# Bottom_PCB.net
KiCad netlist of a schematic drawn in EAGLE
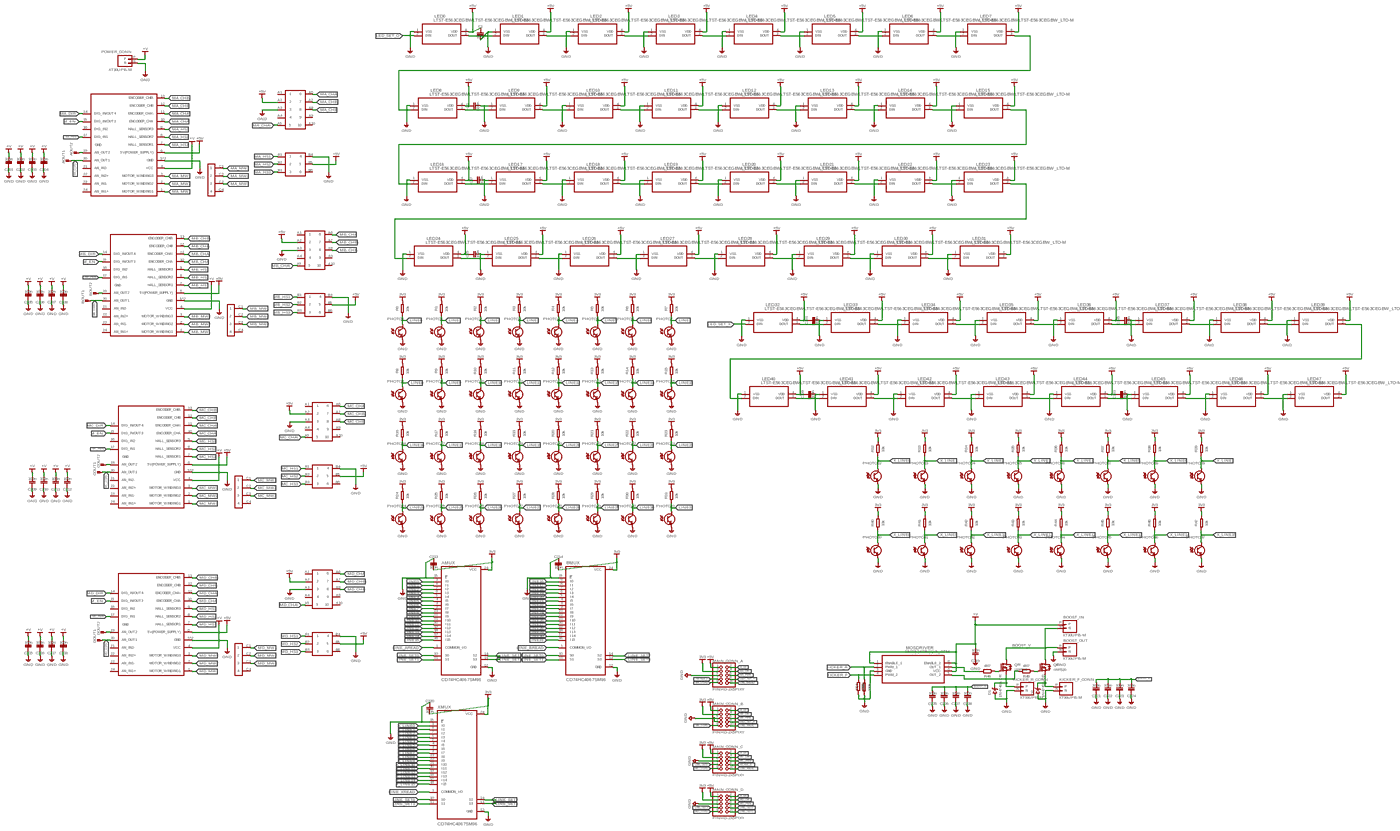
[diagram p0: schematic, sheet 1, overview]
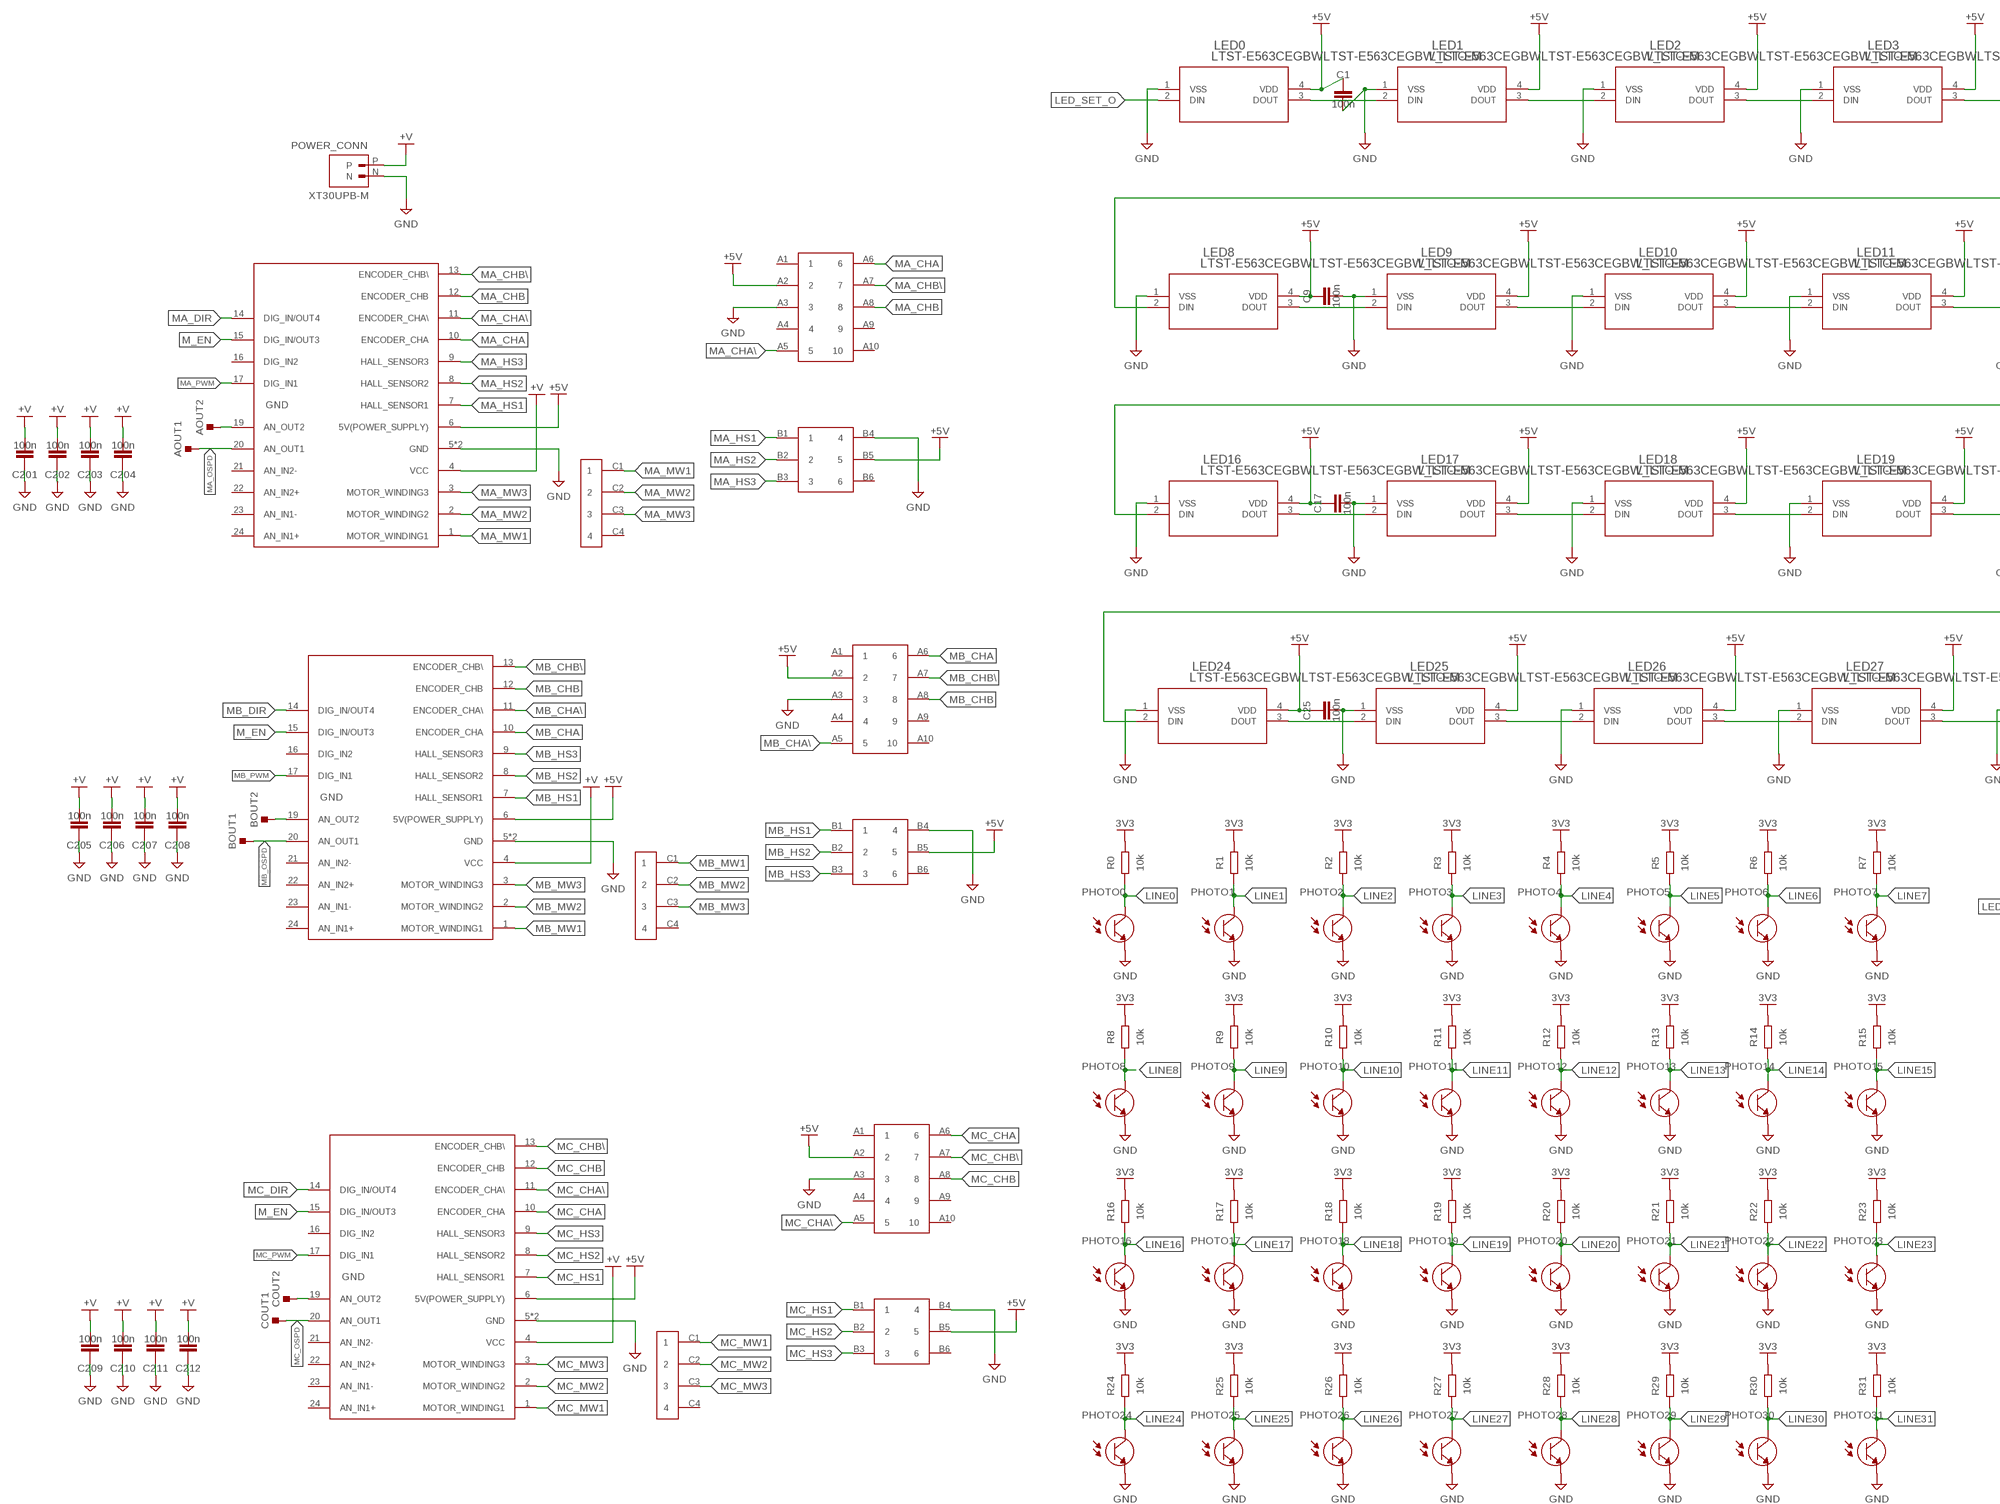
[diagram p1: schematic, sheet 1, part 1 of 4]
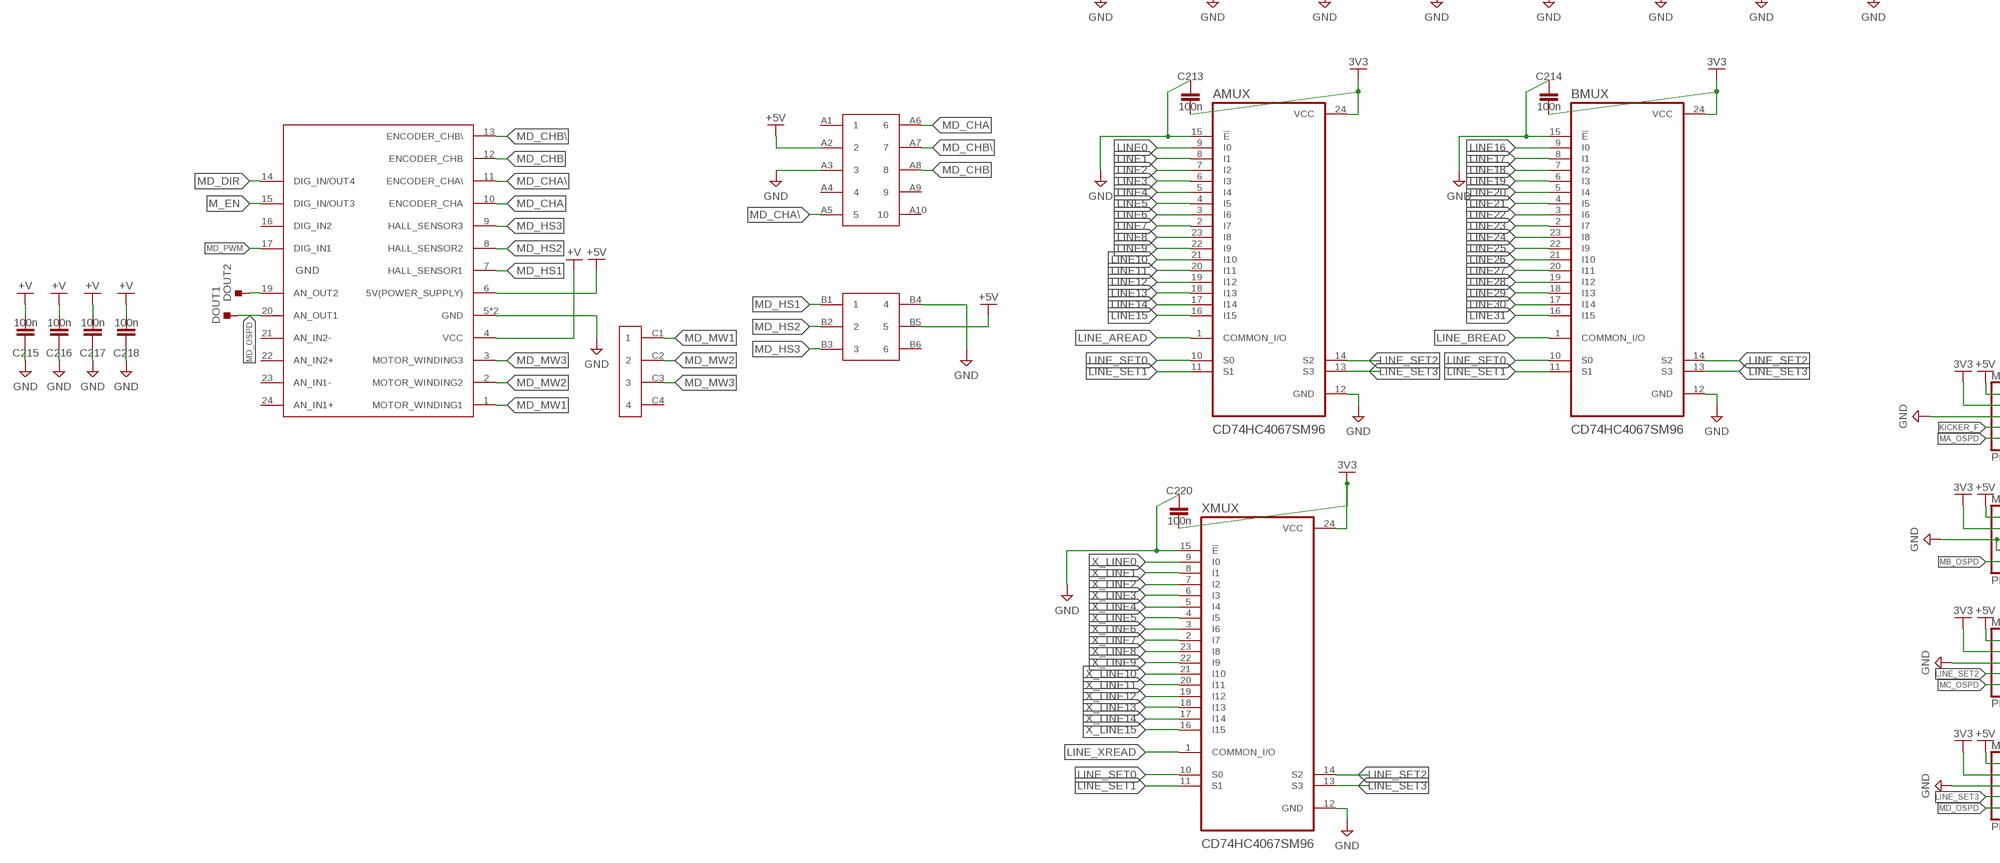
[diagram p2: schematic, sheet 1, part 2 of 4]
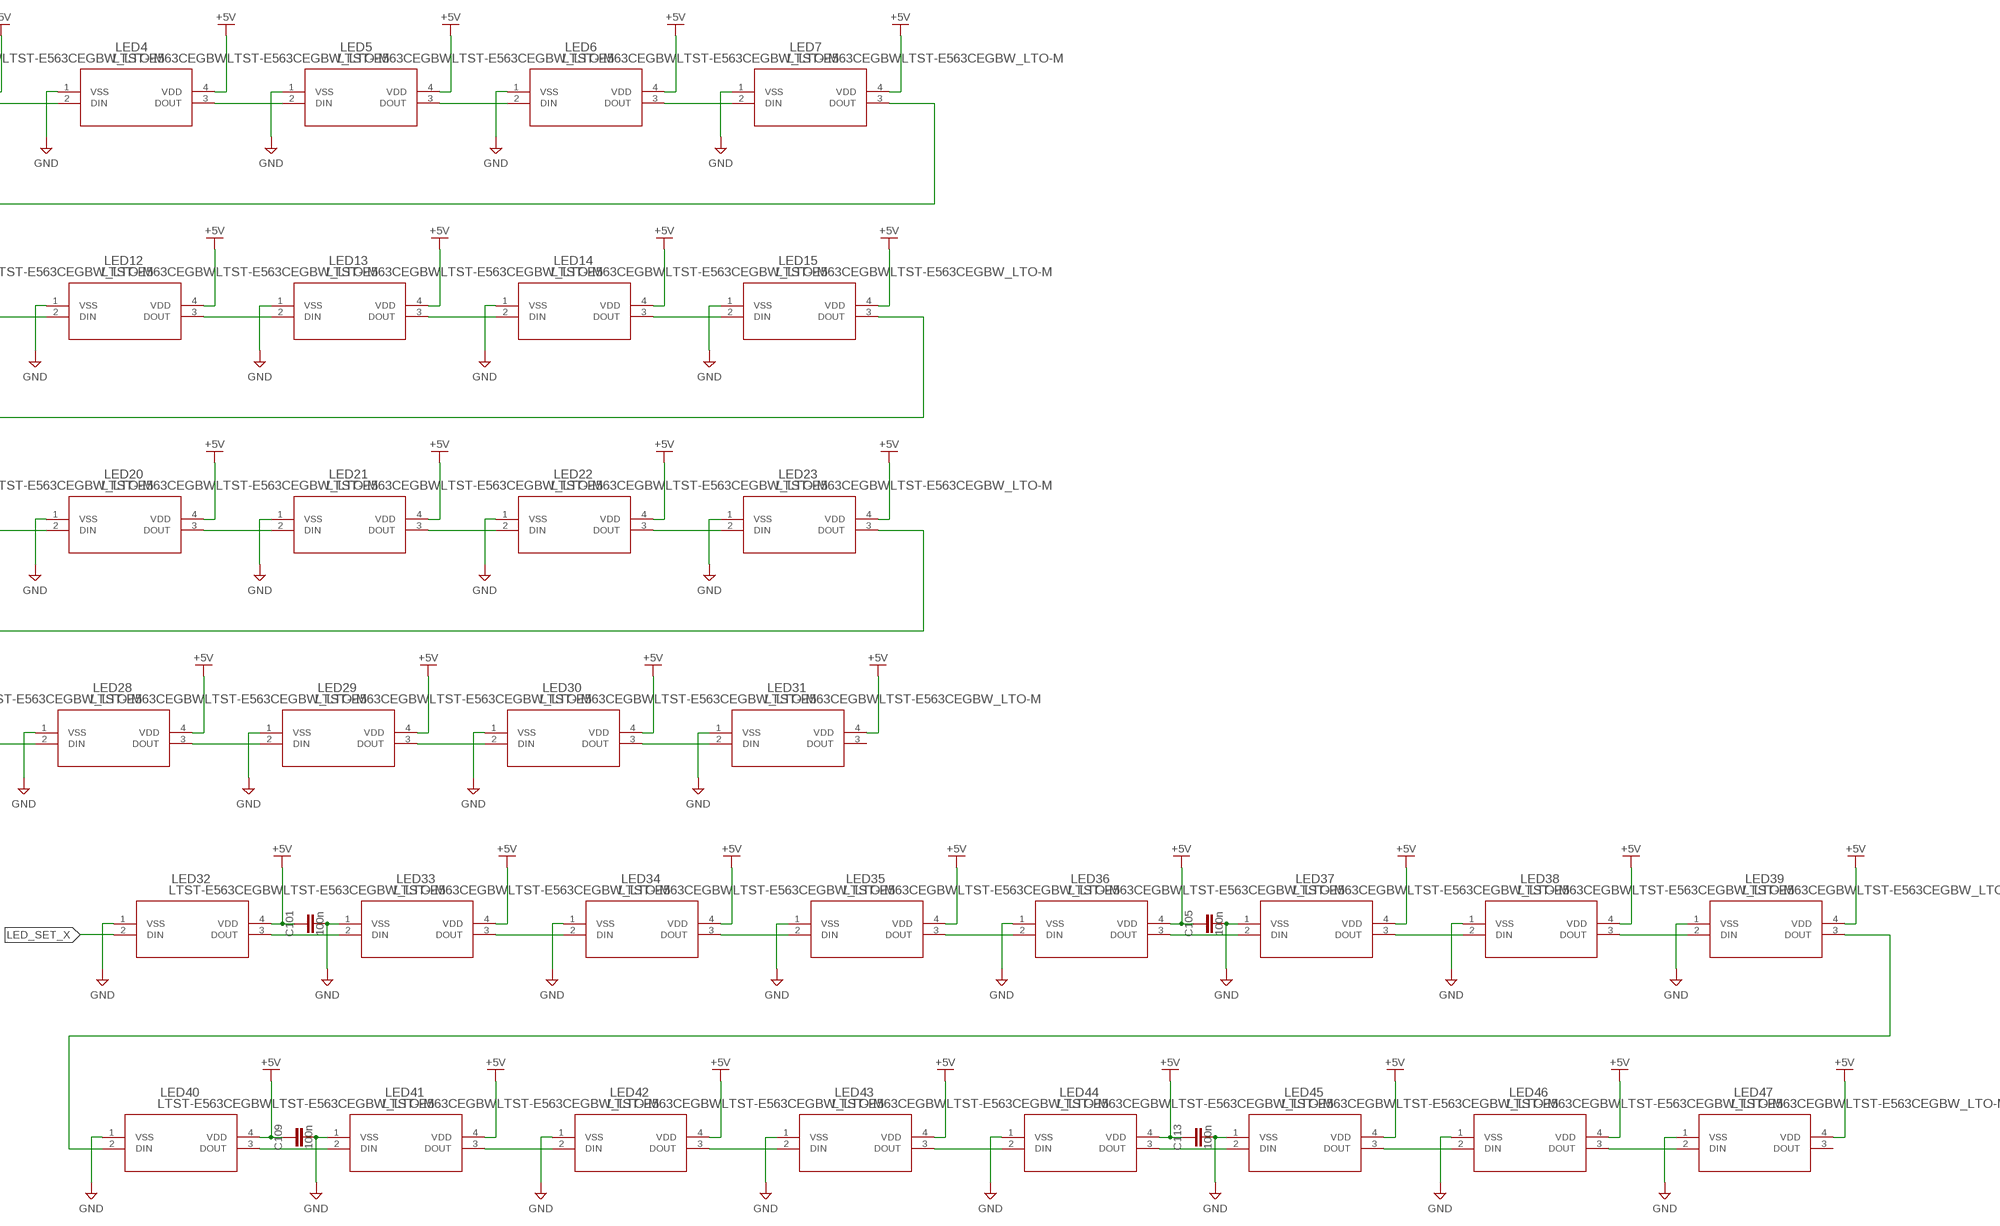
[diagram p3: schematic, sheet 1, part 3 of 4]
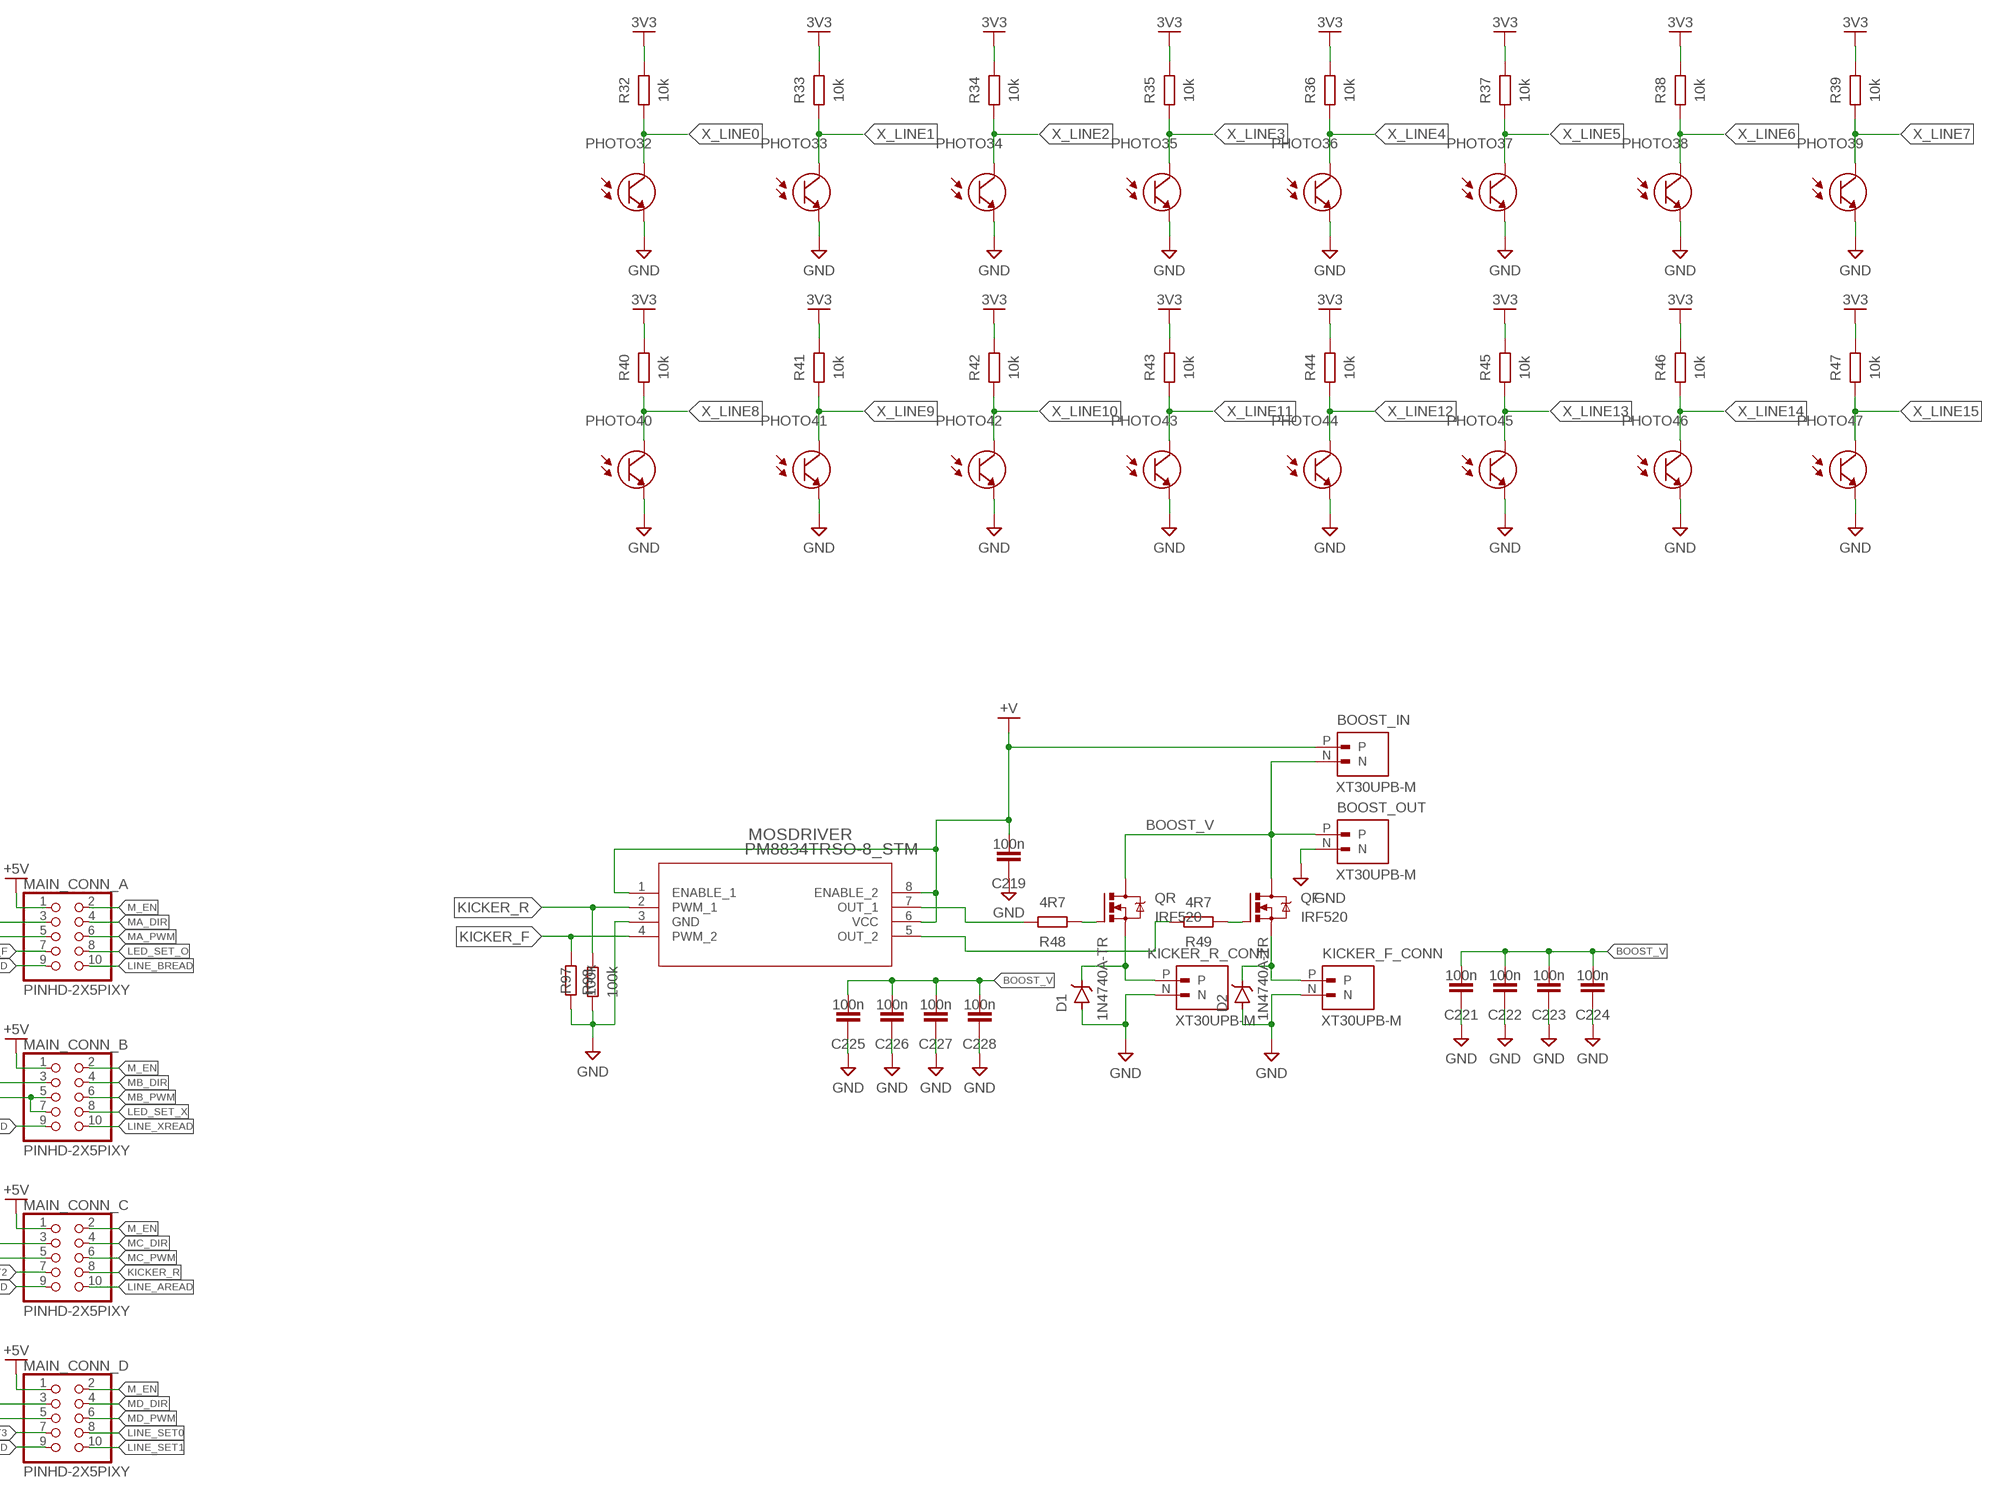
[diagram p4: schematic, sheet 1, part 4 of 4]

(export (version "E")
  (design (tool "Eeschema 10.0.6"))
  (components
    (comp (ref "AENC")
      (value "PIN2.54-2X5")
      (footprint "eagle-import:PIN2.54-2X5")
      (libsource (lib "eagle-import") (part "PIN2.54-2X5"))
    )
    (comp (ref "AHAL")
      (value "MX-44914-0601")
      (footprint "eagle-import:MX-44914-0601")
      (libsource (lib "eagle-import") (part "MX-44914-0601"))
    )
    (comp (ref "AMD")
      (value "ESCON24/224/2")
      (footprint "eagle-import:ESCON24_2")
      (libsource (lib "eagle-import") (part "ESCON24/224/2"))
    )
    (comp (ref "AMUX")
      (value "CD74HC4067SM96")
      (footprint "eagle-import:SOP65P780X200-24N")
      (libsource (lib "eagle-import") (part "CD74HC4067SM96"))
    )
    (comp (ref "AMW")
      (value "MX5566")
      (footprint "eagle-import:MX5566")
      (libsource (lib "eagle-import") (part "MX5566"))
    )
    (comp (ref "AOUT1")
      (value "TESTPOINT_TPS-PAD-036")
      (footprint "eagle-import:TESTPOINT_PAD-036")
      (libsource (lib "eagle-import") (part "TESTPOINT_TPS-PAD-036"))
    )
    (comp (ref "AOUT2")
      (value "TESTPOINT_TPS-PAD-036")
      (footprint "eagle-import:TESTPOINT_PAD-036")
      (libsource (lib "eagle-import") (part "TESTPOINT_TPS-PAD-036"))
    )
    (comp (ref "BENC")
      (value "PIN2.54-2X5")
      (footprint "eagle-import:PIN2.54-2X5")
      (libsource (lib "eagle-import") (part "PIN2.54-2X5"))
    )
    (comp (ref "BHAL")
      (value "MX-44914-0601")
      (footprint "eagle-import:MX-44914-0601")
      (libsource (lib "eagle-import") (part "MX-44914-0601"))
    )
    (comp (ref "BMD")
      (value "ESCON24/224/2")
      (footprint "eagle-import:ESCON24_2")
      (libsource (lib "eagle-import") (part "ESCON24/224/2"))
    )
    (comp (ref "BMUX")
      (value "CD74HC4067SM96")
      (footprint "eagle-import:SOP65P780X200-24N")
      (libsource (lib "eagle-import") (part "CD74HC4067SM96"))
    )
    (comp (ref "BMW")
      (value "MX5566")
      (footprint "eagle-import:MX5566")
      (libsource (lib "eagle-import") (part "MX5566"))
    )
    (comp (ref "BOOST_IN")
      (value "XT30UPB-M")
      (footprint "eagle-import:AMASS_XT30UPB-M")
      (fields (field (name "MF") "amass"))
      (libsource (lib "eagle-import") (part "XT30UPB-M"))
    )
    (comp (ref "BOOST_OUT")
      (value "XT30UPB-M")
      (footprint "eagle-import:AMASS_XT30UPB-M")
      (fields (field (name "MF") "amass"))
      (libsource (lib "eagle-import") (part "XT30UPB-M"))
    )
    (comp (ref "BOUT1")
      (value "TESTPOINT_TPS-PAD-036")
      (footprint "eagle-import:TESTPOINT_PAD-036")
      (libsource (lib "eagle-import") (part "TESTPOINT_TPS-PAD-036"))
    )
    (comp (ref "BOUT2")
      (value "TESTPOINT_TPS-PAD-036")
      (footprint "eagle-import:TESTPOINT_PAD-036")
      (libsource (lib "eagle-import") (part "TESTPOINT_TPS-PAD-036"))
    )
    (comp (ref "C1")
      (value "100n")
      (footprint "eagle-import:CAPC2012X110")
      (libsource (lib "eagle-import") (part "CCHIP-0805(2012-METRIC)_"))
    )
    (comp (ref "C9")
      (value "100n")
      (footprint "eagle-import:CAPC2012X110")
      (libsource (lib "eagle-import") (part "CCHIP-0805(2012-METRIC)_"))
    )
    (comp (ref "C17")
      (value "100n")
      (footprint "eagle-import:CAPC2012X110")
      (libsource (lib "eagle-import") (part "CCHIP-0805(2012-METRIC)_"))
    )
    (comp (ref "C25")
      (value "100n")
      (footprint "eagle-import:CAPC2012X110")
      (libsource (lib "eagle-import") (part "CCHIP-0805(2012-METRIC)_"))
    )
    (comp (ref "C101")
      (value "100n")
      (footprint "eagle-import:CAPC2012X110")
      (libsource (lib "eagle-import") (part "CCHIP-0805(2012-METRIC)_"))
    )
    (comp (ref "C105")
      (value "100n")
      (footprint "eagle-import:CAPC2012X110")
      (libsource (lib "eagle-import") (part "CCHIP-0805(2012-METRIC)_"))
    )
    (comp (ref "C109")
      (value "100n")
      (footprint "eagle-import:CAPC2012X110")
      (libsource (lib "eagle-import") (part "CCHIP-0805(2012-METRIC)_"))
    )
    (comp (ref "C113")
      (value "100n")
      (footprint "eagle-import:CAPC2012X110")
      (libsource (lib "eagle-import") (part "CCHIP-0805(2012-METRIC)_"))
    )
    (comp (ref "C201")
      (value "100n")
      (footprint "eagle-import:CAPC2012X110")
      (libsource (lib "eagle-import") (part "CCHIP-0805(2012-METRIC)_"))
    )
    (comp (ref "C202")
      (value "100n")
      (footprint "eagle-import:CAPC2012X110")
      (libsource (lib "eagle-import") (part "CCHIP-0805(2012-METRIC)_"))
    )
    (comp (ref "C203")
      (value "100n")
      (footprint "eagle-import:CAPC2012X110")
      (libsource (lib "eagle-import") (part "CCHIP-0805(2012-METRIC)_"))
    )
    (comp (ref "C204")
      (value "100n")
      (footprint "eagle-import:CAPC2012X110")
      (libsource (lib "eagle-import") (part "CCHIP-0805(2012-METRIC)_"))
    )
    (comp (ref "C205")
      (value "100n")
      (footprint "eagle-import:CAPC2012X110")
      (libsource (lib "eagle-import") (part "CCHIP-0805(2012-METRIC)_"))
    )
    (comp (ref "C206")
      (value "100n")
      (footprint "eagle-import:CAPC2012X110")
      (libsource (lib "eagle-import") (part "CCHIP-0805(2012-METRIC)_"))
    )
    (comp (ref "C207")
      (value "100n")
      (footprint "eagle-import:CAPC2012X110")
      (libsource (lib "eagle-import") (part "CCHIP-0805(2012-METRIC)_"))
    )
    (comp (ref "C208")
      (value "100n")
      (footprint "eagle-import:CAPC2012X110")
      (libsource (lib "eagle-import") (part "CCHIP-0805(2012-METRIC)_"))
    )
    (comp (ref "C209")
      (value "100n")
      (footprint "eagle-import:CAPC2012X110")
      (libsource (lib "eagle-import") (part "CCHIP-0805(2012-METRIC)_"))
    )
    (comp (ref "C210")
      (value "100n")
      (footprint "eagle-import:CAPC2012X110")
      (libsource (lib "eagle-import") (part "CCHIP-0805(2012-METRIC)_"))
    )
    (comp (ref "C211")
      (value "100n")
      (footprint "eagle-import:CAPC2012X110")
      (libsource (lib "eagle-import") (part "CCHIP-0805(2012-METRIC)_"))
    )
    (comp (ref "C212")
      (value "100n")
      (footprint "eagle-import:CAPC2012X110")
      (libsource (lib "eagle-import") (part "CCHIP-0805(2012-METRIC)_"))
    )
    (comp (ref "C213")
      (value "100n")
      (footprint "eagle-import:CAPC2012X110")
      (libsource (lib "eagle-import") (part "CCHIP-0805(2012-METRIC)_"))
    )
    (comp (ref "C214")
      (value "100n")
      (footprint "eagle-import:CAPC2012X110")
      (libsource (lib "eagle-import") (part "CCHIP-0805(2012-METRIC)_"))
    )
    (comp (ref "C215")
      (value "100n")
      (footprint "eagle-import:CAPC2012X110")
      (libsource (lib "eagle-import") (part "CCHIP-0805(2012-METRIC)_"))
    )
    (comp (ref "C216")
      (value "100n")
      (footprint "eagle-import:CAPC2012X110")
      (libsource (lib "eagle-import") (part "CCHIP-0805(2012-METRIC)_"))
    )
    (comp (ref "C217")
      (value "100n")
      (footprint "eagle-import:CAPC2012X110")
      (libsource (lib "eagle-import") (part "CCHIP-0805(2012-METRIC)_"))
    )
    (comp (ref "C218")
      (value "100n")
      (footprint "eagle-import:CAPC2012X110")
      (libsource (lib "eagle-import") (part "CCHIP-0805(2012-METRIC)_"))
    )
    (comp (ref "C219")
      (value "100n")
      (footprint "eagle-import:CAPC2012X110")
      (libsource (lib "eagle-import") (part "CCHIP-0805(2012-METRIC)_"))
    )
    (comp (ref "C220")
      (value "100n")
      (footprint "eagle-import:CAPC2012X110")
      (libsource (lib "eagle-import") (part "CCHIP-0805(2012-METRIC)_"))
    )
    (comp (ref "C221")
      (value "100n")
      (footprint "eagle-import:CAPC2012X110")
      (libsource (lib "eagle-import") (part "CCHIP-0805(2012-METRIC)_"))
    )
    (comp (ref "C222")
      (value "100n")
      (footprint "eagle-import:CAPC2012X110")
      (libsource (lib "eagle-import") (part "CCHIP-0805(2012-METRIC)_"))
    )
    (comp (ref "C223")
      (value "100n")
      (footprint "eagle-import:CAPC2012X110")
      (libsource (lib "eagle-import") (part "CCHIP-0805(2012-METRIC)_"))
    )
    (comp (ref "C224")
      (value "100n")
      (footprint "eagle-import:CAPC2012X110")
      (libsource (lib "eagle-import") (part "CCHIP-0805(2012-METRIC)_"))
    )
    (comp (ref "C225")
      (value "100n")
      (footprint "eagle-import:CAPC2012X110")
      (libsource (lib "eagle-import") (part "CCHIP-0805(2012-METRIC)_"))
    )
    (comp (ref "C226")
      (value "100n")
      (footprint "eagle-import:CAPC2012X110")
      (libsource (lib "eagle-import") (part "CCHIP-0805(2012-METRIC)_"))
    )
    (comp (ref "C227")
      (value "100n")
      (footprint "eagle-import:CAPC2012X110")
      (libsource (lib "eagle-import") (part "CCHIP-0805(2012-METRIC)_"))
    )
    (comp (ref "C228")
      (value "100n")
      (footprint "eagle-import:CAPC2012X110")
      (libsource (lib "eagle-import") (part "CCHIP-0805(2012-METRIC)_"))
    )
    (comp (ref "CENC")
      (value "PIN2.54-2X5")
      (footprint "eagle-import:PIN2.54-2X5")
      (libsource (lib "eagle-import") (part "PIN2.54-2X5"))
    )
    (comp (ref "CHAL")
      (value "MX-44914-0601")
      (footprint "eagle-import:MX-44914-0601")
      (libsource (lib "eagle-import") (part "MX-44914-0601"))
    )
    (comp (ref "CMD")
      (value "ESCON24/224/2")
      (footprint "eagle-import:ESCON24_2")
      (libsource (lib "eagle-import") (part "ESCON24/224/2"))
    )
    (comp (ref "CMW")
      (value "MX5566")
      (footprint "eagle-import:MX5566")
      (libsource (lib "eagle-import") (part "MX5566"))
    )
    (comp (ref "COUT1")
      (value "TESTPOINT_TPS-PAD-036")
      (footprint "eagle-import:TESTPOINT_PAD-036")
      (libsource (lib "eagle-import") (part "TESTPOINT_TPS-PAD-036"))
    )
    (comp (ref "COUT2")
      (value "TESTPOINT_TPS-PAD-036")
      (footprint "eagle-import:TESTPOINT_PAD-036")
      (libsource (lib "eagle-import") (part "TESTPOINT_TPS-PAD-036"))
    )
    (comp (ref "D1")
      (value "1N4740A-TR")
      (footprint "eagle-import:DO-41")
      (fields
        (field (name "MANUFACTURER") "Vishay General Semiconductor - Diodes Division")
        (field (name "DIGIKEY_PART_NUMBER") "1N4740AVSCT-ND")
        (field (name "CREATED_BY") "PCBLayout.com")
      )
      (libsource (lib "eagle-import") (part "1N4740A-TR"))
    )
    (comp (ref "D2")
      (value "1N4740A-TR")
      (footprint "eagle-import:DO-41")
      (fields
        (field (name "MANUFACTURER") "Vishay General Semiconductor - Diodes Division")
        (field (name "DIGIKEY_PART_NUMBER") "1N4740AVSCT-ND")
        (field (name "CREATED_BY") "PCBLayout.com")
      )
      (libsource (lib "eagle-import") (part "1N4740A-TR"))
    )
    (comp (ref "DENC")
      (value "PIN2.54-2X5")
      (footprint "eagle-import:PIN2.54-2X5")
      (libsource (lib "eagle-import") (part "PIN2.54-2X5"))
    )
    (comp (ref "DHAL")
      (value "MX-44914-0601")
      (footprint "eagle-import:MX-44914-0601")
      (libsource (lib "eagle-import") (part "MX-44914-0601"))
    )
    (comp (ref "DMD")
      (value "ESCON24/224/2")
      (footprint "eagle-import:ESCON24_2")
      (libsource (lib "eagle-import") (part "ESCON24/224/2"))
    )
    (comp (ref "DMW")
      (value "MX5566")
      (footprint "eagle-import:MX5566")
      (libsource (lib "eagle-import") (part "MX5566"))
    )
    (comp (ref "DOUT1")
      (value "TESTPOINT_TPS-PAD-036")
      (footprint "eagle-import:TESTPOINT_PAD-036")
      (libsource (lib "eagle-import") (part "TESTPOINT_TPS-PAD-036"))
    )
    (comp (ref "DOUT2")
      (value "TESTPOINT_TPS-PAD-036")
      (footprint "eagle-import:TESTPOINT_PAD-036")
      (libsource (lib "eagle-import") (part "TESTPOINT_TPS-PAD-036"))
    )
    (comp (ref "KICKER_F_CONN")
      (value "XT30UPB-M")
      (footprint "eagle-import:AMASS_XT30UPB-M")
      (fields (field (name "MF") "amass"))
      (libsource (lib "eagle-import") (part "XT30UPB-M"))
    )
    (comp (ref "KICKER_R_CONN")
      (value "XT30UPB-M")
      (footprint "eagle-import:AMASS_XT30UPB-M")
      (fields (field (name "MF") "amass"))
      (libsource (lib "eagle-import") (part "XT30UPB-M"))
    )
    (comp (ref "LED0")
      (value "LTST-E563CEGBWLTST-E563CEGBW_LTO-M")
      (footprint "eagle-import:LTST-E563CEGBW_LTO-M")
      (fields
        (field (name "MANUFACTURER_PART_NUMBER") "LTST-E563CEGBW")
        (field (name "COPYRIGHT") "Copyright (C) 2025 Ultra Librarian. All rights reserved.")
      )
      (libsource (lib "eagle-import") (part "LTST-E563CEGBWLTST-E563CEGBW_LTO-M"))
    )
    (comp (ref "LED1")
      (value "LTST-E563CEGBWLTST-E563CEGBW_LTO-M")
      (footprint "eagle-import:LTST-E563CEGBW_LTO-M")
      (fields
        (field (name "MANUFACTURER_PART_NUMBER") "LTST-E563CEGBW")
        (field (name "COPYRIGHT") "Copyright (C) 2025 Ultra Librarian. All rights reserved.")
      )
      (libsource (lib "eagle-import") (part "LTST-E563CEGBWLTST-E563CEGBW_LTO-M"))
    )
    (comp (ref "LED2")
      (value "LTST-E563CEGBWLTST-E563CEGBW_LTO-M")
      (footprint "eagle-import:LTST-E563CEGBW_LTO-M")
      (fields
        (field (name "MANUFACTURER_PART_NUMBER") "LTST-E563CEGBW")
        (field (name "COPYRIGHT") "Copyright (C) 2025 Ultra Librarian. All rights reserved.")
      )
      (libsource (lib "eagle-import") (part "LTST-E563CEGBWLTST-E563CEGBW_LTO-M"))
    )
    (comp (ref "LED3")
      (value "LTST-E563CEGBWLTST-E563CEGBW_LTO-M")
      (footprint "eagle-import:LTST-E563CEGBW_LTO-M")
      (fields
        (field (name "MANUFACTURER_PART_NUMBER") "LTST-E563CEGBW")
        (field (name "COPYRIGHT") "Copyright (C) 2025 Ultra Librarian. All rights reserved.")
      )
      (libsource (lib "eagle-import") (part "LTST-E563CEGBWLTST-E563CEGBW_LTO-M"))
    )
    (comp (ref "LED4")
      (value "LTST-E563CEGBWLTST-E563CEGBW_LTO-M")
      (footprint "eagle-import:LTST-E563CEGBW_LTO-M")
      (fields
        (field (name "MANUFACTURER_PART_NUMBER") "LTST-E563CEGBW")
        (field (name "COPYRIGHT") "Copyright (C) 2025 Ultra Librarian. All rights reserved.")
      )
      (libsource (lib "eagle-import") (part "LTST-E563CEGBWLTST-E563CEGBW_LTO-M"))
    )
    (comp (ref "LED5")
      (value "LTST-E563CEGBWLTST-E563CEGBW_LTO-M")
      (footprint "eagle-import:LTST-E563CEGBW_LTO-M")
      (fields
        (field (name "MANUFACTURER_PART_NUMBER") "LTST-E563CEGBW")
        (field (name "COPYRIGHT") "Copyright (C) 2025 Ultra Librarian. All rights reserved.")
      )
      (libsource (lib "eagle-import") (part "LTST-E563CEGBWLTST-E563CEGBW_LTO-M"))
    )
    (comp (ref "LED6")
      (value "LTST-E563CEGBWLTST-E563CEGBW_LTO-M")
      (footprint "eagle-import:LTST-E563CEGBW_LTO-M")
      (fields
        (field (name "MANUFACTURER_PART_NUMBER") "LTST-E563CEGBW")
        (field (name "COPYRIGHT") "Copyright (C) 2025 Ultra Librarian. All rights reserved.")
      )
      (libsource (lib "eagle-import") (part "LTST-E563CEGBWLTST-E563CEGBW_LTO-M"))
    )
    (comp (ref "LED7")
      (value "LTST-E563CEGBWLTST-E563CEGBW_LTO-M")
      (footprint "eagle-import:LTST-E563CEGBW_LTO-M")
      (fields
        (field (name "MANUFACTURER_PART_NUMBER") "LTST-E563CEGBW")
        (field (name "COPYRIGHT") "Copyright (C) 2025 Ultra Librarian. All rights reserved.")
      )
      (libsource (lib "eagle-import") (part "LTST-E563CEGBWLTST-E563CEGBW_LTO-M"))
    )
    (comp (ref "LED8")
      (value "LTST-E563CEGBWLTST-E563CEGBW_LTO-M")
      (footprint "eagle-import:LTST-E563CEGBW_LTO-M")
      (fields
        (field (name "MANUFACTURER_PART_NUMBER") "LTST-E563CEGBW")
        (field (name "COPYRIGHT") "Copyright (C) 2025 Ultra Librarian. All rights reserved.")
      )
      (libsource (lib "eagle-import") (part "LTST-E563CEGBWLTST-E563CEGBW_LTO-M"))
    )
    (comp (ref "LED9")
      (value "LTST-E563CEGBWLTST-E563CEGBW_LTO-M")
      (footprint "eagle-import:LTST-E563CEGBW_LTO-M")
      (fields
        (field (name "MANUFACTURER_PART_NUMBER") "LTST-E563CEGBW")
        (field (name "COPYRIGHT") "Copyright (C) 2025 Ultra Librarian. All rights reserved.")
      )
      (libsource (lib "eagle-import") (part "LTST-E563CEGBWLTST-E563CEGBW_LTO-M"))
    )
    (comp (ref "LED10")
      (value "LTST-E563CEGBWLTST-E563CEGBW_LTO-M")
      (footprint "eagle-import:LTST-E563CEGBW_LTO-M")
      (fields
        (field (name "MANUFACTURER_PART_NUMBER") "LTST-E563CEGBW")
        (field (name "COPYRIGHT") "Copyright (C) 2025 Ultra Librarian. All rights reserved.")
      )
      (libsource (lib "eagle-import") (part "LTST-E563CEGBWLTST-E563CEGBW_LTO-M"))
    )
    (comp (ref "LED11")
      (value "LTST-E563CEGBWLTST-E563CEGBW_LTO-M")
      (footprint "eagle-import:LTST-E563CEGBW_LTO-M")
      (fields
        (field (name "MANUFACTURER_PART_NUMBER") "LTST-E563CEGBW")
        (field (name "COPYRIGHT") "Copyright (C) 2025 Ultra Librarian. All rights reserved.")
      )
      (libsource (lib "eagle-import") (part "LTST-E563CEGBWLTST-E563CEGBW_LTO-M"))
    )
    (comp (ref "LED12")
      (value "LTST-E563CEGBWLTST-E563CEGBW_LTO-M")
      (footprint "eagle-import:LTST-E563CEGBW_LTO-M")
      (fields
        (field (name "MANUFACTURER_PART_NUMBER") "LTST-E563CEGBW")
        (field (name "COPYRIGHT") "Copyright (C) 2025 Ultra Librarian. All rights reserved.")
      )
      (libsource (lib "eagle-import") (part "LTST-E563CEGBWLTST-E563CEGBW_LTO-M"))
    )
    (comp (ref "LED13")
      (value "LTST-E563CEGBWLTST-E563CEGBW_LTO-M")
      (footprint "eagle-import:LTST-E563CEGBW_LTO-M")
      (fields
        (field (name "MANUFACTURER_PART_NUMBER") "LTST-E563CEGBW")
        (field (name "COPYRIGHT") "Copyright (C) 2025 Ultra Librarian. All rights reserved.")
      )
      (libsource (lib "eagle-import") (part "LTST-E563CEGBWLTST-E563CEGBW_LTO-M"))
    )
    (comp (ref "LED14")
      (value "LTST-E563CEGBWLTST-E563CEGBW_LTO-M")
      (footprint "eagle-import:LTST-E563CEGBW_LTO-M")
      (fields
        (field (name "MANUFACTURER_PART_NUMBER") "LTST-E563CEGBW")
        (field (name "COPYRIGHT") "Copyright (C) 2025 Ultra Librarian. All rights reserved.")
      )
      (libsource (lib "eagle-import") (part "LTST-E563CEGBWLTST-E563CEGBW_LTO-M"))
    )
    (comp (ref "LED15")
      (value "LTST-E563CEGBWLTST-E563CEGBW_LTO-M")
      (footprint "eagle-import:LTST-E563CEGBW_LTO-M")
      (fields
        (field (name "MANUFACTURER_PART_NUMBER") "LTST-E563CEGBW")
        (field (name "COPYRIGHT") "Copyright (C) 2025 Ultra Librarian. All rights reserved.")
      )
      (libsource (lib "eagle-import") (part "LTST-E563CEGBWLTST-E563CEGBW_LTO-M"))
    )
    (comp (ref "LED16")
      (value "LTST-E563CEGBWLTST-E563CEGBW_LTO-M")
      (footprint "eagle-import:LTST-E563CEGBW_LTO-M")
      (fields
        (field (name "MANUFACTURER_PART_NUMBER") "LTST-E563CEGBW")
        (field (name "COPYRIGHT") "Copyright (C) 2025 Ultra Librarian. All rights reserved.")
      )
      (libsource (lib "eagle-import") (part "LTST-E563CEGBWLTST-E563CEGBW_LTO-M"))
    )
    (comp (ref "LED17")
      (value "LTST-E563CEGBWLTST-E563CEGBW_LTO-M")
      (footprint "eagle-import:LTST-E563CEGBW_LTO-M")
      (fields
        (field (name "MANUFACTURER_PART_NUMBER") "LTST-E563CEGBW")
        (field (name "COPYRIGHT") "Copyright (C) 2025 Ultra Librarian. All rights reserved.")
      )
      (libsource (lib "eagle-import") (part "LTST-E563CEGBWLTST-E563CEGBW_LTO-M"))
    )
    (comp (ref "LED18")
      (value "LTST-E563CEGBWLTST-E563CEGBW_LTO-M")
      (footprint "eagle-import:LTST-E563CEGBW_LTO-M")
      (fields
        (field (name "MANUFACTURER_PART_NUMBER") "LTST-E563CEGBW")
        (field (name "COPYRIGHT") "Copyright (C) 2025 Ultra Librarian. All rights reserved.")
      )
      (libsource (lib "eagle-import") (part "LTST-E563CEGBWLTST-E563CEGBW_LTO-M"))
    )
    (comp (ref "LED19")
      (value "LTST-E563CEGBWLTST-E563CEGBW_LTO-M")
      (footprint "eagle-import:LTST-E563CEGBW_LTO-M")
      (fields
        (field (name "MANUFACTURER_PART_NUMBER") "LTST-E563CEGBW")
        (field (name "COPYRIGHT") "Copyright (C) 2025 Ultra Librarian. All rights reserved.")
      )
      (libsource (lib "eagle-import") (part "LTST-E563CEGBWLTST-E563CEGBW_LTO-M"))
    )
    (comp (ref "LED20")
      (value "LTST-E563CEGBWLTST-E563CEGBW_LTO-M")
      (footprint "eagle-import:LTST-E563CEGBW_LTO-M")
      (fields
        (field (name "MANUFACTURER_PART_NUMBER") "LTST-E563CEGBW")
        (field (name "COPYRIGHT") "Copyright (C) 2025 Ultra Librarian. All rights reserved.")
      )
      (libsource (lib "eagle-import") (part "LTST-E563CEGBWLTST-E563CEGBW_LTO-M"))
    )
    (comp (ref "LED21")
      (value "LTST-E563CEGBWLTST-E563CEGBW_LTO-M")
      (footprint "eagle-import:LTST-E563CEGBW_LTO-M")
      (fields
        (field (name "MANUFACTURER_PART_NUMBER") "LTST-E563CEGBW")
        (field (name "COPYRIGHT") "Copyright (C) 2025 Ultra Librarian. All rights reserved.")
      )
      (libsource (lib "eagle-import") (part "LTST-E563CEGBWLTST-E563CEGBW_LTO-M"))
    )
    (comp (ref "LED22")
      (value "LTST-E563CEGBWLTST-E563CEGBW_LTO-M")
      (footprint "eagle-import:LTST-E563CEGBW_LTO-M")
      (fields
        (field (name "MANUFACTURER_PART_NUMBER") "LTST-E563CEGBW")
        (field (name "COPYRIGHT") "Copyright (C) 2025 Ultra Librarian. All rights reserved.")
      )
      (libsource (lib "eagle-import") (part "LTST-E563CEGBWLTST-E563CEGBW_LTO-M"))
    )
    (comp (ref "LED23")
      (value "LTST-E563CEGBWLTST-E563CEGBW_LTO-M")
      (footprint "eagle-import:LTST-E563CEGBW_LTO-M")
      (fields
        (field (name "MANUFACTURER_PART_NUMBER") "LTST-E563CEGBW")
        (field (name "COPYRIGHT") "Copyright (C) 2025 Ultra Librarian. All rights reserved.")
      )
      (libsource (lib "eagle-import") (part "LTST-E563CEGBWLTST-E563CEGBW_LTO-M"))
    )
    (comp (ref "LED24")
      (value "LTST-E563CEGBWLTST-E563CEGBW_LTO-M")
      (footprint "eagle-import:LTST-E563CEGBW_LTO-M")
      (fields
        (field (name "MANUFACTURER_PART_NUMBER") "LTST-E563CEGBW")
        (field (name "COPYRIGHT") "Copyright (C) 2025 Ultra Librarian. All rights reserved.")
      )
      (libsource (lib "eagle-import") (part "LTST-E563CEGBWLTST-E563CEGBW_LTO-M"))
    )
    (comp (ref "LED25")
      (value "LTST-E563CEGBWLTST-E563CEGBW_LTO-M")
      (footprint "eagle-import:LTST-E563CEGBW_LTO-M")
      (fields
        (field (name "MANUFACTURER_PART_NUMBER") "LTST-E563CEGBW")
        (field (name "COPYRIGHT") "Copyright (C) 2025 Ultra Librarian. All rights reserved.")
      )
      (libsource (lib "eagle-import") (part "LTST-E563CEGBWLTST-E563CEGBW_LTO-M"))
    )
    (comp (ref "LED26")
      (value "LTST-E563CEGBWLTST-E563CEGBW_LTO-M")
      (footprint "eagle-import:LTST-E563CEGBW_LTO-M")
      (fields
        (field (name "MANUFACTURER_PART_NUMBER") "LTST-E563CEGBW")
        (field (name "COPYRIGHT") "Copyright (C) 2025 Ultra Librarian. All rights reserved.")
      )
      (libsource (lib "eagle-import") (part "LTST-E563CEGBWLTST-E563CEGBW_LTO-M"))
    )
    (comp (ref "LED27")
      (value "LTST-E563CEGBWLTST-E563CEGBW_LTO-M")
      (footprint "eagle-import:LTST-E563CEGBW_LTO-M")
      (fields
        (field (name "MANUFACTURER_PART_NUMBER") "LTST-E563CEGBW")
        (field (name "COPYRIGHT") "Copyright (C) 2025 Ultra Librarian. All rights reserved.")
      )
      (libsource (lib "eagle-import") (part "LTST-E563CEGBWLTST-E563CEGBW_LTO-M"))
    )
    (comp (ref "LED28")
      (value "LTST-E563CEGBWLTST-E563CEGBW_LTO-M")
      (footprint "eagle-import:LTST-E563CEGBW_LTO-M")
      (fields
        (field (name "MANUFACTURER_PART_NUMBER") "LTST-E563CEGBW")
        (field (name "COPYRIGHT") "Copyright (C) 2025 Ultra Librarian. All rights reserved.")
      )
      (libsource (lib "eagle-import") (part "LTST-E563CEGBWLTST-E563CEGBW_LTO-M"))
    )
    (comp (ref "LED29")
      (value "LTST-E563CEGBWLTST-E563CEGBW_LTO-M")
      (footprint "eagle-import:LTST-E563CEGBW_LTO-M")
      (fields
        (field (name "MANUFACTURER_PART_NUMBER") "LTST-E563CEGBW")
        (field (name "COPYRIGHT") "Copyright (C) 2025 Ultra Librarian. All rights reserved.")
      )
      (libsource (lib "eagle-import") (part "LTST-E563CEGBWLTST-E563CEGBW_LTO-M"))
    )
    (comp (ref "LED30")
      (value "LTST-E563CEGBWLTST-E563CEGBW_LTO-M")
      (footprint "eagle-import:LTST-E563CEGBW_LTO-M")
      (fields
        (field (name "MANUFACTURER_PART_NUMBER") "LTST-E563CEGBW")
        (field (name "COPYRIGHT") "Copyright (C) 2025 Ultra Librarian. All rights reserved.")
      )
      (libsource (lib "eagle-import") (part "LTST-E563CEGBWLTST-E563CEGBW_LTO-M"))
    )
    (comp (ref "LED31")
      (value "LTST-E563CEGBWLTST-E563CEGBW_LTO-M")
      (footprint "eagle-import:LTST-E563CEGBW_LTO-M")
      (fields
        (field (name "MANUFACTURER_PART_NUMBER") "LTST-E563CEGBW")
        (field (name "COPYRIGHT") "Copyright (C) 2025 Ultra Librarian. All rights reserved.")
      )
      (libsource (lib "eagle-import") (part "LTST-E563CEGBWLTST-E563CEGBW_LTO-M"))
    )
    (comp (ref "LED32")
      (value "LTST-E563CEGBWLTST-E563CEGBW_LTO-M")
      (footprint "eagle-import:LTST-E563CEGBW_LTO-M")
      (fields
        (field (name "MANUFACTURER_PART_NUMBER") "LTST-E563CEGBW")
        (field (name "COPYRIGHT") "Copyright (C) 2025 Ultra Librarian. All rights reserved.")
      )
      (libsource (lib "eagle-import") (part "LTST-E563CEGBWLTST-E563CEGBW_LTO-M"))
    )
    (comp (ref "LED33")
      (value "LTST-E563CEGBWLTST-E563CEGBW_LTO-M")
      (footprint "eagle-import:LTST-E563CEGBW_LTO-M")
      (fields
        (field (name "MANUFACTURER_PART_NUMBER") "LTST-E563CEGBW")
        (field (name "COPYRIGHT") "Copyright (C) 2025 Ultra Librarian. All rights reserved.")
      )
      (libsource (lib "eagle-import") (part "LTST-E563CEGBWLTST-E563CEGBW_LTO-M"))
    )
    (comp (ref "LED34")
      (value "LTST-E563CEGBWLTST-E563CEGBW_LTO-M")
      (footprint "eagle-import:LTST-E563CEGBW_LTO-M")
      (fields
        (field (name "MANUFACTURER_PART_NUMBER") "LTST-E563CEGBW")
        (field (name "COPYRIGHT") "Copyright (C) 2025 Ultra Librarian. All rights reserved.")
      )
      (libsource (lib "eagle-import") (part "LTST-E563CEGBWLTST-E563CEGBW_LTO-M"))
    )
    (comp (ref "LED35")
      (value "LTST-E563CEGBWLTST-E563CEGBW_LTO-M")
      (footprint "eagle-import:LTST-E563CEGBW_LTO-M")
      (fields
        (field (name "MANUFACTURER_PART_NUMBER") "LTST-E563CEGBW")
        (field (name "COPYRIGHT") "Copyright (C) 2025 Ultra Librarian. All rights reserved.")
      )
      (libsource (lib "eagle-import") (part "LTST-E563CEGBWLTST-E563CEGBW_LTO-M"))
    )
    (comp (ref "LED36")
      (value "LTST-E563CEGBWLTST-E563CEGBW_LTO-M")
      (footprint "eagle-import:LTST-E563CEGBW_LTO-M")
      (fields
        (field (name "MANUFACTURER_PART_NUMBER") "LTST-E563CEGBW")
        (field (name "COPYRIGHT") "Copyright (C) 2025 Ultra Librarian. All rights reserved.")
      )
      (libsource (lib "eagle-import") (part "LTST-E563CEGBWLTST-E563CEGBW_LTO-M"))
    )
    (comp (ref "LED37")
      (value "LTST-E563CEGBWLTST-E563CEGBW_LTO-M")
      (footprint "eagle-import:LTST-E563CEGBW_LTO-M")
      (fields
        (field (name "MANUFACTURER_PART_NUMBER") "LTST-E563CEGBW")
        (field (name "COPYRIGHT") "Copyright (C) 2025 Ultra Librarian. All rights reserved.")
      )
      (libsource (lib "eagle-import") (part "LTST-E563CEGBWLTST-E563CEGBW_LTO-M"))
    )
    (comp (ref "LED38")
      (value "LTST-E563CEGBWLTST-E563CEGBW_LTO-M")
      (footprint "eagle-import:LTST-E563CEGBW_LTO-M")
      (fields
        (field (name "MANUFACTURER_PART_NUMBER") "LTST-E563CEGBW")
        (field (name "COPYRIGHT") "Copyright (C) 2025 Ultra Librarian. All rights reserved.")
      )
      (libsource (lib "eagle-import") (part "LTST-E563CEGBWLTST-E563CEGBW_LTO-M"))
    )
    (comp (ref "LED39")
      (value "LTST-E563CEGBWLTST-E563CEGBW_LTO-M")
      (footprint "eagle-import:LTST-E563CEGBW_LTO-M")
      (fields
        (field (name "MANUFACTURER_PART_NUMBER") "LTST-E563CEGBW")
        (field (name "COPYRIGHT") "Copyright (C) 2025 Ultra Librarian. All rights reserved.")
      )
      (libsource (lib "eagle-import") (part "LTST-E563CEGBWLTST-E563CEGBW_LTO-M"))
    )
    (comp (ref "LED40")
      (value "LTST-E563CEGBWLTST-E563CEGBW_LTO-M")
      (footprint "eagle-import:LTST-E563CEGBW_LTO-M")
      (fields
        (field (name "MANUFACTURER_PART_NUMBER") "LTST-E563CEGBW")
        (field (name "COPYRIGHT") "Copyright (C) 2025 Ultra Librarian. All rights reserved.")
      )
      (libsource (lib "eagle-import") (part "LTST-E563CEGBWLTST-E563CEGBW_LTO-M"))
    )
    (comp (ref "LED41")
      (value "LTST-E563CEGBWLTST-E563CEGBW_LTO-M")
      (footprint "eagle-import:LTST-E563CEGBW_LTO-M")
      (fields
        (field (name "MANUFACTURER_PART_NUMBER") "LTST-E563CEGBW")
        (field (name "COPYRIGHT") "Copyright (C) 2025 Ultra Librarian. All rights reserved.")
      )
      (libsource (lib "eagle-import") (part "LTST-E563CEGBWLTST-E563CEGBW_LTO-M"))
    )
    (comp (ref "LED42")
      (value "LTST-E563CEGBWLTST-E563CEGBW_LTO-M")
      (footprint "eagle-import:LTST-E563CEGBW_LTO-M")
      (fields
        (field (name "MANUFACTURER_PART_NUMBER") "LTST-E563CEGBW")
        (field (name "COPYRIGHT") "Copyright (C) 2025 Ultra Librarian. All rights reserved.")
      )
      (libsource (lib "eagle-import") (part "LTST-E563CEGBWLTST-E563CEGBW_LTO-M"))
    )
    (comp (ref "LED43")
      (value "LTST-E563CEGBWLTST-E563CEGBW_LTO-M")
      (footprint "eagle-import:LTST-E563CEGBW_LTO-M")
      (fields
        (field (name "MANUFACTURER_PART_NUMBER") "LTST-E563CEGBW")
        (field (name "COPYRIGHT") "Copyright (C) 2025 Ultra Librarian. All rights reserved.")
      )
      (libsource (lib "eagle-import") (part "LTST-E563CEGBWLTST-E563CEGBW_LTO-M"))
    )
    (comp (ref "LED44")
      (value "LTST-E563CEGBWLTST-E563CEGBW_LTO-M")
      (footprint "eagle-import:LTST-E563CEGBW_LTO-M")
      (fields
        (field (name "MANUFACTURER_PART_NUMBER") "LTST-E563CEGBW")
        (field (name "COPYRIGHT") "Copyright (C) 2025 Ultra Librarian. All rights reserved.")
      )
      (libsource (lib "eagle-import") (part "LTST-E563CEGBWLTST-E563CEGBW_LTO-M"))
    )
    (comp (ref "LED45")
      (value "LTST-E563CEGBWLTST-E563CEGBW_LTO-M")
      (footprint "eagle-import:LTST-E563CEGBW_LTO-M")
      (fields
        (field (name "MANUFACTURER_PART_NUMBER") "LTST-E563CEGBW")
        (field (name "COPYRIGHT") "Copyright (C) 2025 Ultra Librarian. All rights reserved.")
      )
      (libsource (lib "eagle-import") (part "LTST-E563CEGBWLTST-E563CEGBW_LTO-M"))
    )
    (comp (ref "LED46")
      (value "LTST-E563CEGBWLTST-E563CEGBW_LTO-M")
      (footprint "eagle-import:LTST-E563CEGBW_LTO-M")
      (fields
        (field (name "MANUFACTURER_PART_NUMBER") "LTST-E563CEGBW")
        (field (name "COPYRIGHT") "Copyright (C) 2025 Ultra Librarian. All rights reserved.")
      )
      (libsource (lib "eagle-import") (part "LTST-E563CEGBWLTST-E563CEGBW_LTO-M"))
    )
    (comp (ref "LED47")
      (value "LTST-E563CEGBWLTST-E563CEGBW_LTO-M")
      (footprint "eagle-import:LTST-E563CEGBW_LTO-M")
      (fields
        (field (name "MANUFACTURER_PART_NUMBER") "LTST-E563CEGBW")
        (field (name "COPYRIGHT") "Copyright (C) 2025 Ultra Librarian. All rights reserved.")
      )
      (libsource (lib "eagle-import") (part "LTST-E563CEGBWLTST-E563CEGBW_LTO-M"))
    )
    (comp (ref "MAIN_CONN_A")
      (value "PINHD-2X5PIXY")
      (footprint "eagle-import:2X05")
      (libsource (lib "eagle-import") (part "PINHD-2X5PIXY"))
    )
    (comp (ref "MAIN_CONN_B")
      (value "PINHD-2X5PIXY")
      (footprint "eagle-import:2X05")
      (libsource (lib "eagle-import") (part "PINHD-2X5PIXY"))
    )
    (comp (ref "MAIN_CONN_C")
      (value "PINHD-2X5PIXY")
      (footprint "eagle-import:2X05")
      (libsource (lib "eagle-import") (part "PINHD-2X5PIXY"))
    )
    (comp (ref "MAIN_CONN_D")
      (value "PINHD-2X5PIXY")
      (footprint "eagle-import:2X05")
      (libsource (lib "eagle-import") (part "PINHD-2X5PIXY"))
    )
    (comp (ref "MOSDRIVER")
      (value "PM8834TRSO-8_STM")
      (footprint "eagle-import:SO-8_STM")
      (fields
        (field (name "MANUFACTURER_PART_NUMBER") "PM8834TR")
        (field (name "COPYRIGHT") "Copyright (C) 2025 Ultra Librarian. All rights reserved.")
      )
      (libsource (lib "eagle-import") (part "PM8834TRSO-8_STM"))
    )
    (comp (ref "PHOTO0")
      (value "RPM-075PTT86TRANS_RPM-075P_ROM")
      (footprint "eagle-import:TRANS_RPM-075P_ROM")
      (fields
        (field (name "MANUFACTURER_PART_NUMBER") "RPM-075PTT86")
        (field (name "COPYRIGHT") "Copyright (C) 2025 Ultra Librarian. All rights reserved.")
      )
      (libsource (lib "eagle-import") (part "RPM-075PTT86TRANS_RPM-075P_ROM"))
    )
    (comp (ref "PHOTO1")
      (value "RPM-075PTT86TRANS_RPM-075P_ROM")
      (footprint "eagle-import:TRANS_RPM-075P_ROM")
      (fields
        (field (name "MANUFACTURER_PART_NUMBER") "RPM-075PTT86")
        (field (name "COPYRIGHT") "Copyright (C) 2025 Ultra Librarian. All rights reserved.")
      )
      (libsource (lib "eagle-import") (part "RPM-075PTT86TRANS_RPM-075P_ROM"))
    )
    (comp (ref "PHOTO2")
      (value "RPM-075PTT86TRANS_RPM-075P_ROM")
      (footprint "eagle-import:TRANS_RPM-075P_ROM")
      (fields
        (field (name "MANUFACTURER_PART_NUMBER") "RPM-075PTT86")
        (field (name "COPYRIGHT") "Copyright (C) 2025 Ultra Librarian. All rights reserved.")
      )
      (libsource (lib "eagle-import") (part "RPM-075PTT86TRANS_RPM-075P_ROM"))
    )
    (comp (ref "PHOTO3")
      (value "RPM-075PTT86TRANS_RPM-075P_ROM")
      (footprint "eagle-import:TRANS_RPM-075P_ROM")
      (fields
        (field (name "MANUFACTURER_PART_NUMBER") "RPM-075PTT86")
        (field (name "COPYRIGHT") "Copyright (C) 2025 Ultra Librarian. All rights reserved.")
      )
      (libsource (lib "eagle-import") (part "RPM-075PTT86TRANS_RPM-075P_ROM"))
    )
    (comp (ref "PHOTO4")
      (value "RPM-075PTT86TRANS_RPM-075P_ROM")
      (footprint "eagle-import:TRANS_RPM-075P_ROM")
      (fields
        (field (name "MANUFACTURER_PART_NUMBER") "RPM-075PTT86")
        (field (name "COPYRIGHT") "Copyright (C) 2025 Ultra Librarian. All rights reserved.")
      )
      (libsource (lib "eagle-import") (part "RPM-075PTT86TRANS_RPM-075P_ROM"))
    )
    (comp (ref "PHOTO5")
      (value "RPM-075PTT86TRANS_RPM-075P_ROM")
      (footprint "eagle-import:TRANS_RPM-075P_ROM")
      (fields
        (field (name "MANUFACTURER_PART_NUMBER") "RPM-075PTT86")
        (field (name "COPYRIGHT") "Copyright (C) 2025 Ultra Librarian. All rights reserved.")
      )
      (libsource (lib "eagle-import") (part "RPM-075PTT86TRANS_RPM-075P_ROM"))
    )
    (comp (ref "PHOTO6")
      (value "RPM-075PTT86TRANS_RPM-075P_ROM")
      (footprint "eagle-import:TRANS_RPM-075P_ROM")
      (fields
        (field (name "MANUFACTURER_PART_NUMBER") "RPM-075PTT86")
        (field (name "COPYRIGHT") "Copyright (C) 2025 Ultra Librarian. All rights reserved.")
      )
      (libsource (lib "eagle-import") (part "RPM-075PTT86TRANS_RPM-075P_ROM"))
    )
    (comp (ref "PHOTO7")
      (value "RPM-075PTT86TRANS_RPM-075P_ROM")
      (footprint "eagle-import:TRANS_RPM-075P_ROM")
      (fields
        (field (name "MANUFACTURER_PART_NUMBER") "RPM-075PTT86")
        (field (name "COPYRIGHT") "Copyright (C) 2025 Ultra Librarian. All rights reserved.")
      )
      (libsource (lib "eagle-import") (part "RPM-075PTT86TRANS_RPM-075P_ROM"))
    )
    (comp (ref "PHOTO8")
      (value "RPM-075PTT86TRANS_RPM-075P_ROM")
      (footprint "eagle-import:TRANS_RPM-075P_ROM")
      (fields
        (field (name "MANUFACTURER_PART_NUMBER") "RPM-075PTT86")
        (field (name "COPYRIGHT") "Copyright (C) 2025 Ultra Librarian. All rights reserved.")
      )
      (libsource (lib "eagle-import") (part "RPM-075PTT86TRANS_RPM-075P_ROM"))
    )
    (comp (ref "PHOTO9")
      (value "RPM-075PTT86TRANS_RPM-075P_ROM")
      (footprint "eagle-import:TRANS_RPM-075P_ROM")
      (fields
        (field (name "MANUFACTURER_PART_NUMBER") "RPM-075PTT86")
        (field (name "COPYRIGHT") "Copyright (C) 2025 Ultra Librarian. All rights reserved.")
      )
      (libsource (lib "eagle-import") (part "RPM-075PTT86TRANS_RPM-075P_ROM"))
    )
    (comp (ref "PHOTO10")
      (value "RPM-075PTT86TRANS_RPM-075P_ROM")
      (footprint "eagle-import:TRANS_RPM-075P_ROM")
      (fields
        (field (name "MANUFACTURER_PART_NUMBER") "RPM-075PTT86")
        (field (name "COPYRIGHT") "Copyright (C) 2025 Ultra Librarian. All rights reserved.")
      )
      (libsource (lib "eagle-import") (part "RPM-075PTT86TRANS_RPM-075P_ROM"))
    )
    (comp (ref "PHOTO11")
      (value "RPM-075PTT86TRANS_RPM-075P_ROM")
      (footprint "eagle-import:TRANS_RPM-075P_ROM")
      (fields
        (field (name "MANUFACTURER_PART_NUMBER") "RPM-075PTT86")
        (field (name "COPYRIGHT") "Copyright (C) 2025 Ultra Librarian. All rights reserved.")
      )
      (libsource (lib "eagle-import") (part "RPM-075PTT86TRANS_RPM-075P_ROM"))
    )
    (comp (ref "PHOTO12")
      (value "RPM-075PTT86TRANS_RPM-075P_ROM")
      (footprint "eagle-import:TRANS_RPM-075P_ROM")
      (fields
        (field (name "MANUFACTURER_PART_NUMBER") "RPM-075PTT86")
        (field (name "COPYRIGHT") "Copyright (C) 2025 Ultra Librarian. All rights reserved.")
      )
      (libsource (lib "eagle-import") (part "RPM-075PTT86TRANS_RPM-075P_ROM"))
    )
    (comp (ref "PHOTO13")
      (value "RPM-075PTT86TRANS_RPM-075P_ROM")
      (footprint "eagle-import:TRANS_RPM-075P_ROM")
      (fields
        (field (name "MANUFACTURER_PART_NUMBER") "RPM-075PTT86")
        (field (name "COPYRIGHT") "Copyright (C) 2025 Ultra Librarian. All rights reserved.")
      )
      (libsource (lib "eagle-import") (part "RPM-075PTT86TRANS_RPM-075P_ROM"))
    )
    (comp (ref "PHOTO14")
      (value "RPM-075PTT86TRANS_RPM-075P_ROM")
      (footprint "eagle-import:TRANS_RPM-075P_ROM")
      (fields
        (field (name "MANUFACTURER_PART_NUMBER") "RPM-075PTT86")
        (field (name "COPYRIGHT") "Copyright (C) 2025 Ultra Librarian. All rights reserved.")
      )
      (libsource (lib "eagle-import") (part "RPM-075PTT86TRANS_RPM-075P_ROM"))
    )
    (comp (ref "PHOTO15")
      (value "RPM-075PTT86TRANS_RPM-075P_ROM")
      (footprint "eagle-import:TRANS_RPM-075P_ROM")
      (fields
        (field (name "MANUFACTURER_PART_NUMBER") "RPM-075PTT86")
        (field (name "COPYRIGHT") "Copyright (C) 2025 Ultra Librarian. All rights reserved.")
      )
      (libsource (lib "eagle-import") (part "RPM-075PTT86TRANS_RPM-075P_ROM"))
    )
    (comp (ref "PHOTO16")
      (value "RPM-075PTT86TRANS_RPM-075P_ROM")
      (footprint "eagle-import:TRANS_RPM-075P_ROM")
      (fields
        (field (name "MANUFACTURER_PART_NUMBER") "RPM-075PTT86")
        (field (name "COPYRIGHT") "Copyright (C) 2025 Ultra Librarian. All rights reserved.")
      )
      (libsource (lib "eagle-import") (part "RPM-075PTT86TRANS_RPM-075P_ROM"))
    )
    (comp (ref "PHOTO17")
      (value "RPM-075PTT86TRANS_RPM-075P_ROM")
      (footprint "eagle-import:TRANS_RPM-075P_ROM")
      (fields
        (field (name "MANUFACTURER_PART_NUMBER") "RPM-075PTT86")
        (field (name "COPYRIGHT") "Copyright (C) 2025 Ultra Librarian. All rights reserved.")
      )
      (libsource (lib "eagle-import") (part "RPM-075PTT86TRANS_RPM-075P_ROM"))
    )
    (comp (ref "PHOTO18")
      (value "RPM-075PTT86TRANS_RPM-075P_ROM")
      (footprint "eagle-import:TRANS_RPM-075P_ROM")
      (fields
        (field (name "MANUFACTURER_PART_NUMBER") "RPM-075PTT86")
        (field (name "COPYRIGHT") "Copyright (C) 2025 Ultra Librarian. All rights reserved.")
      )
      (libsource (lib "eagle-import") (part "RPM-075PTT86TRANS_RPM-075P_ROM"))
    )
    (comp (ref "PHOTO19")
      (value "RPM-075PTT86TRANS_RPM-075P_ROM")
      (footprint "eagle-import:TRANS_RPM-075P_ROM")
      (fields
        (field (name "MANUFACTURER_PART_NUMBER") "RPM-075PTT86")
        (field (name "COPYRIGHT") "Copyright (C) 2025 Ultra Librarian. All rights reserved.")
      )
      (libsource (lib "eagle-import") (part "RPM-075PTT86TRANS_RPM-075P_ROM"))
    )
    (comp (ref "PHOTO20")
      (value "RPM-075PTT86TRANS_RPM-075P_ROM")
      (footprint "eagle-import:TRANS_RPM-075P_ROM")
      (fields
        (field (name "MANUFACTURER_PART_NUMBER") "RPM-075PTT86")
        (field (name "COPYRIGHT") "Copyright (C) 2025 Ultra Librarian. All rights reserved.")
      )
      (libsource (lib "eagle-import") (part "RPM-075PTT86TRANS_RPM-075P_ROM"))
    )
    (comp (ref "PHOTO21")
      (value "RPM-075PTT86TRANS_RPM-075P_ROM")
      (footprint "eagle-import:TRANS_RPM-075P_ROM")
      (fields
        (field (name "MANUFACTURER_PART_NUMBER") "RPM-075PTT86")
        (field (name "COPYRIGHT") "Copyright (C) 2025 Ultra Librarian. All rights reserved.")
      )
      (libsource (lib "eagle-import") (part "RPM-075PTT86TRANS_RPM-075P_ROM"))
    )
    (comp (ref "PHOTO22")
      (value "RPM-075PTT86TRANS_RPM-075P_ROM")
      (footprint "eagle-import:TRANS_RPM-075P_ROM")
      (fields
        (field (name "MANUFACTURER_PART_NUMBER") "RPM-075PTT86")
        (field (name "COPYRIGHT") "Copyright (C) 2025 Ultra Librarian. All rights reserved.")
      )
      (libsource (lib "eagle-import") (part "RPM-075PTT86TRANS_RPM-075P_ROM"))
    )
    (comp (ref "PHOTO23")
      (value "RPM-075PTT86TRANS_RPM-075P_ROM")
      (footprint "eagle-import:TRANS_RPM-075P_ROM")
      (fields
        (field (name "MANUFACTURER_PART_NUMBER") "RPM-075PTT86")
        (field (name "COPYRIGHT") "Copyright (C) 2025 Ultra Librarian. All rights reserved.")
      )
      (libsource (lib "eagle-import") (part "RPM-075PTT86TRANS_RPM-075P_ROM"))
    )
    (comp (ref "PHOTO24")
      (value "RPM-075PTT86TRANS_RPM-075P_ROM")
      (footprint "eagle-import:TRANS_RPM-075P_ROM")
      (fields
        (field (name "MANUFACTURER_PART_NUMBER") "RPM-075PTT86")
        (field (name "COPYRIGHT") "Copyright (C) 2025 Ultra Librarian. All rights reserved.")
      )
      (libsource (lib "eagle-import") (part "RPM-075PTT86TRANS_RPM-075P_ROM"))
    )
    (comp (ref "PHOTO25")
      (value "RPM-075PTT86TRANS_RPM-075P_ROM")
      (footprint "eagle-import:TRANS_RPM-075P_ROM")
      (fields
        (field (name "MANUFACTURER_PART_NUMBER") "RPM-075PTT86")
        (field (name "COPYRIGHT") "Copyright (C) 2025 Ultra Librarian. All rights reserved.")
      )
      (libsource (lib "eagle-import") (part "RPM-075PTT86TRANS_RPM-075P_ROM"))
    )
    (comp (ref "PHOTO26")
      (value "RPM-075PTT86TRANS_RPM-075P_ROM")
      (footprint "eagle-import:TRANS_RPM-075P_ROM")
      (fields
        (field (name "MANUFACTURER_PART_NUMBER") "RPM-075PTT86")
        (field (name "COPYRIGHT") "Copyright (C) 2025 Ultra Librarian. All rights reserved.")
      )
      (libsource (lib "eagle-import") (part "RPM-075PTT86TRANS_RPM-075P_ROM"))
    )
    (comp (ref "PHOTO27")
      (value "RPM-075PTT86TRANS_RPM-075P_ROM")
      (footprint "eagle-import:TRANS_RPM-075P_ROM")
      (fields
        (field (name "MANUFACTURER_PART_NUMBER") "RPM-075PTT86")
        (field (name "COPYRIGHT") "Copyright (C) 2025 Ultra Librarian. All rights reserved.")
      )
      (libsource (lib "eagle-import") (part "RPM-075PTT86TRANS_RPM-075P_ROM"))
    )
    (comp (ref "PHOTO28")
      (value "RPM-075PTT86TRANS_RPM-075P_ROM")
      (footprint "eagle-import:TRANS_RPM-075P_ROM")
      (fields
        (field (name "MANUFACTURER_PART_NUMBER") "RPM-075PTT86")
        (field (name "COPYRIGHT") "Copyright (C) 2025 Ultra Librarian. All rights reserved.")
      )
      (libsource (lib "eagle-import") (part "RPM-075PTT86TRANS_RPM-075P_ROM"))
    )
    (comp (ref "PHOTO29")
      (value "RPM-075PTT86TRANS_RPM-075P_ROM")
      (footprint "eagle-import:TRANS_RPM-075P_ROM")
      (fields
        (field (name "MANUFACTURER_PART_NUMBER") "RPM-075PTT86")
        (field (name "COPYRIGHT") "Copyright (C) 2025 Ultra Librarian. All rights reserved.")
      )
      (libsource (lib "eagle-import") (part "RPM-075PTT86TRANS_RPM-075P_ROM"))
    )
    (comp (ref "PHOTO30")
      (value "RPM-075PTT86TRANS_RPM-075P_ROM")
      (footprint "eagle-import:TRANS_RPM-075P_ROM")
      (fields
        (field (name "MANUFACTURER_PART_NUMBER") "RPM-075PTT86")
        (field (name "COPYRIGHT") "Copyright (C) 2025 Ultra Librarian. All rights reserved.")
      )
      (libsource (lib "eagle-import") (part "RPM-075PTT86TRANS_RPM-075P_ROM"))
    )
    (comp (ref "PHOTO31")
      (value "RPM-075PTT86TRANS_RPM-075P_ROM")
      (footprint "eagle-import:TRANS_RPM-075P_ROM")
      (fields
        (field (name "MANUFACTURER_PART_NUMBER") "RPM-075PTT86")
        (field (name "COPYRIGHT") "Copyright (C) 2025 Ultra Librarian. All rights reserved.")
      )
      (libsource (lib "eagle-import") (part "RPM-075PTT86TRANS_RPM-075P_ROM"))
    )
    (comp (ref "PHOTO32")
      (value "RPM-075PTT86TRANS_RPM-075P_ROM")
      (footprint "eagle-import:TRANS_RPM-075P_ROM")
      (fields
        (field (name "MANUFACTURER_PART_NUMBER") "RPM-075PTT86")
        (field (name "COPYRIGHT") "Copyright (C) 2025 Ultra Librarian. All rights reserved.")
      )
      (libsource (lib "eagle-import") (part "RPM-075PTT86TRANS_RPM-075P_ROM"))
    )
    (comp (ref "PHOTO33")
      (value "RPM-075PTT86TRANS_RPM-075P_ROM")
      (footprint "eagle-import:TRANS_RPM-075P_ROM")
      (fields
        (field (name "MANUFACTURER_PART_NUMBER") "RPM-075PTT86")
        (field (name "COPYRIGHT") "Copyright (C) 2025 Ultra Librarian. All rights reserved.")
      )
      (libsource (lib "eagle-import") (part "RPM-075PTT86TRANS_RPM-075P_ROM"))
    )
    (comp (ref "PHOTO34")
      (value "RPM-075PTT86TRANS_RPM-075P_ROM")
      (footprint "eagle-import:TRANS_RPM-075P_ROM")
      (fields
        (field (name "MANUFACTURER_PART_NUMBER") "RPM-075PTT86")
        (field (name "COPYRIGHT") "Copyright (C) 2025 Ultra Librarian. All rights reserved.")
      )
      (libsource (lib "eagle-import") (part "RPM-075PTT86TRANS_RPM-075P_ROM"))
    )
    (comp (ref "PHOTO35")
      (value "RPM-075PTT86TRANS_RPM-075P_ROM")
      (footprint "eagle-import:TRANS_RPM-075P_ROM")
      (fields
        (field (name "MANUFACTURER_PART_NUMBER") "RPM-075PTT86")
        (field (name "COPYRIGHT") "Copyright (C) 2025 Ultra Librarian. All rights reserved.")
      )
      (libsource (lib "eagle-import") (part "RPM-075PTT86TRANS_RPM-075P_ROM"))
    )
    (comp (ref "PHOTO36")
      (value "RPM-075PTT86TRANS_RPM-075P_ROM")
      (footprint "eagle-import:TRANS_RPM-075P_ROM")
      (fields
        (field (name "MANUFACTURER_PART_NUMBER") "RPM-075PTT86")
        (field (name "COPYRIGHT") "Copyright (C) 2025 Ultra Librarian. All rights reserved.")
      )
      (libsource (lib "eagle-import") (part "RPM-075PTT86TRANS_RPM-075P_ROM"))
    )
    (comp (ref "PHOTO37")
      (value "RPM-075PTT86TRANS_RPM-075P_ROM")
      (footprint "eagle-import:TRANS_RPM-075P_ROM")
      (fields
        (field (name "MANUFACTURER_PART_NUMBER") "RPM-075PTT86")
        (field (name "COPYRIGHT") "Copyright (C) 2025 Ultra Librarian. All rights reserved.")
      )
      (libsource (lib "eagle-import") (part "RPM-075PTT86TRANS_RPM-075P_ROM"))
    )
    (comp (ref "PHOTO38")
      (value "RPM-075PTT86TRANS_RPM-075P_ROM")
      (footprint "eagle-import:TRANS_RPM-075P_ROM")
      (fields
        (field (name "MANUFACTURER_PART_NUMBER") "RPM-075PTT86")
        (field (name "COPYRIGHT") "Copyright (C) 2025 Ultra Librarian. All rights reserved.")
      )
      (libsource (lib "eagle-import") (part "RPM-075PTT86TRANS_RPM-075P_ROM"))
    )
    (comp (ref "PHOTO39")
      (value "RPM-075PTT86TRANS_RPM-075P_ROM")
      (footprint "eagle-import:TRANS_RPM-075P_ROM")
      (fields
        (field (name "MANUFACTURER_PART_NUMBER") "RPM-075PTT86")
        (field (name "COPYRIGHT") "Copyright (C) 2025 Ultra Librarian. All rights reserved.")
      )
      (libsource (lib "eagle-import") (part "RPM-075PTT86TRANS_RPM-075P_ROM"))
    )
    (comp (ref "PHOTO40")
      (value "RPM-075PTT86TRANS_RPM-075P_ROM")
      (footprint "eagle-import:TRANS_RPM-075P_ROM")
      (fields
        (field (name "MANUFACTURER_PART_NUMBER") "RPM-075PTT86")
        (field (name "COPYRIGHT") "Copyright (C) 2025 Ultra Librarian. All rights reserved.")
      )
      (libsource (lib "eagle-import") (part "RPM-075PTT86TRANS_RPM-075P_ROM"))
    )
    (comp (ref "PHOTO41")
      (value "RPM-075PTT86TRANS_RPM-075P_ROM")
      (footprint "eagle-import:TRANS_RPM-075P_ROM")
      (fields
        (field (name "MANUFACTURER_PART_NUMBER") "RPM-075PTT86")
        (field (name "COPYRIGHT") "Copyright (C) 2025 Ultra Librarian. All rights reserved.")
      )
      (libsource (lib "eagle-import") (part "RPM-075PTT86TRANS_RPM-075P_ROM"))
    )
    (comp (ref "PHOTO42")
      (value "RPM-075PTT86TRANS_RPM-075P_ROM")
      (footprint "eagle-import:TRANS_RPM-075P_ROM")
      (fields
        (field (name "MANUFACTURER_PART_NUMBER") "RPM-075PTT86")
        (field (name "COPYRIGHT") "Copyright (C) 2025 Ultra Librarian. All rights reserved.")
      )
      (libsource (lib "eagle-import") (part "RPM-075PTT86TRANS_RPM-075P_ROM"))
    )
    (comp (ref "PHOTO43")
      (value "RPM-075PTT86TRANS_RPM-075P_ROM")
      (footprint "eagle-import:TRANS_RPM-075P_ROM")
      (fields
        (field (name "MANUFACTURER_PART_NUMBER") "RPM-075PTT86")
        (field (name "COPYRIGHT") "Copyright (C) 2025 Ultra Librarian. All rights reserved.")
      )
      (libsource (lib "eagle-import") (part "RPM-075PTT86TRANS_RPM-075P_ROM"))
    )
    (comp (ref "PHOTO44")
      (value "RPM-075PTT86TRANS_RPM-075P_ROM")
      (footprint "eagle-import:TRANS_RPM-075P_ROM")
      (fields
        (field (name "MANUFACTURER_PART_NUMBER") "RPM-075PTT86")
        (field (name "COPYRIGHT") "Copyright (C) 2025 Ultra Librarian. All rights reserved.")
      )
      (libsource (lib "eagle-import") (part "RPM-075PTT86TRANS_RPM-075P_ROM"))
    )
    (comp (ref "PHOTO45")
      (value "RPM-075PTT86TRANS_RPM-075P_ROM")
      (footprint "eagle-import:TRANS_RPM-075P_ROM")
      (fields
        (field (name "MANUFACTURER_PART_NUMBER") "RPM-075PTT86")
        (field (name "COPYRIGHT") "Copyright (C) 2025 Ultra Librarian. All rights reserved.")
      )
      (libsource (lib "eagle-import") (part "RPM-075PTT86TRANS_RPM-075P_ROM"))
    )
    (comp (ref "PHOTO46")
      (value "RPM-075PTT86TRANS_RPM-075P_ROM")
      (footprint "eagle-import:TRANS_RPM-075P_ROM")
      (fields
        (field (name "MANUFACTURER_PART_NUMBER") "RPM-075PTT86")
        (field (name "COPYRIGHT") "Copyright (C) 2025 Ultra Librarian. All rights reserved.")
      )
      (libsource (lib "eagle-import") (part "RPM-075PTT86TRANS_RPM-075P_ROM"))
    )
    (comp (ref "PHOTO47")
      (value "RPM-075PTT86TRANS_RPM-075P_ROM")
      (footprint "eagle-import:TRANS_RPM-075P_ROM")
      (fields
        (field (name "MANUFACTURER_PART_NUMBER") "RPM-075PTT86")
        (field (name "COPYRIGHT") "Copyright (C) 2025 Ultra Librarian. All rights reserved.")
      )
      (libsource (lib "eagle-import") (part "RPM-075PTT86TRANS_RPM-075P_ROM"))
    )
    (comp (ref "POWER_CONN")
      (value "XT30UPB-M")
      (footprint "eagle-import:AMASS_XT30UPB-M")
      (fields (field (name "MF") "amass"))
      (libsource (lib "eagle-import") (part "XT30UPB-M"))
    )
    (comp (ref "QF")
      (value "IRF520")
      (footprint "eagle-import:TO220BV")
      (fields (field (name "MANUFACTURER") "Infineon Technologies") (field (name "MPN") "IRF520NPBF"))
      (libsource (lib "eagle-import") (part "NMOSFET__TO220IRF520"))
    )
    (comp (ref "QR")
      (value "IRF520")
      (footprint "eagle-import:TO220BV")
      (fields (field (name "MANUFACTURER") "Infineon Technologies") (field (name "MPN") "IRF520NPBF"))
      (libsource (lib "eagle-import") (part "NMOSFET__TO220IRF520"))
    )
    (comp (ref "R0")
      (value "10k")
      (footprint "eagle-import:RESC2012X65")
      (libsource (lib "eagle-import") (part "RCHIP-0805(2012-METRIC)_"))
    )
    (comp (ref "R1")
      (value "10k")
      (footprint "eagle-import:RESC2012X65")
      (libsource (lib "eagle-import") (part "RCHIP-0805(2012-METRIC)_"))
    )
    (comp (ref "R2")
      (value "10k")
      (footprint "eagle-import:RESC2012X65")
      (libsource (lib "eagle-import") (part "RCHIP-0805(2012-METRIC)_"))
    )
    (comp (ref "R3")
      (value "10k")
      (footprint "eagle-import:RESC2012X65")
      (libsource (lib "eagle-import") (part "RCHIP-0805(2012-METRIC)_"))
    )
    (comp (ref "R4")
      (value "10k")
      (footprint "eagle-import:RESC2012X65")
      (libsource (lib "eagle-import") (part "RCHIP-0805(2012-METRIC)_"))
    )
    (comp (ref "R5")
      (value "10k")
      (footprint "eagle-import:RESC2012X65")
      (libsource (lib "eagle-import") (part "RCHIP-0805(2012-METRIC)_"))
    )
    (comp (ref "R6")
      (value "10k")
      (footprint "eagle-import:RESC2012X65")
      (libsource (lib "eagle-import") (part "RCHIP-0805(2012-METRIC)_"))
    )
    (comp (ref "R7")
      (value "10k")
      (footprint "eagle-import:RESC2012X65")
      (libsource (lib "eagle-import") (part "RCHIP-0805(2012-METRIC)_"))
    )
    (comp (ref "R8")
      (value "10k")
      (footprint "eagle-import:RESC2012X65")
      (libsource (lib "eagle-import") (part "RCHIP-0805(2012-METRIC)_"))
    )
    (comp (ref "R9")
      (value "10k")
      (footprint "eagle-import:RESC2012X65")
      (libsource (lib "eagle-import") (part "RCHIP-0805(2012-METRIC)_"))
    )
    (comp (ref "R10")
      (value "10k")
      (footprint "eagle-import:RESC2012X65")
      (libsource (lib "eagle-import") (part "RCHIP-0805(2012-METRIC)_"))
    )
    (comp (ref "R11")
      (value "10k")
      (footprint "eagle-import:RESC2012X65")
      (libsource (lib "eagle-import") (part "RCHIP-0805(2012-METRIC)_"))
    )
    (comp (ref "R12")
      (value "10k")
      (footprint "eagle-import:RESC2012X65")
      (libsource (lib "eagle-import") (part "RCHIP-0805(2012-METRIC)_"))
    )
    (comp (ref "R13")
      (value "10k")
      (footprint "eagle-import:RESC2012X65")
      (libsource (lib "eagle-import") (part "RCHIP-0805(2012-METRIC)_"))
    )
    (comp (ref "R14")
      (value "10k")
      (footprint "eagle-import:RESC2012X65")
      (libsource (lib "eagle-import") (part "RCHIP-0805(2012-METRIC)_"))
    )
    (comp (ref "R15")
      (value "10k")
      (footprint "eagle-import:RESC2012X65")
      (libsource (lib "eagle-import") (part "RCHIP-0805(2012-METRIC)_"))
    )
    (comp (ref "R16")
      (value "10k")
      (footprint "eagle-import:RESC2012X65")
      (libsource (lib "eagle-import") (part "RCHIP-0805(2012-METRIC)_"))
    )
    (comp (ref "R17")
      (value "10k")
      (footprint "eagle-import:RESC2012X65")
      (libsource (lib "eagle-import") (part "RCHIP-0805(2012-METRIC)_"))
    )
    (comp (ref "R18")
      (value "10k")
      (footprint "eagle-import:RESC2012X65")
      (libsource (lib "eagle-import") (part "RCHIP-0805(2012-METRIC)_"))
    )
    (comp (ref "R19")
      (value "10k")
      (footprint "eagle-import:RESC2012X65")
      (libsource (lib "eagle-import") (part "RCHIP-0805(2012-METRIC)_"))
    )
    (comp (ref "R20")
      (value "10k")
      (footprint "eagle-import:RESC2012X65")
      (libsource (lib "eagle-import") (part "RCHIP-0805(2012-METRIC)_"))
    )
    (comp (ref "R21")
      (value "10k")
      (footprint "eagle-import:RESC2012X65")
      (libsource (lib "eagle-import") (part "RCHIP-0805(2012-METRIC)_"))
    )
    (comp (ref "R22")
      (value "10k")
      (footprint "eagle-import:RESC2012X65")
      (libsource (lib "eagle-import") (part "RCHIP-0805(2012-METRIC)_"))
    )
    (comp (ref "R23")
      (value "10k")
      (footprint "eagle-import:RESC2012X65")
      (libsource (lib "eagle-import") (part "RCHIP-0805(2012-METRIC)_"))
    )
    (comp (ref "R24")
      (value "10k")
      (footprint "eagle-import:RESC2012X65")
      (libsource (lib "eagle-import") (part "RCHIP-0805(2012-METRIC)_"))
    )
    (comp (ref "R25")
      (value "10k")
      (footprint "eagle-import:RESC2012X65")
      (libsource (lib "eagle-import") (part "RCHIP-0805(2012-METRIC)_"))
    )
    (comp (ref "R26")
      (value "10k")
      (footprint "eagle-import:RESC2012X65")
      (libsource (lib "eagle-import") (part "RCHIP-0805(2012-METRIC)_"))
    )
    (comp (ref "R27")
      (value "10k")
      (footprint "eagle-import:RESC2012X65")
      (libsource (lib "eagle-import") (part "RCHIP-0805(2012-METRIC)_"))
    )
    (comp (ref "R28")
      (value "10k")
      (footprint "eagle-import:RESC2012X65")
      (libsource (lib "eagle-import") (part "RCHIP-0805(2012-METRIC)_"))
    )
    (comp (ref "R29")
      (value "10k")
      (footprint "eagle-import:RESC2012X65")
      (libsource (lib "eagle-import") (part "RCHIP-0805(2012-METRIC)_"))
    )
    (comp (ref "R30")
      (value "10k")
      (footprint "eagle-import:RESC2012X65")
      (libsource (lib "eagle-import") (part "RCHIP-0805(2012-METRIC)_"))
    )
    (comp (ref "R31")
      (value "10k")
      (footprint "eagle-import:RESC2012X65")
      (libsource (lib "eagle-import") (part "RCHIP-0805(2012-METRIC)_"))
    )
    (comp (ref "R32")
      (value "10k")
      (footprint "eagle-import:RESC2012X65")
      (libsource (lib "eagle-import") (part "RCHIP-0805(2012-METRIC)_"))
    )
    (comp (ref "R33")
      (value "10k")
      (footprint "eagle-import:RESC2012X65")
      (libsource (lib "eagle-import") (part "RCHIP-0805(2012-METRIC)_"))
    )
    (comp (ref "R34")
      (value "10k")
      (footprint "eagle-import:RESC2012X65")
      (libsource (lib "eagle-import") (part "RCHIP-0805(2012-METRIC)_"))
    )
    (comp (ref "R35")
      (value "10k")
      (footprint "eagle-import:RESC2012X65")
      (libsource (lib "eagle-import") (part "RCHIP-0805(2012-METRIC)_"))
    )
    (comp (ref "R36")
      (value "10k")
      (footprint "eagle-import:RESC2012X65")
      (libsource (lib "eagle-import") (part "RCHIP-0805(2012-METRIC)_"))
    )
    (comp (ref "R37")
      (value "10k")
      (footprint "eagle-import:RESC2012X65")
      (libsource (lib "eagle-import") (part "RCHIP-0805(2012-METRIC)_"))
    )
    (comp (ref "R38")
      (value "10k")
      (footprint "eagle-import:RESC2012X65")
      (libsource (lib "eagle-import") (part "RCHIP-0805(2012-METRIC)_"))
    )
    (comp (ref "R39")
      (value "10k")
      (footprint "eagle-import:RESC2012X65")
      (libsource (lib "eagle-import") (part "RCHIP-0805(2012-METRIC)_"))
    )
    (comp (ref "R40")
      (value "10k")
      (footprint "eagle-import:RESC2012X65")
      (libsource (lib "eagle-import") (part "RCHIP-0805(2012-METRIC)_"))
    )
    (comp (ref "R41")
      (value "10k")
      (footprint "eagle-import:RESC2012X65")
      (libsource (lib "eagle-import") (part "RCHIP-0805(2012-METRIC)_"))
    )
    (comp (ref "R42")
      (value "10k")
      (footprint "eagle-import:RESC2012X65")
      (libsource (lib "eagle-import") (part "RCHIP-0805(2012-METRIC)_"))
    )
    (comp (ref "R43")
      (value "10k")
      (footprint "eagle-import:RESC2012X65")
      (libsource (lib "eagle-import") (part "RCHIP-0805(2012-METRIC)_"))
    )
    (comp (ref "R44")
      (value "10k")
      (footprint "eagle-import:RESC2012X65")
      (libsource (lib "eagle-import") (part "RCHIP-0805(2012-METRIC)_"))
    )
    (comp (ref "R45")
      (value "10k")
      (footprint "eagle-import:RESC2012X65")
      (libsource (lib "eagle-import") (part "RCHIP-0805(2012-METRIC)_"))
    )
    (comp (ref "R46")
      (value "10k")
      (footprint "eagle-import:RESC2012X65")
      (libsource (lib "eagle-import") (part "RCHIP-0805(2012-METRIC)_"))
    )
    (comp (ref "R47")
      (value "10k")
      (footprint "eagle-import:RESC2012X65")
      (libsource (lib "eagle-import") (part "RCHIP-0805(2012-METRIC)_"))
    )
    (comp (ref "R48")
      (value "4R7")
      (footprint "eagle-import:RESC2012X65")
      (libsource (lib "eagle-import") (part "RCHIP-0805(2012-METRIC)_"))
    )
    (comp (ref "R49")
      (value "4R7")
      (footprint "eagle-import:RESC2012X65")
      (libsource (lib "eagle-import") (part "RCHIP-0805(2012-METRIC)_"))
    )
    (comp (ref "R97")
      (value "100k")
      (footprint "eagle-import:RESC2012X65")
      (libsource (lib "eagle-import") (part "RCHIP-0805(2012-METRIC)_"))
    )
    (comp (ref "R98")
      (value "100k")
      (footprint "eagle-import:RESC2012X65")
      (libsource (lib "eagle-import") (part "RCHIP-0805(2012-METRIC)_"))
    )
    (comp (ref "XMUX")
      (value "CD74HC4067SM96")
      (footprint "eagle-import:SOP65P780X200-24N")
      (libsource (lib "eagle-import") (part "CD74HC4067SM96"))
    )
  )
  (nets
    (net (code "1") (name "+5V") (class "Default")
      (node (ref "AENC") (pin "A2") (pinfunction "2_A2") (pintype "bidirectional"))
      (node (ref "AHAL") (pin "B5") (pinfunction "5_B5") (pintype "bidirectional"))
      (node (ref "AMD") (pin "6") (pinfunction "5V(POWER_SUPPLY)_6") (pintype "bidirectional"))
      (node (ref "BENC") (pin "A2") (pinfunction "2_A2") (pintype "bidirectional"))
      (node (ref "BHAL") (pin "B5") (pinfunction "5_B5") (pintype "bidirectional"))
      (node (ref "BMD") (pin "6") (pinfunction "5V(POWER_SUPPLY)_6") (pintype "bidirectional"))
      (node (ref "C1") (pin "1") (pinfunction "1_1") (pintype "passive"))
      (node (ref "C101") (pin "1") (pinfunction "1_1") (pintype "passive"))
      (node (ref "C105") (pin "1") (pinfunction "1_1") (pintype "passive"))
      (node (ref "C109") (pin "1") (pinfunction "1_1") (pintype "passive"))
      (node (ref "C113") (pin "1") (pinfunction "1_1") (pintype "passive"))
      (node (ref "C17") (pin "1") (pinfunction "1_1") (pintype "passive"))
      (node (ref "C25") (pin "1") (pinfunction "1_1") (pintype "passive"))
      (node (ref "C9") (pin "1") (pinfunction "1_1") (pintype "passive"))
      (node (ref "CENC") (pin "A2") (pinfunction "2_A2") (pintype "bidirectional"))
      (node (ref "CHAL") (pin "B5") (pinfunction "5_B5") (pintype "bidirectional"))
      (node (ref "CMD") (pin "6") (pinfunction "5V(POWER_SUPPLY)_6") (pintype "bidirectional"))
      (node (ref "DENC") (pin "A2") (pinfunction "2_A2") (pintype "bidirectional"))
      (node (ref "DHAL") (pin "B5") (pinfunction "5_B5") (pintype "bidirectional"))
      (node (ref "DMD") (pin "6") (pinfunction "5V(POWER_SUPPLY)_6") (pintype "bidirectional"))
      (node (ref "LED0") (pin "4") (pinfunction "VDD_4") (pintype "power_in"))
      (node (ref "LED1") (pin "4") (pinfunction "VDD_4") (pintype "power_in"))
      (node (ref "LED10") (pin "4") (pinfunction "VDD_4") (pintype "power_in"))
      (node (ref "LED11") (pin "4") (pinfunction "VDD_4") (pintype "power_in"))
      (node (ref "LED12") (pin "4") (pinfunction "VDD_4") (pintype "power_in"))
      (node (ref "LED13") (pin "4") (pinfunction "VDD_4") (pintype "power_in"))
      (node (ref "LED14") (pin "4") (pinfunction "VDD_4") (pintype "power_in"))
      (node (ref "LED15") (pin "4") (pinfunction "VDD_4") (pintype "power_in"))
      (node (ref "LED16") (pin "4") (pinfunction "VDD_4") (pintype "power_in"))
      (node (ref "LED17") (pin "4") (pinfunction "VDD_4") (pintype "power_in"))
      (node (ref "LED18") (pin "4") (pinfunction "VDD_4") (pintype "power_in"))
      (node (ref "LED19") (pin "4") (pinfunction "VDD_4") (pintype "power_in"))
      (node (ref "LED2") (pin "4") (pinfunction "VDD_4") (pintype "power_in"))
      (node (ref "LED20") (pin "4") (pinfunction "VDD_4") (pintype "power_in"))
      (node (ref "LED21") (pin "4") (pinfunction "VDD_4") (pintype "power_in"))
      (node (ref "LED22") (pin "4") (pinfunction "VDD_4") (pintype "power_in"))
      (node (ref "LED23") (pin "4") (pinfunction "VDD_4") (pintype "power_in"))
      (node (ref "LED24") (pin "4") (pinfunction "VDD_4") (pintype "power_in"))
      (node (ref "LED25") (pin "4") (pinfunction "VDD_4") (pintype "power_in"))
      (node (ref "LED26") (pin "4") (pinfunction "VDD_4") (pintype "power_in"))
      (node (ref "LED27") (pin "4") (pinfunction "VDD_4") (pintype "power_in"))
      (node (ref "LED28") (pin "4") (pinfunction "VDD_4") (pintype "power_in"))
      (node (ref "LED29") (pin "4") (pinfunction "VDD_4") (pintype "power_in"))
      (node (ref "LED3") (pin "4") (pinfunction "VDD_4") (pintype "power_in"))
      (node (ref "LED30") (pin "4") (pinfunction "VDD_4") (pintype "power_in"))
      (node (ref "LED31") (pin "4") (pinfunction "VDD_4") (pintype "power_in"))
      (node (ref "LED32") (pin "4") (pinfunction "VDD_4") (pintype "power_in"))
      (node (ref "LED33") (pin "4") (pinfunction "VDD_4") (pintype "power_in"))
      (node (ref "LED34") (pin "4") (pinfunction "VDD_4") (pintype "power_in"))
      (node (ref "LED35") (pin "4") (pinfunction "VDD_4") (pintype "power_in"))
      (node (ref "LED36") (pin "4") (pinfunction "VDD_4") (pintype "power_in"))
      (node (ref "LED37") (pin "4") (pinfunction "VDD_4") (pintype "power_in"))
      (node (ref "LED38") (pin "4") (pinfunction "VDD_4") (pintype "power_in"))
      (node (ref "LED39") (pin "4") (pinfunction "VDD_4") (pintype "power_in"))
      (node (ref "LED4") (pin "4") (pinfunction "VDD_4") (pintype "power_in"))
      (node (ref "LED40") (pin "4") (pinfunction "VDD_4") (pintype "power_in"))
      (node (ref "LED41") (pin "4") (pinfunction "VDD_4") (pintype "power_in"))
      (node (ref "LED42") (pin "4") (pinfunction "VDD_4") (pintype "power_in"))
      (node (ref "LED43") (pin "4") (pinfunction "VDD_4") (pintype "power_in"))
      (node (ref "LED44") (pin "4") (pinfunction "VDD_4") (pintype "power_in"))
      (node (ref "LED45") (pin "4") (pinfunction "VDD_4") (pintype "power_in"))
      (node (ref "LED46") (pin "4") (pinfunction "VDD_4") (pintype "power_in"))
      (node (ref "LED47") (pin "4") (pinfunction "VDD_4") (pintype "power_in"))
      (node (ref "LED5") (pin "4") (pinfunction "VDD_4") (pintype "power_in"))
      (node (ref "LED6") (pin "4") (pinfunction "VDD_4") (pintype "power_in"))
      (node (ref "LED7") (pin "4") (pinfunction "VDD_4") (pintype "power_in"))
      (node (ref "LED8") (pin "4") (pinfunction "VDD_4") (pintype "power_in"))
      (node (ref "LED9") (pin "4") (pinfunction "VDD_4") (pintype "power_in"))
      (node (ref "MAIN_CONN_A") (pin "1") (pinfunction "1_1") (pintype "passive"))
      (node (ref "MAIN_CONN_B") (pin "1") (pinfunction "1_1") (pintype "passive"))
      (node (ref "MAIN_CONN_C") (pin "1") (pinfunction "1_1") (pintype "passive"))
      (node (ref "MAIN_CONN_D") (pin "1") (pinfunction "1_1") (pintype "passive"))
    )
    (net (code "2") (name "+V") (class "Default")
      (node (ref "AMD") (pin "4") (pinfunction "VCC_4") (pintype "bidirectional"))
      (node (ref "BMD") (pin "4") (pinfunction "VCC_4") (pintype "bidirectional"))
      (node (ref "BOOST_IN") (pin "P") (pinfunction "P_P") (pintype "passive"))
      (node (ref "C201") (pin "2") (pinfunction "2_2") (pintype "passive"))
      (node (ref "C202") (pin "2") (pinfunction "2_2") (pintype "passive"))
      (node (ref "C203") (pin "2") (pinfunction "2_2") (pintype "passive"))
      (node (ref "C204") (pin "2") (pinfunction "2_2") (pintype "passive"))
      (node (ref "C205") (pin "2") (pinfunction "2_2") (pintype "passive"))
      (node (ref "C206") (pin "2") (pinfunction "2_2") (pintype "passive"))
      (node (ref "C207") (pin "2") (pinfunction "2_2") (pintype "passive"))
      (node (ref "C208") (pin "2") (pinfunction "2_2") (pintype "passive"))
      (node (ref "C209") (pin "2") (pinfunction "2_2") (pintype "passive"))
      (node (ref "C210") (pin "2") (pinfunction "2_2") (pintype "passive"))
      (node (ref "C211") (pin "2") (pinfunction "2_2") (pintype "passive"))
      (node (ref "C212") (pin "2") (pinfunction "2_2") (pintype "passive"))
      (node (ref "C215") (pin "2") (pinfunction "2_2") (pintype "passive"))
      (node (ref "C216") (pin "2") (pinfunction "2_2") (pintype "passive"))
      (node (ref "C217") (pin "2") (pinfunction "2_2") (pintype "passive"))
      (node (ref "C218") (pin "2") (pinfunction "2_2") (pintype "passive"))
      (node (ref "C219") (pin "2") (pinfunction "2_2") (pintype "passive"))
      (node (ref "CMD") (pin "4") (pinfunction "VCC_4") (pintype "bidirectional"))
      (node (ref "DMD") (pin "4") (pinfunction "VCC_4") (pintype "bidirectional"))
      (node (ref "MOSDRIVER") (pin "1") (pinfunction "ENABLE_1_1") (pintype "input"))
      (node (ref "MOSDRIVER") (pin "6") (pinfunction "VCC_6") (pintype "power_in"))
      (node (ref "MOSDRIVER") (pin "8") (pinfunction "ENABLE_2_8") (pintype "input"))
      (node (ref "POWER_CONN") (pin "P") (pinfunction "P_P") (pintype "passive"))
    )
    (net (code "3") (name "3V3") (class "Default")
      (node (ref "AMUX") (pin "24") (pinfunction "VCC_24") (pintype "power_in"))
      (node (ref "BMUX") (pin "24") (pinfunction "VCC_24") (pintype "power_in"))
      (node (ref "C213") (pin "2") (pinfunction "2_2") (pintype "passive"))
      (node (ref "C214") (pin "2") (pinfunction "2_2") (pintype "passive"))
      (node (ref "C220") (pin "2") (pinfunction "2_2") (pintype "passive"))
      (node (ref "MAIN_CONN_A") (pin "3") (pinfunction "3_3") (pintype "passive"))
      (node (ref "MAIN_CONN_B") (pin "3") (pinfunction "3_3") (pintype "passive"))
      (node (ref "MAIN_CONN_C") (pin "3") (pinfunction "3_3") (pintype "passive"))
      (node (ref "MAIN_CONN_D") (pin "3") (pinfunction "3_3") (pintype "passive"))
      (node (ref "R0") (pin "2") (pinfunction "2_2") (pintype "passive"))
      (node (ref "R1") (pin "2") (pinfunction "2_2") (pintype "passive"))
      (node (ref "R10") (pin "2") (pinfunction "2_2") (pintype "passive"))
      (node (ref "R11") (pin "2") (pinfunction "2_2") (pintype "passive"))
      (node (ref "R12") (pin "2") (pinfunction "2_2") (pintype "passive"))
      (node (ref "R13") (pin "2") (pinfunction "2_2") (pintype "passive"))
      (node (ref "R14") (pin "2") (pinfunction "2_2") (pintype "passive"))
      (node (ref "R15") (pin "2") (pinfunction "2_2") (pintype "passive"))
      (node (ref "R16") (pin "2") (pinfunction "2_2") (pintype "passive"))
      (node (ref "R17") (pin "2") (pinfunction "2_2") (pintype "passive"))
      (node (ref "R18") (pin "2") (pinfunction "2_2") (pintype "passive"))
      (node (ref "R19") (pin "2") (pinfunction "2_2") (pintype "passive"))
      (node (ref "R2") (pin "2") (pinfunction "2_2") (pintype "passive"))
      (node (ref "R20") (pin "2") (pinfunction "2_2") (pintype "passive"))
      (node (ref "R21") (pin "2") (pinfunction "2_2") (pintype "passive"))
      (node (ref "R22") (pin "2") (pinfunction "2_2") (pintype "passive"))
      (node (ref "R23") (pin "2") (pinfunction "2_2") (pintype "passive"))
      (node (ref "R24") (pin "2") (pinfunction "2_2") (pintype "passive"))
      (node (ref "R25") (pin "2") (pinfunction "2_2") (pintype "passive"))
      (node (ref "R26") (pin "2") (pinfunction "2_2") (pintype "passive"))
      (node (ref "R27") (pin "2") (pinfunction "2_2") (pintype "passive"))
      (node (ref "R28") (pin "2") (pinfunction "2_2") (pintype "passive"))
      (node (ref "R29") (pin "2") (pinfunction "2_2") (pintype "passive"))
      (node (ref "R3") (pin "2") (pinfunction "2_2") (pintype "passive"))
      (node (ref "R30") (pin "2") (pinfunction "2_2") (pintype "passive"))
      (node (ref "R31") (pin "2") (pinfunction "2_2") (pintype "passive"))
      (node (ref "R32") (pin "2") (pinfunction "2_2") (pintype "passive"))
      (node (ref "R33") (pin "2") (pinfunction "2_2") (pintype "passive"))
      (node (ref "R34") (pin "2") (pinfunction "2_2") (pintype "passive"))
      (node (ref "R35") (pin "2") (pinfunction "2_2") (pintype "passive"))
      (node (ref "R36") (pin "2") (pinfunction "2_2") (pintype "passive"))
      (node (ref "R37") (pin "2") (pinfunction "2_2") (pintype "passive"))
      (node (ref "R38") (pin "2") (pinfunction "2_2") (pintype "passive"))
      (node (ref "R39") (pin "2") (pinfunction "2_2") (pintype "passive"))
      (node (ref "R4") (pin "2") (pinfunction "2_2") (pintype "passive"))
      (node (ref "R40") (pin "2") (pinfunction "2_2") (pintype "passive"))
      (node (ref "R41") (pin "2") (pinfunction "2_2") (pintype "passive"))
      (node (ref "R42") (pin "2") (pinfunction "2_2") (pintype "passive"))
      (node (ref "R43") (pin "2") (pinfunction "2_2") (pintype "passive"))
      (node (ref "R44") (pin "2") (pinfunction "2_2") (pintype "passive"))
      (node (ref "R45") (pin "2") (pinfunction "2_2") (pintype "passive"))
      (node (ref "R46") (pin "2") (pinfunction "2_2") (pintype "passive"))
      (node (ref "R47") (pin "2") (pinfunction "2_2") (pintype "passive"))
      (node (ref "R5") (pin "2") (pinfunction "2_2") (pintype "passive"))
      (node (ref "R6") (pin "2") (pinfunction "2_2") (pintype "passive"))
      (node (ref "R7") (pin "2") (pinfunction "2_2") (pintype "passive"))
      (node (ref "R8") (pin "2") (pinfunction "2_2") (pintype "passive"))
      (node (ref "R9") (pin "2") (pinfunction "2_2") (pintype "passive"))
      (node (ref "XMUX") (pin "24") (pinfunction "VCC_24") (pintype "power_in"))
    )
    (net (code "4") (name "BOOST_V") (class "Default")
      (node (ref "BOOST_IN") (pin "N") (pinfunction "N_N") (pintype "passive"))
      (node (ref "BOOST_OUT") (pin "P") (pinfunction "P_P") (pintype "passive"))
      (node (ref "C221") (pin "2") (pinfunction "2_2") (pintype "passive"))
      (node (ref "C222") (pin "2") (pinfunction "2_2") (pintype "passive"))
      (node (ref "C223") (pin "2") (pinfunction "2_2") (pintype "passive"))
      (node (ref "C224") (pin "2") (pinfunction "2_2") (pintype "passive"))
      (node (ref "C225") (pin "2") (pinfunction "2_2") (pintype "passive"))
      (node (ref "C226") (pin "2") (pinfunction "2_2") (pintype "passive"))
      (node (ref "C227") (pin "2") (pinfunction "2_2") (pintype "passive"))
      (node (ref "C228") (pin "2") (pinfunction "2_2") (pintype "passive"))
      (node (ref "QF") (pin "D") (pinfunction "D_D") (pintype "passive"))
      (node (ref "QR") (pin "D") (pinfunction "D_D") (pintype "passive"))
    )
    (net (code "5") (name "GND") (class "Default")
      (node (ref "AENC") (pin "A3") (pinfunction "3_A3") (pintype "bidirectional"))
      (node (ref "AHAL") (pin "B4") (pinfunction "4_B4") (pintype "bidirectional"))
      (node (ref "AMD") (pin "18") (pinfunction "GND_18") (pintype "bidirectional"))
      (node (ref "AMD") (pin "5") (pinfunction "GND_5") (pintype "bidirectional"))
      (node (ref "AMUX") (pin "12") (pinfunction "GND_12") (pintype "power_in"))
      (node (ref "AMUX") (pin "15") (pinfunction "~{E}_15") (pintype "input"))
      (node (ref "BENC") (pin "A3") (pinfunction "3_A3") (pintype "bidirectional"))
      (node (ref "BHAL") (pin "B4") (pinfunction "4_B4") (pintype "bidirectional"))
      (node (ref "BMD") (pin "18") (pinfunction "GND_18") (pintype "bidirectional"))
      (node (ref "BMD") (pin "5") (pinfunction "GND_5") (pintype "bidirectional"))
      (node (ref "BMUX") (pin "12") (pinfunction "GND_12") (pintype "power_in"))
      (node (ref "BMUX") (pin "15") (pinfunction "~{E}_15") (pintype "input"))
      (node (ref "BOOST_OUT") (pin "N") (pinfunction "N_N") (pintype "passive"))
      (node (ref "C1") (pin "2") (pinfunction "2_2") (pintype "passive"))
      (node (ref "C101") (pin "2") (pinfunction "2_2") (pintype "passive"))
      (node (ref "C105") (pin "2") (pinfunction "2_2") (pintype "passive"))
      (node (ref "C109") (pin "2") (pinfunction "2_2") (pintype "passive"))
      (node (ref "C113") (pin "2") (pinfunction "2_2") (pintype "passive"))
      (node (ref "C17") (pin "2") (pinfunction "2_2") (pintype "passive"))
      (node (ref "C201") (pin "1") (pinfunction "1_1") (pintype "passive"))
      (node (ref "C202") (pin "1") (pinfunction "1_1") (pintype "passive"))
      (node (ref "C203") (pin "1") (pinfunction "1_1") (pintype "passive"))
      (node (ref "C204") (pin "1") (pinfunction "1_1") (pintype "passive"))
      (node (ref "C205") (pin "1") (pinfunction "1_1") (pintype "passive"))
      (node (ref "C206") (pin "1") (pinfunction "1_1") (pintype "passive"))
      (node (ref "C207") (pin "1") (pinfunction "1_1") (pintype "passive"))
      (node (ref "C208") (pin "1") (pinfunction "1_1") (pintype "passive"))
      (node (ref "C209") (pin "1") (pinfunction "1_1") (pintype "passive"))
      (node (ref "C210") (pin "1") (pinfunction "1_1") (pintype "passive"))
      (node (ref "C211") (pin "1") (pinfunction "1_1") (pintype "passive"))
      (node (ref "C212") (pin "1") (pinfunction "1_1") (pintype "passive"))
      (node (ref "C213") (pin "1") (pinfunction "1_1") (pintype "passive"))
      (node (ref "C214") (pin "1") (pinfunction "1_1") (pintype "passive"))
      (node (ref "C215") (pin "1") (pinfunction "1_1") (pintype "passive"))
      (node (ref "C216") (pin "1") (pinfunction "1_1") (pintype "passive"))
      (node (ref "C217") (pin "1") (pinfunction "1_1") (pintype "passive"))
      (node (ref "C218") (pin "1") (pinfunction "1_1") (pintype "passive"))
      (node (ref "C219") (pin "1") (pinfunction "1_1") (pintype "passive"))
      (node (ref "C220") (pin "1") (pinfunction "1_1") (pintype "passive"))
      (node (ref "C221") (pin "1") (pinfunction "1_1") (pintype "passive"))
      (node (ref "C222") (pin "1") (pinfunction "1_1") (pintype "passive"))
      (node (ref "C223") (pin "1") (pinfunction "1_1") (pintype "passive"))
      (node (ref "C224") (pin "1") (pinfunction "1_1") (pintype "passive"))
      (node (ref "C225") (pin "1") (pinfunction "1_1") (pintype "passive"))
      (node (ref "C226") (pin "1") (pinfunction "1_1") (pintype "passive"))
      (node (ref "C227") (pin "1") (pinfunction "1_1") (pintype "passive"))
      (node (ref "C228") (pin "1") (pinfunction "1_1") (pintype "passive"))
      (node (ref "C25") (pin "2") (pinfunction "2_2") (pintype "passive"))
      (node (ref "C9") (pin "2") (pinfunction "2_2") (pintype "passive"))
      (node (ref "CENC") (pin "A3") (pinfunction "3_A3") (pintype "bidirectional"))
      (node (ref "CHAL") (pin "B4") (pinfunction "4_B4") (pintype "bidirectional"))
      (node (ref "CMD") (pin "18") (pinfunction "GND_18") (pintype "bidirectional"))
      (node (ref "CMD") (pin "5") (pinfunction "GND_5") (pintype "bidirectional"))
      (node (ref "D1") (pin "A") (pinfunction "A_A") (pintype "passive"))
      (node (ref "D2") (pin "A") (pinfunction "A_A") (pintype "passive"))
      (node (ref "DENC") (pin "A3") (pinfunction "3_A3") (pintype "bidirectional"))
      (node (ref "DHAL") (pin "B4") (pinfunction "4_B4") (pintype "bidirectional"))
      (node (ref "DMD") (pin "18") (pinfunction "GND_18") (pintype "bidirectional"))
      (node (ref "DMD") (pin "5") (pinfunction "GND_5") (pintype "bidirectional"))
      (node (ref "KICKER_F_CONN") (pin "N") (pinfunction "N_N") (pintype "passive"))
      (node (ref "KICKER_R_CONN") (pin "N") (pinfunction "N_N") (pintype "passive"))
      (node (ref "LED0") (pin "1") (pinfunction "VSS_1") (pintype "passive"))
      (node (ref "LED1") (pin "1") (pinfunction "VSS_1") (pintype "passive"))
      (node (ref "LED10") (pin "1") (pinfunction "VSS_1") (pintype "passive"))
      (node (ref "LED11") (pin "1") (pinfunction "VSS_1") (pintype "passive"))
      (node (ref "LED12") (pin "1") (pinfunction "VSS_1") (pintype "passive"))
      (node (ref "LED13") (pin "1") (pinfunction "VSS_1") (pintype "passive"))
      (node (ref "LED14") (pin "1") (pinfunction "VSS_1") (pintype "passive"))
      (node (ref "LED15") (pin "1") (pinfunction "VSS_1") (pintype "passive"))
      (node (ref "LED16") (pin "1") (pinfunction "VSS_1") (pintype "passive"))
      (node (ref "LED17") (pin "1") (pinfunction "VSS_1") (pintype "passive"))
      (node (ref "LED18") (pin "1") (pinfunction "VSS_1") (pintype "passive"))
      (node (ref "LED19") (pin "1") (pinfunction "VSS_1") (pintype "passive"))
      (node (ref "LED2") (pin "1") (pinfunction "VSS_1") (pintype "passive"))
      (node (ref "LED20") (pin "1") (pinfunction "VSS_1") (pintype "passive"))
      (node (ref "LED21") (pin "1") (pinfunction "VSS_1") (pintype "passive"))
      (node (ref "LED22") (pin "1") (pinfunction "VSS_1") (pintype "passive"))
      (node (ref "LED23") (pin "1") (pinfunction "VSS_1") (pintype "passive"))
      (node (ref "LED24") (pin "1") (pinfunction "VSS_1") (pintype "passive"))
      (node (ref "LED25") (pin "1") (pinfunction "VSS_1") (pintype "passive"))
      (node (ref "LED26") (pin "1") (pinfunction "VSS_1") (pintype "passive"))
      (node (ref "LED27") (pin "1") (pinfunction "VSS_1") (pintype "passive"))
      (node (ref "LED28") (pin "1") (pinfunction "VSS_1") (pintype "passive"))
      (node (ref "LED29") (pin "1") (pinfunction "VSS_1") (pintype "passive"))
      (node (ref "LED3") (pin "1") (pinfunction "VSS_1") (pintype "passive"))
      (node (ref "LED30") (pin "1") (pinfunction "VSS_1") (pintype "passive"))
      (node (ref "LED31") (pin "1") (pinfunction "VSS_1") (pintype "passive"))
      (node (ref "LED32") (pin "1") (pinfunction "VSS_1") (pintype "passive"))
      (node (ref "LED33") (pin "1") (pinfunction "VSS_1") (pintype "passive"))
      (node (ref "LED34") (pin "1") (pinfunction "VSS_1") (pintype "passive"))
      (node (ref "LED35") (pin "1") (pinfunction "VSS_1") (pintype "passive"))
      (node (ref "LED36") (pin "1") (pinfunction "VSS_1") (pintype "passive"))
      (node (ref "LED37") (pin "1") (pinfunction "VSS_1") (pintype "passive"))
      (node (ref "LED38") (pin "1") (pinfunction "VSS_1") (pintype "passive"))
      (node (ref "LED39") (pin "1") (pinfunction "VSS_1") (pintype "passive"))
      (node (ref "LED4") (pin "1") (pinfunction "VSS_1") (pintype "passive"))
      (node (ref "LED40") (pin "1") (pinfunction "VSS_1") (pintype "passive"))
      (node (ref "LED41") (pin "1") (pinfunction "VSS_1") (pintype "passive"))
      (node (ref "LED42") (pin "1") (pinfunction "VSS_1") (pintype "passive"))
      (node (ref "LED43") (pin "1") (pinfunction "VSS_1") (pintype "passive"))
      (node (ref "LED44") (pin "1") (pinfunction "VSS_1") (pintype "passive"))
      (node (ref "LED45") (pin "1") (pinfunction "VSS_1") (pintype "passive"))
      (node (ref "LED46") (pin "1") (pinfunction "VSS_1") (pintype "passive"))
      (node (ref "LED47") (pin "1") (pinfunction "VSS_1") (pintype "passive"))
      (node (ref "LED5") (pin "1") (pinfunction "VSS_1") (pintype "passive"))
      (node (ref "LED6") (pin "1") (pinfunction "VSS_1") (pintype "passive"))
      (node (ref "LED7") (pin "1") (pinfunction "VSS_1") (pintype "passive"))
      (node (ref "LED8") (pin "1") (pinfunction "VSS_1") (pintype "passive"))
      (node (ref "LED9") (pin "1") (pinfunction "VSS_1") (pintype "passive"))
      (node (ref "MAIN_CONN_A") (pin "5") (pinfunction "5_5") (pintype "passive"))
      (node (ref "MAIN_CONN_B") (pin "5") (pinfunction "5_5") (pintype "passive"))
      (node (ref "MAIN_CONN_B") (pin "7") (pinfunction "7_7") (pintype "passive"))
      (node (ref "MAIN_CONN_C") (pin "5") (pinfunction "5_5") (pintype "passive"))
      (node (ref "MAIN_CONN_D") (pin "5") (pinfunction "5_5") (pintype "passive"))
      (node (ref "MOSDRIVER") (pin "3") (pinfunction "GND_3") (pintype "passive"))
      (node (ref "PHOTO0") (pin "1") (pinfunction "1_1") (pintype "passive"))
      (node (ref "PHOTO1") (pin "1") (pinfunction "1_1") (pintype "passive"))
      (node (ref "PHOTO10") (pin "1") (pinfunction "1_1") (pintype "passive"))
      (node (ref "PHOTO11") (pin "1") (pinfunction "1_1") (pintype "passive"))
      (node (ref "PHOTO12") (pin "1") (pinfunction "1_1") (pintype "passive"))
      (node (ref "PHOTO13") (pin "1") (pinfunction "1_1") (pintype "passive"))
      (node (ref "PHOTO14") (pin "1") (pinfunction "1_1") (pintype "passive"))
      (node (ref "PHOTO15") (pin "1") (pinfunction "1_1") (pintype "passive"))
      (node (ref "PHOTO16") (pin "1") (pinfunction "1_1") (pintype "passive"))
      (node (ref "PHOTO17") (pin "1") (pinfunction "1_1") (pintype "passive"))
      (node (ref "PHOTO18") (pin "1") (pinfunction "1_1") (pintype "passive"))
      (node (ref "PHOTO19") (pin "1") (pinfunction "1_1") (pintype "passive"))
      (node (ref "PHOTO2") (pin "1") (pinfunction "1_1") (pintype "passive"))
      (node (ref "PHOTO20") (pin "1") (pinfunction "1_1") (pintype "passive"))
      (node (ref "PHOTO21") (pin "1") (pinfunction "1_1") (pintype "passive"))
      (node (ref "PHOTO22") (pin "1") (pinfunction "1_1") (pintype "passive"))
      (node (ref "PHOTO23") (pin "1") (pinfunction "1_1") (pintype "passive"))
      (node (ref "PHOTO24") (pin "1") (pinfunction "1_1") (pintype "passive"))
      (node (ref "PHOTO25") (pin "1") (pinfunction "1_1") (pintype "passive"))
      (node (ref "PHOTO26") (pin "1") (pinfunction "1_1") (pintype "passive"))
      (node (ref "PHOTO27") (pin "1") (pinfunction "1_1") (pintype "passive"))
      (node (ref "PHOTO28") (pin "1") (pinfunction "1_1") (pintype "passive"))
      (node (ref "PHOTO29") (pin "1") (pinfunction "1_1") (pintype "passive"))
      (node (ref "PHOTO3") (pin "1") (pinfunction "1_1") (pintype "passive"))
      (node (ref "PHOTO30") (pin "1") (pinfunction "1_1") (pintype "passive"))
      (node (ref "PHOTO31") (pin "1") (pinfunction "1_1") (pintype "passive"))
      (node (ref "PHOTO32") (pin "1") (pinfunction "1_1") (pintype "passive"))
      (node (ref "PHOTO33") (pin "1") (pinfunction "1_1") (pintype "passive"))
      (node (ref "PHOTO34") (pin "1") (pinfunction "1_1") (pintype "passive"))
      (node (ref "PHOTO35") (pin "1") (pinfunction "1_1") (pintype "passive"))
      (node (ref "PHOTO36") (pin "1") (pinfunction "1_1") (pintype "passive"))
      (node (ref "PHOTO37") (pin "1") (pinfunction "1_1") (pintype "passive"))
      (node (ref "PHOTO38") (pin "1") (pinfunction "1_1") (pintype "passive"))
      (node (ref "PHOTO39") (pin "1") (pinfunction "1_1") (pintype "passive"))
      (node (ref "PHOTO4") (pin "1") (pinfunction "1_1") (pintype "passive"))
      (node (ref "PHOTO40") (pin "1") (pinfunction "1_1") (pintype "passive"))
      (node (ref "PHOTO41") (pin "1") (pinfunction "1_1") (pintype "passive"))
      (node (ref "PHOTO42") (pin "1") (pinfunction "1_1") (pintype "passive"))
      (node (ref "PHOTO43") (pin "1") (pinfunction "1_1") (pintype "passive"))
      (node (ref "PHOTO44") (pin "1") (pinfunction "1_1") (pintype "passive"))
      (node (ref "PHOTO45") (pin "1") (pinfunction "1_1") (pintype "passive"))
      (node (ref "PHOTO46") (pin "1") (pinfunction "1_1") (pintype "passive"))
      (node (ref "PHOTO47") (pin "1") (pinfunction "1_1") (pintype "passive"))
      (node (ref "PHOTO5") (pin "1") (pinfunction "1_1") (pintype "passive"))
      (node (ref "PHOTO6") (pin "1") (pinfunction "1_1") (pintype "passive"))
      (node (ref "PHOTO7") (pin "1") (pinfunction "1_1") (pintype "passive"))
      (node (ref "PHOTO8") (pin "1") (pinfunction "1_1") (pintype "passive"))
      (node (ref "PHOTO9") (pin "1") (pinfunction "1_1") (pintype "passive"))
      (node (ref "POWER_CONN") (pin "N") (pinfunction "N_N") (pintype "passive"))
      (node (ref "R97") (pin "1") (pinfunction "1_1") (pintype "passive"))
      (node (ref "R98") (pin "1") (pinfunction "1_1") (pintype "passive"))
      (node (ref "XMUX") (pin "12") (pinfunction "GND_12") (pintype "power_in"))
      (node (ref "XMUX") (pin "15") (pinfunction "~{E}_15") (pintype "input"))
    )
    (net (code "6") (name "KICKER_F") (class "Default")
      (node (ref "MAIN_CONN_A") (pin "7") (pinfunction "7_7") (pintype "passive"))
      (node (ref "MOSDRIVER") (pin "4") (pinfunction "PWM_2_4") (pintype "input"))
      (node (ref "R97") (pin "2") (pinfunction "2_2") (pintype "passive"))
    )
    (net (code "7") (name "KICKER_R") (class "Default")
      (node (ref "MAIN_CONN_C") (pin "8") (pinfunction "8_8") (pintype "passive"))
      (node (ref "MOSDRIVER") (pin "2") (pinfunction "PWM_1_2") (pintype "input"))
      (node (ref "R98") (pin "2") (pinfunction "2_2") (pintype "passive"))
    )
    (net (code "8") (name "LED_SET_O") (class "Default")
      (node (ref "LED0") (pin "2") (pinfunction "DIN_2") (pintype "input"))
      (node (ref "MAIN_CONN_A") (pin "8") (pinfunction "8_8") (pintype "passive"))
    )
    (net (code "9") (name "LED_SET_X") (class "Default")
      (node (ref "LED32") (pin "2") (pinfunction "DIN_2") (pintype "input"))
      (node (ref "MAIN_CONN_B") (pin "8") (pinfunction "8_8") (pintype "passive"))
    )
    (net (code "10") (name "LINE0") (class "Default")
      (node (ref "AMUX") (pin "9") (pinfunction "I0_9") (pintype "input"))
      (node (ref "PHOTO0") (pin "2") (pinfunction "2_2") (pintype "passive"))
      (node (ref "R0") (pin "1") (pinfunction "1_1") (pintype "passive"))
    )
    (net (code "11") (name "LINE1") (class "Default")
      (node (ref "AMUX") (pin "8") (pinfunction "I1_8") (pintype "input"))
      (node (ref "PHOTO1") (pin "2") (pinfunction "2_2") (pintype "passive"))
      (node (ref "R1") (pin "1") (pinfunction "1_1") (pintype "passive"))
    )
    (net (code "12") (name "LINE2") (class "Default")
      (node (ref "AMUX") (pin "7") (pinfunction "I2_7") (pintype "input"))
      (node (ref "PHOTO2") (pin "2") (pinfunction "2_2") (pintype "passive"))
      (node (ref "R2") (pin "1") (pinfunction "1_1") (pintype "passive"))
    )
    (net (code "13") (name "LINE3") (class "Default")
      (node (ref "AMUX") (pin "6") (pinfunction "I3_6") (pintype "input"))
      (node (ref "PHOTO3") (pin "2") (pinfunction "2_2") (pintype "passive"))
      (node (ref "R3") (pin "1") (pinfunction "1_1") (pintype "passive"))
    )
    (net (code "14") (name "LINE4") (class "Default")
      (node (ref "AMUX") (pin "5") (pinfunction "I4_5") (pintype "input"))
      (node (ref "PHOTO4") (pin "2") (pinfunction "2_2") (pintype "passive"))
      (node (ref "R4") (pin "1") (pinfunction "1_1") (pintype "passive"))
    )
    (net (code "15") (name "LINE5") (class "Default")
      (node (ref "AMUX") (pin "4") (pinfunction "I5_4") (pintype "input"))
      (node (ref "PHOTO5") (pin "2") (pinfunction "2_2") (pintype "passive"))
      (node (ref "R5") (pin "1") (pinfunction "1_1") (pintype "passive"))
    )
    (net (code "16") (name "LINE6") (class "Default")
      (node (ref "AMUX") (pin "3") (pinfunction "I6_3") (pintype "input"))
      (node (ref "PHOTO6") (pin "2") (pinfunction "2_2") (pintype "passive"))
      (node (ref "R6") (pin "1") (pinfunction "1_1") (pintype "passive"))
    )
    (net (code "17") (name "LINE7") (class "Default")
      (node (ref "AMUX") (pin "2") (pinfunction "I7_2") (pintype "input"))
      (node (ref "PHOTO7") (pin "2") (pinfunction "2_2") (pintype "passive"))
      (node (ref "R7") (pin "1") (pinfunction "1_1") (pintype "passive"))
    )
    (net (code "18") (name "LINE8") (class "Default")
      (node (ref "AMUX") (pin "23") (pinfunction "I8_23") (pintype "input"))
      (node (ref "PHOTO8") (pin "2") (pinfunction "2_2") (pintype "passive"))
      (node (ref "R8") (pin "1") (pinfunction "1_1") (pintype "passive"))
    )
    (net (code "19") (name "LINE9") (class "Default")
      (node (ref "AMUX") (pin "22") (pinfunction "I9_22") (pintype "input"))
      (node (ref "PHOTO9") (pin "2") (pinfunction "2_2") (pintype "passive"))
      (node (ref "R9") (pin "1") (pinfunction "1_1") (pintype "passive"))
    )
    (net (code "20") (name "LINE10") (class "Default")
      (node (ref "AMUX") (pin "21") (pinfunction "I10_21") (pintype "input"))
      (node (ref "PHOTO10") (pin "2") (pinfunction "2_2") (pintype "passive"))
      (node (ref "R10") (pin "1") (pinfunction "1_1") (pintype "passive"))
    )
    (net (code "21") (name "LINE11") (class "Default")
      (node (ref "AMUX") (pin "20") (pinfunction "I11_20") (pintype "input"))
      (node (ref "PHOTO11") (pin "2") (pinfunction "2_2") (pintype "passive"))
      (node (ref "R11") (pin "1") (pinfunction "1_1") (pintype "passive"))
    )
    (net (code "22") (name "LINE12") (class "Default")
      (node (ref "AMUX") (pin "19") (pinfunction "I12_19") (pintype "input"))
      (node (ref "PHOTO12") (pin "2") (pinfunction "2_2") (pintype "passive"))
      (node (ref "R12") (pin "1") (pinfunction "1_1") (pintype "passive"))
    )
    (net (code "23") (name "LINE13") (class "Default")
      (node (ref "AMUX") (pin "18") (pinfunction "I13_18") (pintype "input"))
      (node (ref "PHOTO13") (pin "2") (pinfunction "2_2") (pintype "passive"))
      (node (ref "R13") (pin "1") (pinfunction "1_1") (pintype "passive"))
    )
    (net (code "24") (name "LINE14") (class "Default")
      (node (ref "AMUX") (pin "17") (pinfunction "I14_17") (pintype "input"))
      (node (ref "PHOTO14") (pin "2") (pinfunction "2_2") (pintype "passive"))
      (node (ref "R14") (pin "1") (pinfunction "1_1") (pintype "passive"))
    )
    (net (code "25") (name "LINE15") (class "Default")
      (node (ref "AMUX") (pin "16") (pinfunction "I15_16") (pintype "input"))
      (node (ref "PHOTO15") (pin "2") (pinfunction "2_2") (pintype "passive"))
      (node (ref "R15") (pin "1") (pinfunction "1_1") (pintype "passive"))
    )
    (net (code "26") (name "LINE16") (class "Default")
      (node (ref "BMUX") (pin "9") (pinfunction "I0_9") (pintype "input"))
      (node (ref "PHOTO16") (pin "2") (pinfunction "2_2") (pintype "passive"))
      (node (ref "R16") (pin "1") (pinfunction "1_1") (pintype "passive"))
    )
    (net (code "27") (name "LINE17") (class "Default")
      (node (ref "BMUX") (pin "8") (pinfunction "I1_8") (pintype "input"))
      (node (ref "PHOTO17") (pin "2") (pinfunction "2_2") (pintype "passive"))
      (node (ref "R17") (pin "1") (pinfunction "1_1") (pintype "passive"))
    )
    (net (code "28") (name "LINE18") (class "Default")
      (node (ref "BMUX") (pin "7") (pinfunction "I2_7") (pintype "input"))
      (node (ref "PHOTO18") (pin "2") (pinfunction "2_2") (pintype "passive"))
      (node (ref "R18") (pin "1") (pinfunction "1_1") (pintype "passive"))
    )
    (net (code "29") (name "LINE19") (class "Default")
      (node (ref "BMUX") (pin "6") (pinfunction "I3_6") (pintype "input"))
      (node (ref "PHOTO19") (pin "2") (pinfunction "2_2") (pintype "passive"))
      (node (ref "R19") (pin "1") (pinfunction "1_1") (pintype "passive"))
    )
    (net (code "30") (name "LINE20") (class "Default")
      (node (ref "BMUX") (pin "5") (pinfunction "I4_5") (pintype "input"))
      (node (ref "PHOTO20") (pin "2") (pinfunction "2_2") (pintype "passive"))
      (node (ref "R20") (pin "1") (pinfunction "1_1") (pintype "passive"))
    )
    (net (code "31") (name "LINE21") (class "Default")
      (node (ref "BMUX") (pin "4") (pinfunction "I5_4") (pintype "input"))
      (node (ref "PHOTO21") (pin "2") (pinfunction "2_2") (pintype "passive"))
      (node (ref "R21") (pin "1") (pinfunction "1_1") (pintype "passive"))
    )
    (net (code "32") (name "LINE22") (class "Default")
      (node (ref "BMUX") (pin "3") (pinfunction "I6_3") (pintype "input"))
      (node (ref "PHOTO22") (pin "2") (pinfunction "2_2") (pintype "passive"))
      (node (ref "R22") (pin "1") (pinfunction "1_1") (pintype "passive"))
    )
    (net (code "33") (name "LINE23") (class "Default")
      (node (ref "BMUX") (pin "2") (pinfunction "I7_2") (pintype "input"))
      (node (ref "PHOTO23") (pin "2") (pinfunction "2_2") (pintype "passive"))
      (node (ref "R23") (pin "1") (pinfunction "1_1") (pintype "passive"))
    )
    (net (code "34") (name "LINE24") (class "Default")
      (node (ref "BMUX") (pin "23") (pinfunction "I8_23") (pintype "input"))
      (node (ref "PHOTO24") (pin "2") (pinfunction "2_2") (pintype "passive"))
      (node (ref "R24") (pin "1") (pinfunction "1_1") (pintype "passive"))
    )
    (net (code "35") (name "LINE25") (class "Default")
      (node (ref "BMUX") (pin "22") (pinfunction "I9_22") (pintype "input"))
      (node (ref "PHOTO25") (pin "2") (pinfunction "2_2") (pintype "passive"))
      (node (ref "R25") (pin "1") (pinfunction "1_1") (pintype "passive"))
    )
    (net (code "36") (name "LINE26") (class "Default")
      (node (ref "BMUX") (pin "21") (pinfunction "I10_21") (pintype "input"))
      (node (ref "PHOTO26") (pin "2") (pinfunction "2_2") (pintype "passive"))
      (node (ref "R26") (pin "1") (pinfunction "1_1") (pintype "passive"))
    )
    (net (code "37") (name "LINE27") (class "Default")
      (node (ref "BMUX") (pin "20") (pinfunction "I11_20") (pintype "input"))
      (node (ref "PHOTO27") (pin "2") (pinfunction "2_2") (pintype "passive"))
      (node (ref "R27") (pin "1") (pinfunction "1_1") (pintype "passive"))
    )
    (net (code "38") (name "LINE28") (class "Default")
      (node (ref "BMUX") (pin "19") (pinfunction "I12_19") (pintype "input"))
      (node (ref "PHOTO28") (pin "2") (pinfunction "2_2") (pintype "passive"))
      (node (ref "R28") (pin "1") (pinfunction "1_1") (pintype "passive"))
    )
    (net (code "39") (name "LINE29") (class "Default")
      (node (ref "BMUX") (pin "18") (pinfunction "I13_18") (pintype "input"))
      (node (ref "PHOTO29") (pin "2") (pinfunction "2_2") (pintype "passive"))
      (node (ref "R29") (pin "1") (pinfunction "1_1") (pintype "passive"))
    )
    (net (code "40") (name "LINE30") (class "Default")
      (node (ref "BMUX") (pin "17") (pinfunction "I14_17") (pintype "input"))
      (node (ref "PHOTO30") (pin "2") (pinfunction "2_2") (pintype "passive"))
      (node (ref "R30") (pin "1") (pinfunction "1_1") (pintype "passive"))
    )
    (net (code "41") (name "LINE31") (class "Default")
      (node (ref "BMUX") (pin "16") (pinfunction "I15_16") (pintype "input"))
      (node (ref "PHOTO31") (pin "2") (pinfunction "2_2") (pintype "passive"))
      (node (ref "R31") (pin "1") (pinfunction "1_1") (pintype "passive"))
    )
    (net (code "42") (name "LINE_AREAD") (class "Default")
      (node (ref "AMUX") (pin "1") (pinfunction "COMMON_I/O_1") (pintype "bidirectional"))
      (node (ref "MAIN_CONN_C") (pin "10") (pinfunction "10_10") (pintype "passive"))
    )
    (net (code "43") (name "LINE_BREAD") (class "Default")
      (node (ref "BMUX") (pin "1") (pinfunction "COMMON_I/O_1") (pintype "bidirectional"))
      (node (ref "MAIN_CONN_A") (pin "10") (pinfunction "10_10") (pintype "passive"))
    )
    (net (code "44") (name "LINE_SET0") (class "Default")
      (node (ref "AMUX") (pin "10") (pinfunction "S0_10") (pintype "bidirectional"))
      (node (ref "BMUX") (pin "10") (pinfunction "S0_10") (pintype "bidirectional"))
      (node (ref "MAIN_CONN_D") (pin "8") (pinfunction "8_8") (pintype "passive"))
      (node (ref "XMUX") (pin "10") (pinfunction "S0_10") (pintype "bidirectional"))
    )
    (net (code "45") (name "LINE_SET1") (class "Default")
      (node (ref "AMUX") (pin "11") (pinfunction "S1_11") (pintype "bidirectional"))
      (node (ref "BMUX") (pin "11") (pinfunction "S1_11") (pintype "bidirectional"))
      (node (ref "MAIN_CONN_D") (pin "10") (pinfunction "10_10") (pintype "passive"))
      (node (ref "XMUX") (pin "11") (pinfunction "S1_11") (pintype "bidirectional"))
    )
    (net (code "46") (name "LINE_SET2") (class "Default")
      (node (ref "AMUX") (pin "14") (pinfunction "S2_14") (pintype "bidirectional"))
      (node (ref "BMUX") (pin "14") (pinfunction "S2_14") (pintype "bidirectional"))
      (node (ref "MAIN_CONN_C") (pin "7") (pinfunction "7_7") (pintype "passive"))
      (node (ref "XMUX") (pin "14") (pinfunction "S2_14") (pintype "bidirectional"))
    )
    (net (code "47") (name "LINE_SET3") (class "Default")
      (node (ref "AMUX") (pin "13") (pinfunction "S3_13") (pintype "bidirectional"))
      (node (ref "BMUX") (pin "13") (pinfunction "S3_13") (pintype "bidirectional"))
      (node (ref "MAIN_CONN_D") (pin "7") (pinfunction "7_7") (pintype "passive"))
      (node (ref "XMUX") (pin "13") (pinfunction "S3_13") (pintype "bidirectional"))
    )
    (net (code "48") (name "LINE_XREAD") (class "Default")
      (node (ref "MAIN_CONN_B") (pin "10") (pinfunction "10_10") (pintype "passive"))
      (node (ref "XMUX") (pin "1") (pinfunction "COMMON_I/O_1") (pintype "bidirectional"))
    )
    (net (code "49") (name "MA_CHA") (class "Default")
      (node (ref "AENC") (pin "A6") (pinfunction "6_A6") (pintype "bidirectional"))
      (node (ref "AMD") (pin "10") (pinfunction "ENCODER_CHA_10") (pintype "bidirectional"))
    )
    (net (code "50") (name "MA_CHA\\\\") (class "Default")
      (node (ref "AENC") (pin "A5") (pinfunction "5_A5") (pintype "bidirectional"))
      (node (ref "AMD") (pin "11") (pinfunction "ENCODER_CHA\\\\_11") (pintype "bidirectional"))
    )
    (net (code "51") (name "MA_CHB") (class "Default")
      (node (ref "AENC") (pin "A8") (pinfunction "8_A8") (pintype "bidirectional"))
      (node (ref "AMD") (pin "12") (pinfunction "ENCODER_CHB_12") (pintype "bidirectional"))
    )
    (net (code "52") (name "MA_CHB\\\\") (class "Default")
      (node (ref "AENC") (pin "A7") (pinfunction "7_A7") (pintype "bidirectional"))
      (node (ref "AMD") (pin "13") (pinfunction "ENCODER_CHB\\\\_13") (pintype "bidirectional"))
    )
    (net (code "53") (name "MA_DIR") (class "Default")
      (node (ref "AMD") (pin "14") (pinfunction "DIG_IN/OUT4_14") (pintype "bidirectional"))
      (node (ref "MAIN_CONN_A") (pin "4") (pinfunction "4_4") (pintype "passive"))
    )
    (net (code "54") (name "MA_HS1") (class "Default")
      (node (ref "AHAL") (pin "B1") (pinfunction "1_B1") (pintype "bidirectional"))
      (node (ref "AMD") (pin "7") (pinfunction "HALL_SENSOR1_7") (pintype "bidirectional"))
    )
    (net (code "55") (name "MA_HS2") (class "Default")
      (node (ref "AHAL") (pin "B2") (pinfunction "2_B2") (pintype "bidirectional"))
      (node (ref "AMD") (pin "8") (pinfunction "HALL_SENSOR2_8") (pintype "bidirectional"))
    )
    (net (code "56") (name "MA_HS3") (class "Default")
      (node (ref "AHAL") (pin "B3") (pinfunction "3_B3") (pintype "bidirectional"))
      (node (ref "AMD") (pin "9") (pinfunction "HALL_SENSOR3_9") (pintype "bidirectional"))
    )
    (net (code "57") (name "MA_MW1") (class "Default")
      (node (ref "AMD") (pin "1") (pinfunction "MOTOR_WINDING1_1") (pintype "bidirectional"))
      (node (ref "AMW") (pin "C1") (pinfunction "1_C1") (pintype "bidirectional"))
    )
    (net (code "58") (name "MA_MW2") (class "Default")
      (node (ref "AMD") (pin "2") (pinfunction "MOTOR_WINDING2_2") (pintype "bidirectional"))
      (node (ref "AMW") (pin "C2") (pinfunction "2_C2") (pintype "bidirectional"))
    )
    (net (code "59") (name "MA_MW3") (class "Default")
      (node (ref "AMD") (pin "3") (pinfunction "MOTOR_WINDING3_3") (pintype "bidirectional"))
      (node (ref "AMW") (pin "C3") (pinfunction "3_C3") (pintype "bidirectional"))
    )
    (net (code "60") (name "MA_OSPD") (class "Default")
      (node (ref "AMD") (pin "20") (pinfunction "AN_OUT1_20") (pintype "bidirectional"))
      (node (ref "AOUT1") (pin "1") (pinfunction "TP_1") (pintype "passive"))
      (node (ref "MAIN_CONN_A") (pin "9") (pinfunction "9_9") (pintype "passive"))
    )
    (net (code "61") (name "MA_PWM") (class "Default")
      (node (ref "AMD") (pin "17") (pinfunction "DIG_IN1_17") (pintype "bidirectional"))
      (node (ref "MAIN_CONN_A") (pin "6") (pinfunction "6_6") (pintype "passive"))
    )
    (net (code "62") (name "MB_CHA") (class "Default")
      (node (ref "BENC") (pin "A6") (pinfunction "6_A6") (pintype "bidirectional"))
      (node (ref "BMD") (pin "10") (pinfunction "ENCODER_CHA_10") (pintype "bidirectional"))
    )
    (net (code "63") (name "MB_CHA\\\\") (class "Default")
      (node (ref "BENC") (pin "A5") (pinfunction "5_A5") (pintype "bidirectional"))
      (node (ref "BMD") (pin "11") (pinfunction "ENCODER_CHA\\\\_11") (pintype "bidirectional"))
    )
    (net (code "64") (name "MB_CHB") (class "Default")
      (node (ref "BENC") (pin "A8") (pinfunction "8_A8") (pintype "bidirectional"))
      (node (ref "BMD") (pin "12") (pinfunction "ENCODER_CHB_12") (pintype "bidirectional"))
    )
    (net (code "65") (name "MB_CHB\\\\") (class "Default")
      (node (ref "BENC") (pin "A7") (pinfunction "7_A7") (pintype "bidirectional"))
      (node (ref "BMD") (pin "13") (pinfunction "ENCODER_CHB\\\\_13") (pintype "bidirectional"))
    )
    (net (code "66") (name "MB_DIR") (class "Default")
      (node (ref "BMD") (pin "14") (pinfunction "DIG_IN/OUT4_14") (pintype "bidirectional"))
      (node (ref "MAIN_CONN_B") (pin "4") (pinfunction "4_4") (pintype "passive"))
    )
    (net (code "67") (name "MB_HS1") (class "Default")
      (node (ref "BHAL") (pin "B1") (pinfunction "1_B1") (pintype "bidirectional"))
      (node (ref "BMD") (pin "7") (pinfunction "HALL_SENSOR1_7") (pintype "bidirectional"))
    )
    (net (code "68") (name "MB_HS2") (class "Default")
      (node (ref "BHAL") (pin "B2") (pinfunction "2_B2") (pintype "bidirectional"))
      (node (ref "BMD") (pin "8") (pinfunction "HALL_SENSOR2_8") (pintype "bidirectional"))
    )
    (net (code "69") (name "MB_HS3") (class "Default")
      (node (ref "BHAL") (pin "B3") (pinfunction "3_B3") (pintype "bidirectional"))
      (node (ref "BMD") (pin "9") (pinfunction "HALL_SENSOR3_9") (pintype "bidirectional"))
    )
    (net (code "70") (name "MB_MW1") (class "Default")
      (node (ref "BMD") (pin "1") (pinfunction "MOTOR_WINDING1_1") (pintype "bidirectional"))
      (node (ref "BMW") (pin "C1") (pinfunction "1_C1") (pintype "bidirectional"))
    )
    (net (code "71") (name "MB_MW2") (class "Default")
      (node (ref "BMD") (pin "2") (pinfunction "MOTOR_WINDING2_2") (pintype "bidirectional"))
      (node (ref "BMW") (pin "C2") (pinfunction "2_C2") (pintype "bidirectional"))
    )
    (net (code "72") (name "MB_MW3") (class "Default")
      (node (ref "BMD") (pin "3") (pinfunction "MOTOR_WINDING3_3") (pintype "bidirectional"))
      (node (ref "BMW") (pin "C3") (pinfunction "3_C3") (pintype "bidirectional"))
    )
    (net (code "73") (name "MB_OSPD") (class "Default")
      (node (ref "BMD") (pin "20") (pinfunction "AN_OUT1_20") (pintype "bidirectional"))
      (node (ref "BOUT1") (pin "1") (pinfunction "TP_1") (pintype "passive"))
      (node (ref "MAIN_CONN_B") (pin "9") (pinfunction "9_9") (pintype "passive"))
    )
    (net (code "74") (name "MB_PWM") (class "Default")
      (node (ref "BMD") (pin "17") (pinfunction "DIG_IN1_17") (pintype "bidirectional"))
      (node (ref "MAIN_CONN_B") (pin "6") (pinfunction "6_6") (pintype "passive"))
    )
    (net (code "75") (name "MC_CHA") (class "Default")
      (node (ref "CENC") (pin "A6") (pinfunction "6_A6") (pintype "bidirectional"))
      (node (ref "CMD") (pin "10") (pinfunction "ENCODER_CHA_10") (pintype "bidirectional"))
    )
    (net (code "76") (name "MC_CHA\\\\") (class "Default")
      (node (ref "CENC") (pin "A5") (pinfunction "5_A5") (pintype "bidirectional"))
      (node (ref "CMD") (pin "11") (pinfunction "ENCODER_CHA\\\\_11") (pintype "bidirectional"))
    )
    (net (code "77") (name "MC_CHB") (class "Default")
      (node (ref "CENC") (pin "A8") (pinfunction "8_A8") (pintype "bidirectional"))
      (node (ref "CMD") (pin "12") (pinfunction "ENCODER_CHB_12") (pintype "bidirectional"))
    )
    (net (code "78") (name "MC_CHB\\\\") (class "Default")
      (node (ref "CENC") (pin "A7") (pinfunction "7_A7") (pintype "bidirectional"))
      (node (ref "CMD") (pin "13") (pinfunction "ENCODER_CHB\\\\_13") (pintype "bidirectional"))
    )
    (net (code "79") (name "MC_DIR") (class "Default")
      (node (ref "CMD") (pin "14") (pinfunction "DIG_IN/OUT4_14") (pintype "bidirectional"))
      (node (ref "MAIN_CONN_C") (pin "4") (pinfunction "4_4") (pintype "passive"))
    )
    (net (code "80") (name "MC_HS1") (class "Default")
      (node (ref "CHAL") (pin "B1") (pinfunction "1_B1") (pintype "bidirectional"))
      (node (ref "CMD") (pin "7") (pinfunction "HALL_SENSOR1_7") (pintype "bidirectional"))
    )
    (net (code "81") (name "MC_HS2") (class "Default")
      (node (ref "CHAL") (pin "B2") (pinfunction "2_B2") (pintype "bidirectional"))
      (node (ref "CMD") (pin "8") (pinfunction "HALL_SENSOR2_8") (pintype "bidirectional"))
    )
    (net (code "82") (name "MC_HS3") (class "Default")
      (node (ref "CHAL") (pin "B3") (pinfunction "3_B3") (pintype "bidirectional"))
      (node (ref "CMD") (pin "9") (pinfunction "HALL_SENSOR3_9") (pintype "bidirectional"))
    )
    (net (code "83") (name "MC_MW1") (class "Default")
      (node (ref "CMD") (pin "1") (pinfunction "MOTOR_WINDING1_1") (pintype "bidirectional"))
      (node (ref "CMW") (pin "C1") (pinfunction "1_C1") (pintype "bidirectional"))
    )
    (net (code "84") (name "MC_MW2") (class "Default")
      (node (ref "CMD") (pin "2") (pinfunction "MOTOR_WINDING2_2") (pintype "bidirectional"))
      (node (ref "CMW") (pin "C2") (pinfunction "2_C2") (pintype "bidirectional"))
    )
    (net (code "85") (name "MC_MW3") (class "Default")
      (node (ref "CMD") (pin "3") (pinfunction "MOTOR_WINDING3_3") (pintype "bidirectional"))
      (node (ref "CMW") (pin "C3") (pinfunction "3_C3") (pintype "bidirectional"))
    )
    (net (code "86") (name "MC_OSPD") (class "Default")
      (node (ref "CMD") (pin "20") (pinfunction "AN_OUT1_20") (pintype "bidirectional"))
      (node (ref "COUT1") (pin "1") (pinfunction "TP_1") (pintype "passive"))
      (node (ref "MAIN_CONN_C") (pin "9") (pinfunction "9_9") (pintype "passive"))
    )
    (net (code "87") (name "MC_PWM") (class "Default")
      (node (ref "CMD") (pin "17") (pinfunction "DIG_IN1_17") (pintype "bidirectional"))
      (node (ref "MAIN_CONN_C") (pin "6") (pinfunction "6_6") (pintype "passive"))
    )
    (net (code "88") (name "MD_CHA") (class "Default")
      (node (ref "DENC") (pin "A6") (pinfunction "6_A6") (pintype "bidirectional"))
      (node (ref "DMD") (pin "10") (pinfunction "ENCODER_CHA_10") (pintype "bidirectional"))
    )
    (net (code "89") (name "MD_CHA\\\\") (class "Default")
      (node (ref "DENC") (pin "A5") (pinfunction "5_A5") (pintype "bidirectional"))
      (node (ref "DMD") (pin "11") (pinfunction "ENCODER_CHA\\\\_11") (pintype "bidirectional"))
    )
    (net (code "90") (name "MD_CHB") (class "Default")
      (node (ref "DENC") (pin "A8") (pinfunction "8_A8") (pintype "bidirectional"))
      (node (ref "DMD") (pin "12") (pinfunction "ENCODER_CHB_12") (pintype "bidirectional"))
    )
    (net (code "91") (name "MD_CHB\\\\") (class "Default")
      (node (ref "DENC") (pin "A7") (pinfunction "7_A7") (pintype "bidirectional"))
      (node (ref "DMD") (pin "13") (pinfunction "ENCODER_CHB\\\\_13") (pintype "bidirectional"))
    )
    (net (code "92") (name "MD_DIR") (class "Default")
      (node (ref "DMD") (pin "14") (pinfunction "DIG_IN/OUT4_14") (pintype "bidirectional"))
      (node (ref "MAIN_CONN_D") (pin "4") (pinfunction "4_4") (pintype "passive"))
    )
    (net (code "93") (name "MD_HS1") (class "Default")
      (node (ref "DHAL") (pin "B1") (pinfunction "1_B1") (pintype "bidirectional"))
      (node (ref "DMD") (pin "7") (pinfunction "HALL_SENSOR1_7") (pintype "bidirectional"))
    )
    (net (code "94") (name "MD_HS2") (class "Default")
      (node (ref "DHAL") (pin "B2") (pinfunction "2_B2") (pintype "bidirectional"))
      (node (ref "DMD") (pin "8") (pinfunction "HALL_SENSOR2_8") (pintype "bidirectional"))
    )
    (net (code "95") (name "MD_HS3") (class "Default")
      (node (ref "DHAL") (pin "B3") (pinfunction "3_B3") (pintype "bidirectional"))
      (node (ref "DMD") (pin "9") (pinfunction "HALL_SENSOR3_9") (pintype "bidirectional"))
    )
    (net (code "96") (name "MD_MW1") (class "Default")
      (node (ref "DMD") (pin "1") (pinfunction "MOTOR_WINDING1_1") (pintype "bidirectional"))
      (node (ref "DMW") (pin "C1") (pinfunction "1_C1") (pintype "bidirectional"))
    )
    (net (code "97") (name "MD_MW2") (class "Default")
      (node (ref "DMD") (pin "2") (pinfunction "MOTOR_WINDING2_2") (pintype "bidirectional"))
      (node (ref "DMW") (pin "C2") (pinfunction "2_C2") (pintype "bidirectional"))
    )
    (net (code "98") (name "MD_MW3") (class "Default")
      (node (ref "DMD") (pin "3") (pinfunction "MOTOR_WINDING3_3") (pintype "bidirectional"))
      (node (ref "DMW") (pin "C3") (pinfunction "3_C3") (pintype "bidirectional"))
    )
    (net (code "99") (name "MD_OSPD") (class "Default")
      (node (ref "DMD") (pin "20") (pinfunction "AN_OUT1_20") (pintype "bidirectional"))
      (node (ref "DOUT1") (pin "1") (pinfunction "TP_1") (pintype "passive"))
      (node (ref "MAIN_CONN_D") (pin "9") (pinfunction "9_9") (pintype "passive"))
    )
    (net (code "100") (name "MD_PWM") (class "Default")
      (node (ref "DMD") (pin "17") (pinfunction "DIG_IN1_17") (pintype "bidirectional"))
      (node (ref "MAIN_CONN_D") (pin "6") (pinfunction "6_6") (pintype "passive"))
    )
    (net (code "101") (name "M_EN") (class "Default")
      (node (ref "AMD") (pin "15") (pinfunction "DIG_IN/OUT3_15") (pintype "bidirectional"))
      (node (ref "BMD") (pin "15") (pinfunction "DIG_IN/OUT3_15") (pintype "bidirectional"))
      (node (ref "CMD") (pin "15") (pinfunction "DIG_IN/OUT3_15") (pintype "bidirectional"))
      (node (ref "DMD") (pin "15") (pinfunction "DIG_IN/OUT3_15") (pintype "bidirectional"))
      (node (ref "MAIN_CONN_A") (pin "2") (pinfunction "2_2") (pintype "passive"))
      (node (ref "MAIN_CONN_B") (pin "2") (pinfunction "2_2") (pintype "passive"))
      (node (ref "MAIN_CONN_C") (pin "2") (pinfunction "2_2") (pintype "passive"))
      (node (ref "MAIN_CONN_D") (pin "2") (pinfunction "2_2") (pintype "passive"))
    )
    (net (code "102") (name "Net-(AMD-AN_OUT2)") (class "Default")
      (node (ref "AMD") (pin "19") (pinfunction "AN_OUT2_19") (pintype "bidirectional"))
      (node (ref "AOUT2") (pin "1") (pinfunction "TP_1") (pintype "passive"))
    )
    (net (code "103") (name "Net-(BMD-AN_OUT2)") (class "Default")
      (node (ref "BMD") (pin "19") (pinfunction "AN_OUT2_19") (pintype "bidirectional"))
      (node (ref "BOUT2") (pin "1") (pinfunction "TP_1") (pintype "passive"))
    )
    (net (code "104") (name "Net-(CMD-AN_OUT2)") (class "Default")
      (node (ref "CMD") (pin "19") (pinfunction "AN_OUT2_19") (pintype "bidirectional"))
      (node (ref "COUT2") (pin "1") (pinfunction "TP_1") (pintype "passive"))
    )
    (net (code "105") (name "Net-(D1-PadC)") (class "Default")
      (node (ref "D1") (pin "C") (pinfunction "C_C") (pintype "passive"))
      (node (ref "KICKER_R_CONN") (pin "P") (pinfunction "P_P") (pintype "passive"))
      (node (ref "QR") (pin "S") (pinfunction "S_S") (pintype "passive"))
    )
    (net (code "106") (name "Net-(D2-PadC)") (class "Default")
      (node (ref "D2") (pin "C") (pinfunction "C_C") (pintype "passive"))
      (node (ref "KICKER_F_CONN") (pin "P") (pinfunction "P_P") (pintype "passive"))
      (node (ref "QF") (pin "S") (pinfunction "S_S") (pintype "passive"))
    )
    (net (code "107") (name "Net-(DMD-AN_OUT2)") (class "Default")
      (node (ref "DMD") (pin "19") (pinfunction "AN_OUT2_19") (pintype "bidirectional"))
      (node (ref "DOUT2") (pin "1") (pinfunction "TP_1") (pintype "passive"))
    )
    (net (code "108") (name "Net-(LED0-DOUT)") (class "Default")
      (node (ref "LED0") (pin "3") (pinfunction "DOUT_3") (pintype "output"))
      (node (ref "LED1") (pin "2") (pinfunction "DIN_2") (pintype "input"))
    )
    (net (code "109") (name "Net-(LED1-DOUT)") (class "Default")
      (node (ref "LED1") (pin "3") (pinfunction "DOUT_3") (pintype "output"))
      (node (ref "LED2") (pin "2") (pinfunction "DIN_2") (pintype "input"))
    )
    (net (code "110") (name "Net-(LED2-DOUT)") (class "Default")
      (node (ref "LED2") (pin "3") (pinfunction "DOUT_3") (pintype "output"))
      (node (ref "LED3") (pin "2") (pinfunction "DIN_2") (pintype "input"))
    )
    (net (code "111") (name "Net-(LED3-DOUT)") (class "Default")
      (node (ref "LED3") (pin "3") (pinfunction "DOUT_3") (pintype "output"))
      (node (ref "LED4") (pin "2") (pinfunction "DIN_2") (pintype "input"))
    )
    (net (code "112") (name "Net-(LED4-DOUT)") (class "Default")
      (node (ref "LED4") (pin "3") (pinfunction "DOUT_3") (pintype "output"))
      (node (ref "LED5") (pin "2") (pinfunction "DIN_2") (pintype "input"))
    )
    (net (code "113") (name "Net-(LED5-DOUT)") (class "Default")
      (node (ref "LED5") (pin "3") (pinfunction "DOUT_3") (pintype "output"))
      (node (ref "LED6") (pin "2") (pinfunction "DIN_2") (pintype "input"))
    )
    (net (code "114") (name "Net-(LED6-DOUT)") (class "Default")
      (node (ref "LED6") (pin "3") (pinfunction "DOUT_3") (pintype "output"))
      (node (ref "LED7") (pin "2") (pinfunction "DIN_2") (pintype "input"))
    )
    (net (code "115") (name "Net-(LED7-DOUT)") (class "Default")
      (node (ref "LED7") (pin "3") (pinfunction "DOUT_3") (pintype "output"))
      (node (ref "LED8") (pin "2") (pinfunction "DIN_2") (pintype "input"))
    )
    (net (code "116") (name "Net-(LED8-DOUT)") (class "Default")
      (node (ref "LED8") (pin "3") (pinfunction "DOUT_3") (pintype "output"))
      (node (ref "LED9") (pin "2") (pinfunction "DIN_2") (pintype "input"))
    )
    (net (code "117") (name "Net-(LED10-DIN)") (class "Default")
      (node (ref "LED10") (pin "2") (pinfunction "DIN_2") (pintype "input"))
      (node (ref "LED9") (pin "3") (pinfunction "DOUT_3") (pintype "output"))
    )
    (net (code "118") (name "Net-(LED10-DOUT)") (class "Default")
      (node (ref "LED10") (pin "3") (pinfunction "DOUT_3") (pintype "output"))
      (node (ref "LED11") (pin "2") (pinfunction "DIN_2") (pintype "input"))
    )
    (net (code "119") (name "Net-(LED11-DOUT)") (class "Default")
      (node (ref "LED11") (pin "3") (pinfunction "DOUT_3") (pintype "output"))
      (node (ref "LED12") (pin "2") (pinfunction "DIN_2") (pintype "input"))
    )
    (net (code "120") (name "Net-(LED12-DOUT)") (class "Default")
      (node (ref "LED12") (pin "3") (pinfunction "DOUT_3") (pintype "output"))
      (node (ref "LED13") (pin "2") (pinfunction "DIN_2") (pintype "input"))
    )
    (net (code "121") (name "Net-(LED13-DOUT)") (class "Default")
      (node (ref "LED13") (pin "3") (pinfunction "DOUT_3") (pintype "output"))
      (node (ref "LED14") (pin "2") (pinfunction "DIN_2") (pintype "input"))
    )
    (net (code "122") (name "Net-(LED14-DOUT)") (class "Default")
      (node (ref "LED14") (pin "3") (pinfunction "DOUT_3") (pintype "output"))
      (node (ref "LED15") (pin "2") (pinfunction "DIN_2") (pintype "input"))
    )
    (net (code "123") (name "Net-(LED15-DOUT)") (class "Default")
      (node (ref "LED15") (pin "3") (pinfunction "DOUT_3") (pintype "output"))
      (node (ref "LED16") (pin "2") (pinfunction "DIN_2") (pintype "input"))
    )
    (net (code "124") (name "Net-(LED16-DOUT)") (class "Default")
      (node (ref "LED16") (pin "3") (pinfunction "DOUT_3") (pintype "output"))
      (node (ref "LED17") (pin "2") (pinfunction "DIN_2") (pintype "input"))
    )
    (net (code "125") (name "Net-(LED17-DOUT)") (class "Default")
      (node (ref "LED17") (pin "3") (pinfunction "DOUT_3") (pintype "output"))
      (node (ref "LED18") (pin "2") (pinfunction "DIN_2") (pintype "input"))
    )
    (net (code "126") (name "Net-(LED18-DOUT)") (class "Default")
      (node (ref "LED18") (pin "3") (pinfunction "DOUT_3") (pintype "output"))
      (node (ref "LED19") (pin "2") (pinfunction "DIN_2") (pintype "input"))
    )
    (net (code "127") (name "Net-(LED19-DOUT)") (class "Default")
      (node (ref "LED19") (pin "3") (pinfunction "DOUT_3") (pintype "output"))
      (node (ref "LED20") (pin "2") (pinfunction "DIN_2") (pintype "input"))
    )
    (net (code "128") (name "Net-(LED20-DOUT)") (class "Default")
      (node (ref "LED20") (pin "3") (pinfunction "DOUT_3") (pintype "output"))
      (node (ref "LED21") (pin "2") (pinfunction "DIN_2") (pintype "input"))
    )
    (net (code "129") (name "Net-(LED21-DOUT)") (class "Default")
      (node (ref "LED21") (pin "3") (pinfunction "DOUT_3") (pintype "output"))
      (node (ref "LED22") (pin "2") (pinfunction "DIN_2") (pintype "input"))
    )
    (net (code "130") (name "Net-(LED22-DOUT)") (class "Default")
      (node (ref "LED22") (pin "3") (pinfunction "DOUT_3") (pintype "output"))
      (node (ref "LED23") (pin "2") (pinfunction "DIN_2") (pintype "input"))
    )
    (net (code "131") (name "Net-(LED23-DOUT)") (class "Default")
      (node (ref "LED23") (pin "3") (pinfunction "DOUT_3") (pintype "output"))
      (node (ref "LED24") (pin "2") (pinfunction "DIN_2") (pintype "input"))
    )
    (net (code "132") (name "Net-(LED24-DOUT)") (class "Default")
      (node (ref "LED24") (pin "3") (pinfunction "DOUT_3") (pintype "output"))
      (node (ref "LED25") (pin "2") (pinfunction "DIN_2") (pintype "input"))
    )
    (net (code "133") (name "Net-(LED25-DOUT)") (class "Default")
      (node (ref "LED25") (pin "3") (pinfunction "DOUT_3") (pintype "output"))
      (node (ref "LED26") (pin "2") (pinfunction "DIN_2") (pintype "input"))
    )
    (net (code "134") (name "Net-(LED26-DOUT)") (class "Default")
      (node (ref "LED26") (pin "3") (pinfunction "DOUT_3") (pintype "output"))
      (node (ref "LED27") (pin "2") (pinfunction "DIN_2") (pintype "input"))
    )
    (net (code "135") (name "Net-(LED27-DOUT)") (class "Default")
      (node (ref "LED27") (pin "3") (pinfunction "DOUT_3") (pintype "output"))
      (node (ref "LED28") (pin "2") (pinfunction "DIN_2") (pintype "input"))
    )
    (net (code "136") (name "Net-(LED28-DOUT)") (class "Default")
      (node (ref "LED28") (pin "3") (pinfunction "DOUT_3") (pintype "output"))
      (node (ref "LED29") (pin "2") (pinfunction "DIN_2") (pintype "input"))
    )
    (net (code "137") (name "Net-(LED29-DOUT)") (class "Default")
      (node (ref "LED29") (pin "3") (pinfunction "DOUT_3") (pintype "output"))
      (node (ref "LED30") (pin "2") (pinfunction "DIN_2") (pintype "input"))
    )
    (net (code "138") (name "Net-(LED30-DOUT)") (class "Default")
      (node (ref "LED30") (pin "3") (pinfunction "DOUT_3") (pintype "output"))
      (node (ref "LED31") (pin "2") (pinfunction "DIN_2") (pintype "input"))
    )
    (net (code "139") (name "Net-(LED32-DOUT)") (class "Default")
      (node (ref "LED32") (pin "3") (pinfunction "DOUT_3") (pintype "output"))
      (node (ref "LED33") (pin "2") (pinfunction "DIN_2") (pintype "input"))
    )
    (net (code "140") (name "Net-(LED33-DOUT)") (class "Default")
      (node (ref "LED33") (pin "3") (pinfunction "DOUT_3") (pintype "output"))
      (node (ref "LED34") (pin "2") (pinfunction "DIN_2") (pintype "input"))
    )
    (net (code "141") (name "Net-(LED34-DOUT)") (class "Default")
      (node (ref "LED34") (pin "3") (pinfunction "DOUT_3") (pintype "output"))
      (node (ref "LED35") (pin "2") (pinfunction "DIN_2") (pintype "input"))
    )
    (net (code "142") (name "Net-(LED35-DOUT)") (class "Default")
      (node (ref "LED35") (pin "3") (pinfunction "DOUT_3") (pintype "output"))
      (node (ref "LED36") (pin "2") (pinfunction "DIN_2") (pintype "input"))
    )
    (net (code "143") (name "Net-(LED36-DOUT)") (class "Default")
      (node (ref "LED36") (pin "3") (pinfunction "DOUT_3") (pintype "output"))
      (node (ref "LED37") (pin "2") (pinfunction "DIN_2") (pintype "input"))
    )
    (net (code "144") (name "Net-(LED37-DOUT)") (class "Default")
      (node (ref "LED37") (pin "3") (pinfunction "DOUT_3") (pintype "output"))
      (node (ref "LED38") (pin "2") (pinfunction "DIN_2") (pintype "input"))
    )
    (net (code "145") (name "Net-(LED38-DOUT)") (class "Default")
      (node (ref "LED38") (pin "3") (pinfunction "DOUT_3") (pintype "output"))
      (node (ref "LED39") (pin "2") (pinfunction "DIN_2") (pintype "input"))
    )
    (net (code "146") (name "Net-(LED39-DOUT)") (class "Default")
      (node (ref "LED39") (pin "3") (pinfunction "DOUT_3") (pintype "output"))
      (node (ref "LED40") (pin "2") (pinfunction "DIN_2") (pintype "input"))
    )
    (net (code "147") (name "Net-(LED40-DOUT)") (class "Default")
      (node (ref "LED40") (pin "3") (pinfunction "DOUT_3") (pintype "output"))
      (node (ref "LED41") (pin "2") (pinfunction "DIN_2") (pintype "input"))
    )
    (net (code "148") (name "Net-(LED41-DOUT)") (class "Default")
      (node (ref "LED41") (pin "3") (pinfunction "DOUT_3") (pintype "output"))
      (node (ref "LED42") (pin "2") (pinfunction "DIN_2") (pintype "input"))
    )
    (net (code "149") (name "Net-(LED42-DOUT)") (class "Default")
      (node (ref "LED42") (pin "3") (pinfunction "DOUT_3") (pintype "output"))
      (node (ref "LED43") (pin "2") (pinfunction "DIN_2") (pintype "input"))
    )
    (net (code "150") (name "Net-(LED43-DOUT)") (class "Default")
      (node (ref "LED43") (pin "3") (pinfunction "DOUT_3") (pintype "output"))
      (node (ref "LED44") (pin "2") (pinfunction "DIN_2") (pintype "input"))
    )
    (net (code "151") (name "Net-(LED44-DOUT)") (class "Default")
      (node (ref "LED44") (pin "3") (pinfunction "DOUT_3") (pintype "output"))
      (node (ref "LED45") (pin "2") (pinfunction "DIN_2") (pintype "input"))
    )
    (net (code "152") (name "Net-(LED45-DOUT)") (class "Default")
      (node (ref "LED45") (pin "3") (pinfunction "DOUT_3") (pintype "output"))
      (node (ref "LED46") (pin "2") (pinfunction "DIN_2") (pintype "input"))
    )
    (net (code "153") (name "Net-(LED46-DOUT)") (class "Default")
      (node (ref "LED46") (pin "3") (pinfunction "DOUT_3") (pintype "output"))
      (node (ref "LED47") (pin "2") (pinfunction "DIN_2") (pintype "input"))
    )
    (net (code "154") (name "Net-(MOSDRIVER-OUT_1)") (class "Default")
      (node (ref "MOSDRIVER") (pin "7") (pinfunction "OUT_1_7") (pintype "output"))
      (node (ref "R48") (pin "2") (pinfunction "2_2") (pintype "passive"))
    )
    (net (code "155") (name "Net-(MOSDRIVER-OUT_2)") (class "Default")
      (node (ref "MOSDRIVER") (pin "5") (pinfunction "OUT_2_5") (pintype "output"))
      (node (ref "R49") (pin "2") (pinfunction "2_2") (pintype "passive"))
    )
    (net (code "156") (name "Net-(QF-PadG)") (class "Default")
      (node (ref "QF") (pin "G") (pinfunction "G_G") (pintype "passive"))
      (node (ref "R49") (pin "1") (pinfunction "1_1") (pintype "passive"))
    )
    (net (code "157") (name "Net-(QR-PadG)") (class "Default")
      (node (ref "QR") (pin "G") (pinfunction "G_G") (pintype "passive"))
      (node (ref "R48") (pin "1") (pinfunction "1_1") (pintype "passive"))
    )
    (net (code "158") (name "X_LINE0") (class "Default")
      (node (ref "PHOTO32") (pin "2") (pinfunction "2_2") (pintype "passive"))
      (node (ref "R32") (pin "1") (pinfunction "1_1") (pintype "passive"))
      (node (ref "XMUX") (pin "9") (pinfunction "I0_9") (pintype "input"))
    )
    (net (code "159") (name "X_LINE1") (class "Default")
      (node (ref "PHOTO33") (pin "2") (pinfunction "2_2") (pintype "passive"))
      (node (ref "R33") (pin "1") (pinfunction "1_1") (pintype "passive"))
      (node (ref "XMUX") (pin "8") (pinfunction "I1_8") (pintype "input"))
    )
    (net (code "160") (name "X_LINE2") (class "Default")
      (node (ref "PHOTO34") (pin "2") (pinfunction "2_2") (pintype "passive"))
      (node (ref "R34") (pin "1") (pinfunction "1_1") (pintype "passive"))
      (node (ref "XMUX") (pin "7") (pinfunction "I2_7") (pintype "input"))
    )
    (net (code "161") (name "X_LINE3") (class "Default")
      (node (ref "PHOTO35") (pin "2") (pinfunction "2_2") (pintype "passive"))
      (node (ref "R35") (pin "1") (pinfunction "1_1") (pintype "passive"))
      (node (ref "XMUX") (pin "6") (pinfunction "I3_6") (pintype "input"))
    )
    (net (code "162") (name "X_LINE4") (class "Default")
      (node (ref "PHOTO36") (pin "2") (pinfunction "2_2") (pintype "passive"))
      (node (ref "R36") (pin "1") (pinfunction "1_1") (pintype "passive"))
      (node (ref "XMUX") (pin "5") (pinfunction "I4_5") (pintype "input"))
    )
    (net (code "163") (name "X_LINE5") (class "Default")
      (node (ref "PHOTO37") (pin "2") (pinfunction "2_2") (pintype "passive"))
      (node (ref "R37") (pin "1") (pinfunction "1_1") (pintype "passive"))
      (node (ref "XMUX") (pin "4") (pinfunction "I5_4") (pintype "input"))
    )
    (net (code "164") (name "X_LINE6") (class "Default")
      (node (ref "PHOTO38") (pin "2") (pinfunction "2_2") (pintype "passive"))
      (node (ref "R38") (pin "1") (pinfunction "1_1") (pintype "passive"))
      (node (ref "XMUX") (pin "3") (pinfunction "I6_3") (pintype "input"))
    )
    (net (code "165") (name "X_LINE7") (class "Default")
      (node (ref "PHOTO39") (pin "2") (pinfunction "2_2") (pintype "passive"))
      (node (ref "R39") (pin "1") (pinfunction "1_1") (pintype "passive"))
      (node (ref "XMUX") (pin "2") (pinfunction "I7_2") (pintype "input"))
    )
    (net (code "166") (name "X_LINE8") (class "Default")
      (node (ref "PHOTO40") (pin "2") (pinfunction "2_2") (pintype "passive"))
      (node (ref "R40") (pin "1") (pinfunction "1_1") (pintype "passive"))
      (node (ref "XMUX") (pin "23") (pinfunction "I8_23") (pintype "input"))
    )
    (net (code "167") (name "X_LINE9") (class "Default")
      (node (ref "PHOTO41") (pin "2") (pinfunction "2_2") (pintype "passive"))
      (node (ref "R41") (pin "1") (pinfunction "1_1") (pintype "passive"))
      (node (ref "XMUX") (pin "22") (pinfunction "I9_22") (pintype "input"))
    )
    (net (code "168") (name "X_LINE10") (class "Default")
      (node (ref "PHOTO42") (pin "2") (pinfunction "2_2") (pintype "passive"))
      (node (ref "R42") (pin "1") (pinfunction "1_1") (pintype "passive"))
      (node (ref "XMUX") (pin "21") (pinfunction "I10_21") (pintype "input"))
    )
    (net (code "169") (name "X_LINE11") (class "Default")
      (node (ref "PHOTO43") (pin "2") (pinfunction "2_2") (pintype "passive"))
      (node (ref "R43") (pin "1") (pinfunction "1_1") (pintype "passive"))
      (node (ref "XMUX") (pin "20") (pinfunction "I11_20") (pintype "input"))
    )
    (net (code "170") (name "X_LINE12") (class "Default")
      (node (ref "PHOTO44") (pin "2") (pinfunction "2_2") (pintype "passive"))
      (node (ref "R44") (pin "1") (pinfunction "1_1") (pintype "passive"))
      (node (ref "XMUX") (pin "19") (pinfunction "I12_19") (pintype "input"))
    )
    (net (code "171") (name "X_LINE13") (class "Default")
      (node (ref "PHOTO45") (pin "2") (pinfunction "2_2") (pintype "passive"))
      (node (ref "R45") (pin "1") (pinfunction "1_1") (pintype "passive"))
      (node (ref "XMUX") (pin "18") (pinfunction "I13_18") (pintype "input"))
    )
    (net (code "172") (name "X_LINE14") (class "Default")
      (node (ref "PHOTO46") (pin "2") (pinfunction "2_2") (pintype "passive"))
      (node (ref "R46") (pin "1") (pinfunction "1_1") (pintype "passive"))
      (node (ref "XMUX") (pin "17") (pinfunction "I14_17") (pintype "input"))
    )
    (net (code "173") (name "X_LINE15") (class "Default")
      (node (ref "PHOTO47") (pin "2") (pinfunction "2_2") (pintype "passive"))
      (node (ref "R47") (pin "1") (pinfunction "1_1") (pintype "passive"))
      (node (ref "XMUX") (pin "16") (pinfunction "I15_16") (pintype "input"))
    )
    (net (code "174") (name "unconnected-(AENC-1-PadA1)") (class "Default")
      (node (ref "AENC") (pin "A1") (pinfunction "1_A1") (pintype "bidirectional"))
    )
    (net (code "175") (name "unconnected-(AENC-4-PadA4)") (class "Default")
      (node (ref "AENC") (pin "A4") (pinfunction "4_A4") (pintype "bidirectional"))
    )
    (net (code "176") (name "unconnected-(AENC-9-PadA9)") (class "Default")
      (node (ref "AENC") (pin "A9") (pinfunction "9_A9") (pintype "bidirectional"))
    )
    (net (code "177") (name "unconnected-(AENC-10-PadA10)") (class "Default")
      (node (ref "AENC") (pin "A10") (pinfunction "10_A10") (pintype "bidirectional"))
    )
    (net (code "178") (name "unconnected-(AHAL-6-PadB6)") (class "Default")
      (node (ref "AHAL") (pin "B6") (pinfunction "6_B6") (pintype "bidirectional"))
    )
    (net (code "179") (name "unconnected-(AMD-AN_IN1+-Pad24)") (class "Default")
      (node (ref "AMD") (pin "24") (pinfunction "AN_IN1+_24") (pintype "bidirectional"))
    )
    (net (code "180") (name "unconnected-(AMD-AN_IN1--Pad23)") (class "Default")
      (node (ref "AMD") (pin "23") (pinfunction "AN_IN1-_23") (pintype "bidirectional"))
    )
    (net (code "181") (name "unconnected-(AMD-AN_IN2+-Pad22)") (class "Default")
      (node (ref "AMD") (pin "22") (pinfunction "AN_IN2+_22") (pintype "bidirectional"))
    )
    (net (code "182") (name "unconnected-(AMD-AN_IN2--Pad21)") (class "Default")
      (node (ref "AMD") (pin "21") (pinfunction "AN_IN2-_21") (pintype "bidirectional"))
    )
    (net (code "183") (name "unconnected-(AMD-DIG_IN2-Pad16)") (class "Default")
      (node (ref "AMD") (pin "16") (pinfunction "DIG_IN2_16") (pintype "bidirectional"))
    )
    (net (code "184") (name "unconnected-(AMW-4-PadC4)") (class "Default")
      (node (ref "AMW") (pin "C4") (pinfunction "4_C4") (pintype "bidirectional"))
    )
    (net (code "185") (name "unconnected-(BENC-1-PadA1)") (class "Default")
      (node (ref "BENC") (pin "A1") (pinfunction "1_A1") (pintype "bidirectional"))
    )
    (net (code "186") (name "unconnected-(BENC-4-PadA4)") (class "Default")
      (node (ref "BENC") (pin "A4") (pinfunction "4_A4") (pintype "bidirectional"))
    )
    (net (code "187") (name "unconnected-(BENC-9-PadA9)") (class "Default")
      (node (ref "BENC") (pin "A9") (pinfunction "9_A9") (pintype "bidirectional"))
    )
    (net (code "188") (name "unconnected-(BENC-10-PadA10)") (class "Default")
      (node (ref "BENC") (pin "A10") (pinfunction "10_A10") (pintype "bidirectional"))
    )
    (net (code "189") (name "unconnected-(BHAL-6-PadB6)") (class "Default")
      (node (ref "BHAL") (pin "B6") (pinfunction "6_B6") (pintype "bidirectional"))
    )
    (net (code "190") (name "unconnected-(BMD-AN_IN1+-Pad24)") (class "Default")
      (node (ref "BMD") (pin "24") (pinfunction "AN_IN1+_24") (pintype "bidirectional"))
    )
    (net (code "191") (name "unconnected-(BMD-AN_IN1--Pad23)") (class "Default")
      (node (ref "BMD") (pin "23") (pinfunction "AN_IN1-_23") (pintype "bidirectional"))
    )
    (net (code "192") (name "unconnected-(BMD-AN_IN2+-Pad22)") (class "Default")
      (node (ref "BMD") (pin "22") (pinfunction "AN_IN2+_22") (pintype "bidirectional"))
    )
    (net (code "193") (name "unconnected-(BMD-AN_IN2--Pad21)") (class "Default")
      (node (ref "BMD") (pin "21") (pinfunction "AN_IN2-_21") (pintype "bidirectional"))
    )
    (net (code "194") (name "unconnected-(BMD-DIG_IN2-Pad16)") (class "Default")
      (node (ref "BMD") (pin "16") (pinfunction "DIG_IN2_16") (pintype "bidirectional"))
    )
    (net (code "195") (name "unconnected-(BMW-4-PadC4)") (class "Default")
      (node (ref "BMW") (pin "C4") (pinfunction "4_C4") (pintype "bidirectional"))
    )
    (net (code "196") (name "unconnected-(CENC-1-PadA1)") (class "Default")
      (node (ref "CENC") (pin "A1") (pinfunction "1_A1") (pintype "bidirectional"))
    )
    (net (code "197") (name "unconnected-(CENC-4-PadA4)") (class "Default")
      (node (ref "CENC") (pin "A4") (pinfunction "4_A4") (pintype "bidirectional"))
    )
    (net (code "198") (name "unconnected-(CENC-9-PadA9)") (class "Default")
      (node (ref "CENC") (pin "A9") (pinfunction "9_A9") (pintype "bidirectional"))
    )
    (net (code "199") (name "unconnected-(CENC-10-PadA10)") (class "Default")
      (node (ref "CENC") (pin "A10") (pinfunction "10_A10") (pintype "bidirectional"))
    )
    (net (code "200") (name "unconnected-(CHAL-6-PadB6)") (class "Default")
      (node (ref "CHAL") (pin "B6") (pinfunction "6_B6") (pintype "bidirectional"))
    )
    (net (code "201") (name "unconnected-(CMD-AN_IN1+-Pad24)") (class "Default")
      (node (ref "CMD") (pin "24") (pinfunction "AN_IN1+_24") (pintype "bidirectional"))
    )
    (net (code "202") (name "unconnected-(CMD-AN_IN1--Pad23)") (class "Default")
      (node (ref "CMD") (pin "23") (pinfunction "AN_IN1-_23") (pintype "bidirectional"))
    )
    (net (code "203") (name "unconnected-(CMD-AN_IN2+-Pad22)") (class "Default")
      (node (ref "CMD") (pin "22") (pinfunction "AN_IN2+_22") (pintype "bidirectional"))
    )
    (net (code "204") (name "unconnected-(CMD-AN_IN2--Pad21)") (class "Default")
      (node (ref "CMD") (pin "21") (pinfunction "AN_IN2-_21") (pintype "bidirectional"))
    )
    (net (code "205") (name "unconnected-(CMD-DIG_IN2-Pad16)") (class "Default")
      (node (ref "CMD") (pin "16") (pinfunction "DIG_IN2_16") (pintype "bidirectional"))
    )
    (net (code "206") (name "unconnected-(CMW-4-PadC4)") (class "Default")
      (node (ref "CMW") (pin "C4") (pinfunction "4_C4") (pintype "bidirectional"))
    )
    (net (code "207") (name "unconnected-(DENC-1-PadA1)") (class "Default")
      (node (ref "DENC") (pin "A1") (pinfunction "1_A1") (pintype "bidirectional"))
    )
    (net (code "208") (name "unconnected-(DENC-4-PadA4)") (class "Default")
      (node (ref "DENC") (pin "A4") (pinfunction "4_A4") (pintype "bidirectional"))
    )
    (net (code "209") (name "unconnected-(DENC-9-PadA9)") (class "Default")
      (node (ref "DENC") (pin "A9") (pinfunction "9_A9") (pintype "bidirectional"))
    )
    (net (code "210") (name "unconnected-(DENC-10-PadA10)") (class "Default")
      (node (ref "DENC") (pin "A10") (pinfunction "10_A10") (pintype "bidirectional"))
    )
    (net (code "211") (name "unconnected-(DHAL-6-PadB6)") (class "Default")
      (node (ref "DHAL") (pin "B6") (pinfunction "6_B6") (pintype "bidirectional"))
    )
    (net (code "212") (name "unconnected-(DMD-AN_IN1+-Pad24)") (class "Default")
      (node (ref "DMD") (pin "24") (pinfunction "AN_IN1+_24") (pintype "bidirectional"))
    )
    (net (code "213") (name "unconnected-(DMD-AN_IN1--Pad23)") (class "Default")
      (node (ref "DMD") (pin "23") (pinfunction "AN_IN1-_23") (pintype "bidirectional"))
    )
    (net (code "214") (name "unconnected-(DMD-AN_IN2+-Pad22)") (class "Default")
      (node (ref "DMD") (pin "22") (pinfunction "AN_IN2+_22") (pintype "bidirectional"))
    )
    (net (code "215") (name "unconnected-(DMD-AN_IN2--Pad21)") (class "Default")
      (node (ref "DMD") (pin "21") (pinfunction "AN_IN2-_21") (pintype "bidirectional"))
    )
    (net (code "216") (name "unconnected-(DMD-DIG_IN2-Pad16)") (class "Default")
      (node (ref "DMD") (pin "16") (pinfunction "DIG_IN2_16") (pintype "bidirectional"))
    )
    (net (code "217") (name "unconnected-(DMW-4-PadC4)") (class "Default")
      (node (ref "DMW") (pin "C4") (pinfunction "4_C4") (pintype "bidirectional"))
    )
    (net (code "218") (name "unconnected-(LED31-DOUT-Pad3)") (class "Default")
      (node (ref "LED31") (pin "3") (pinfunction "DOUT_3") (pintype "output"))
    )
    (net (code "219") (name "unconnected-(LED47-DOUT-Pad3)") (class "Default")
      (node (ref "LED47") (pin "3") (pinfunction "DOUT_3") (pintype "output"))
    )
  )
)
